# Jupiter_Ace_build025.net
KiCad netlist of a schematic drawn in EAGLE
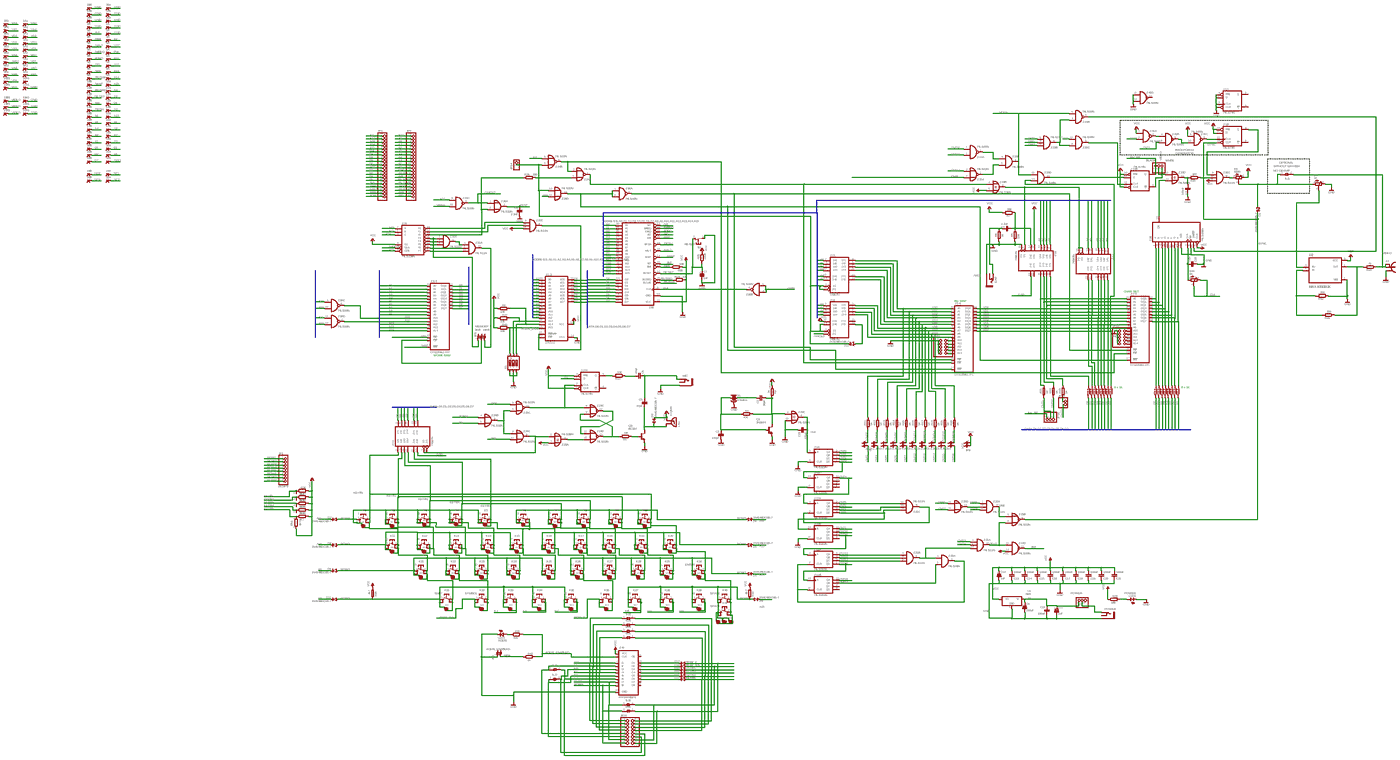
[diagram p0: schematic, sheet 1, overview]
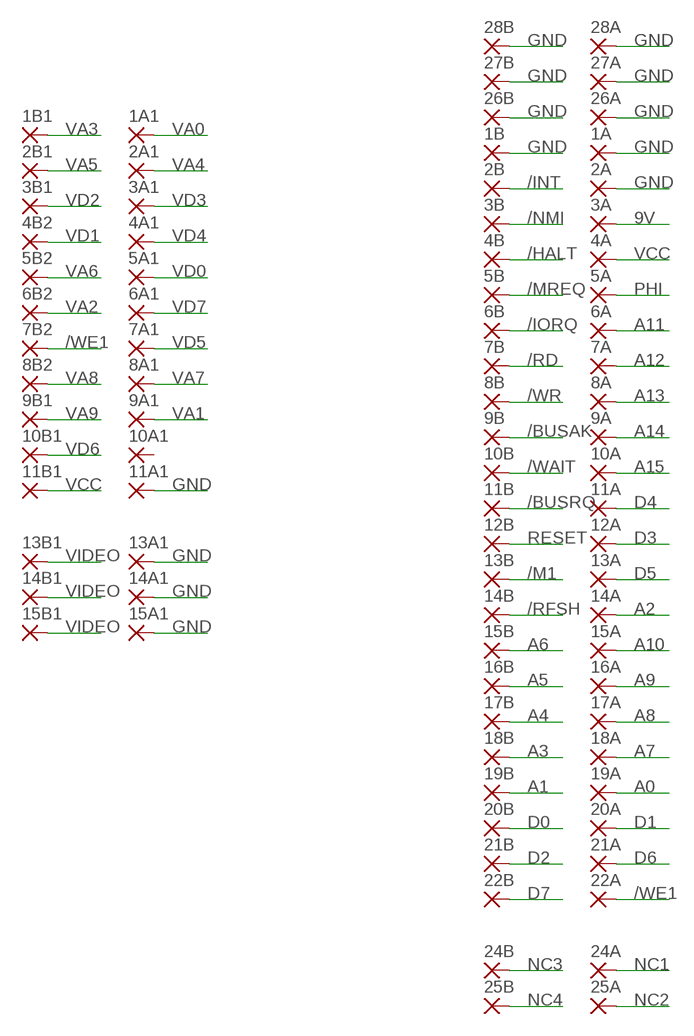
[diagram p1: schematic, sheet 1, part 1 of 6]
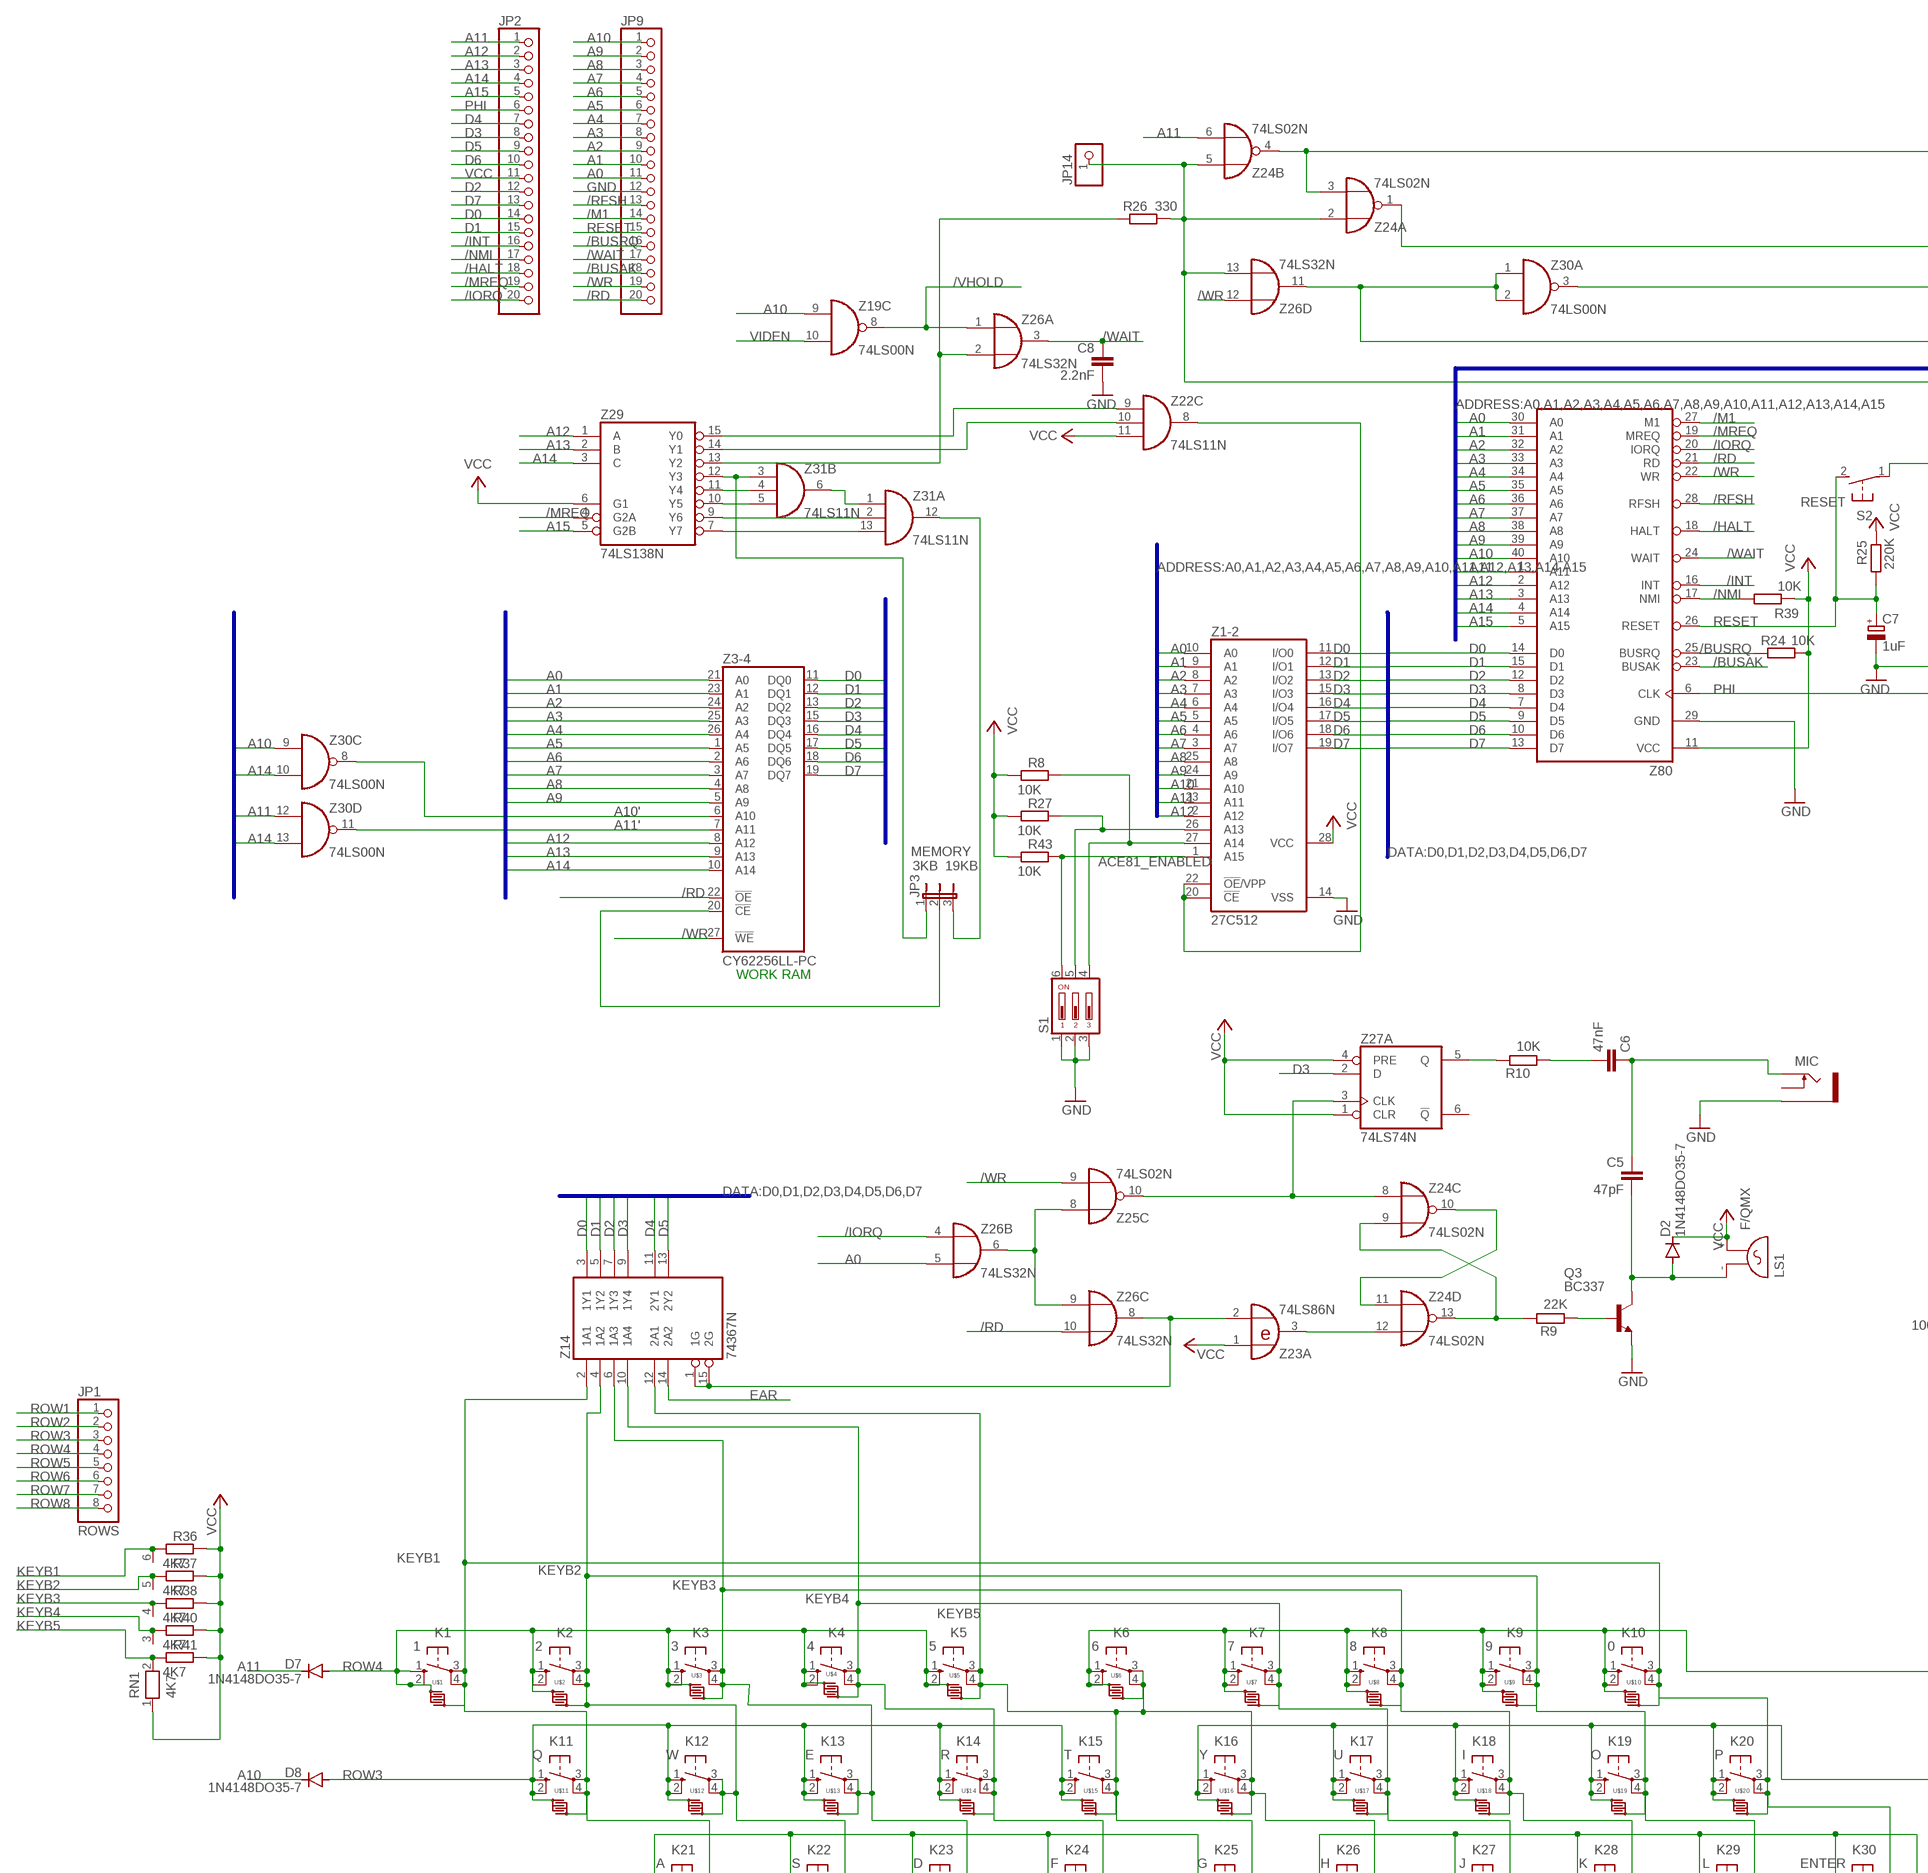
[diagram p2: schematic, sheet 1, part 2 of 6]
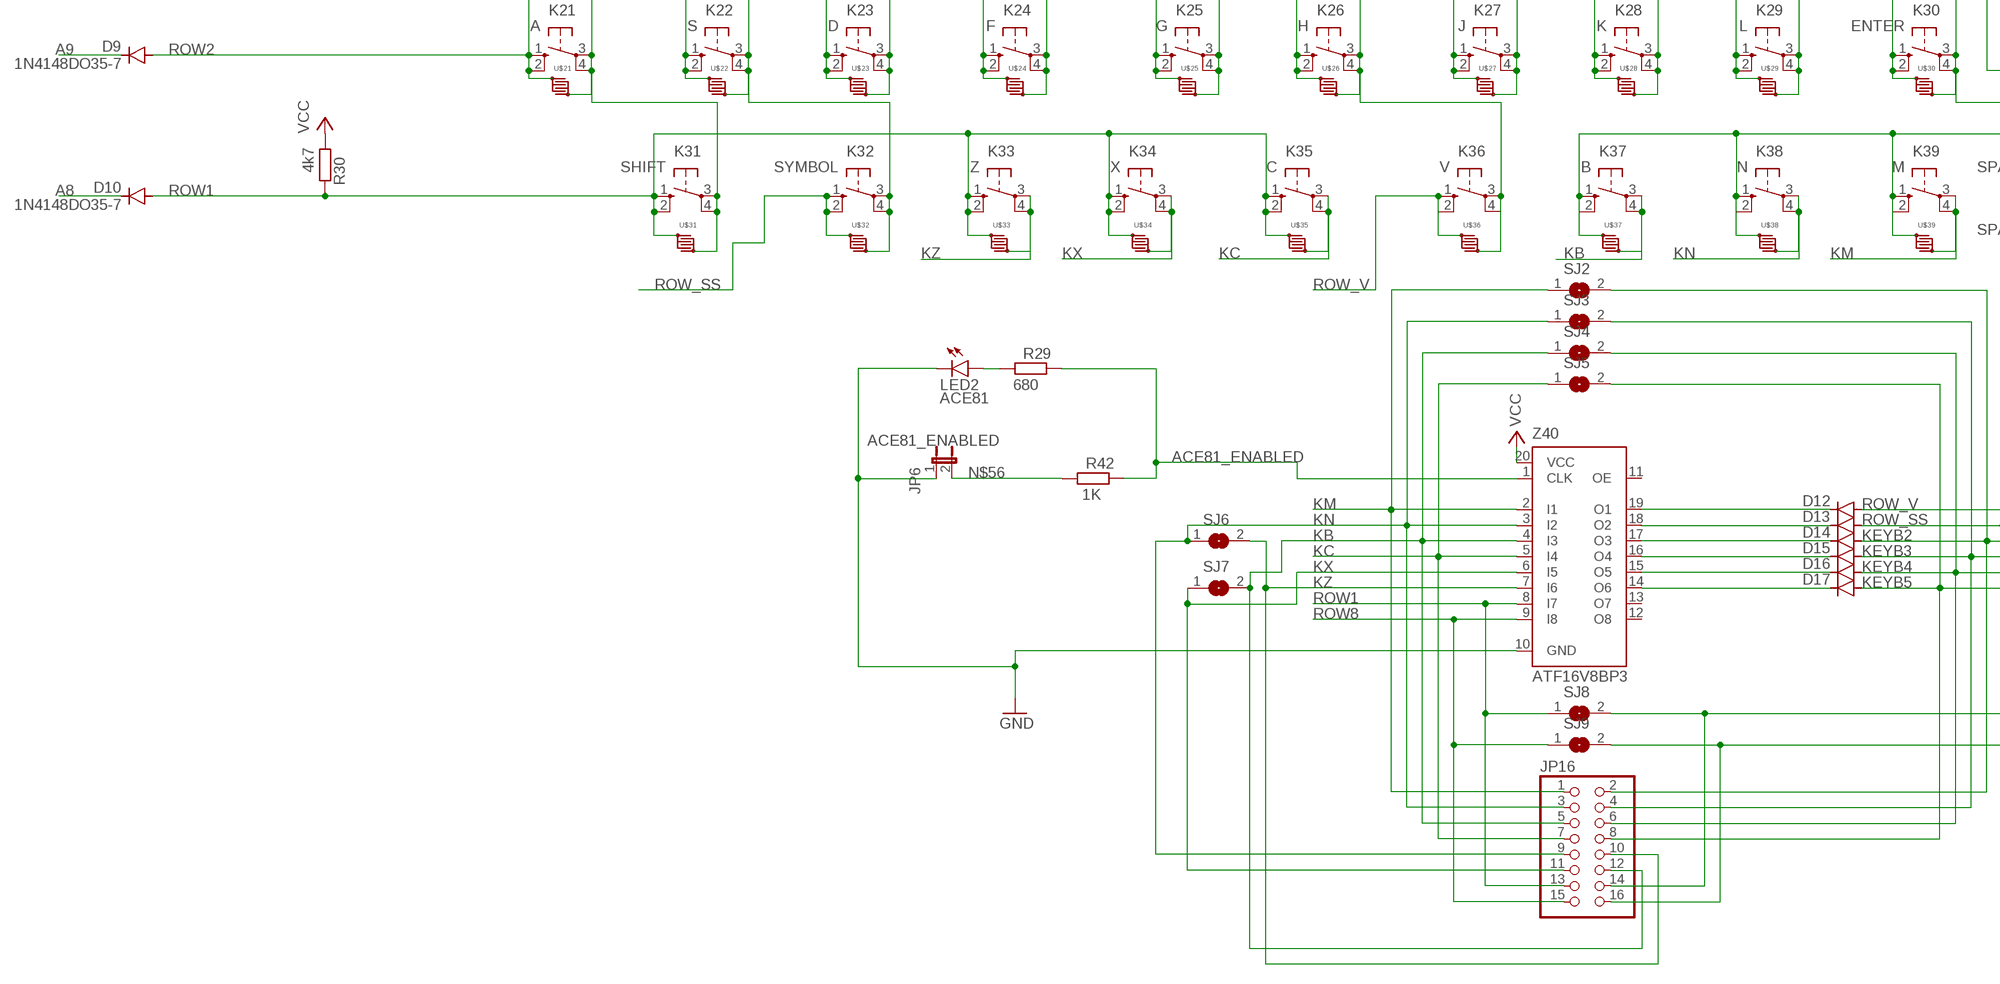
[diagram p3: schematic, sheet 1, part 3 of 6]
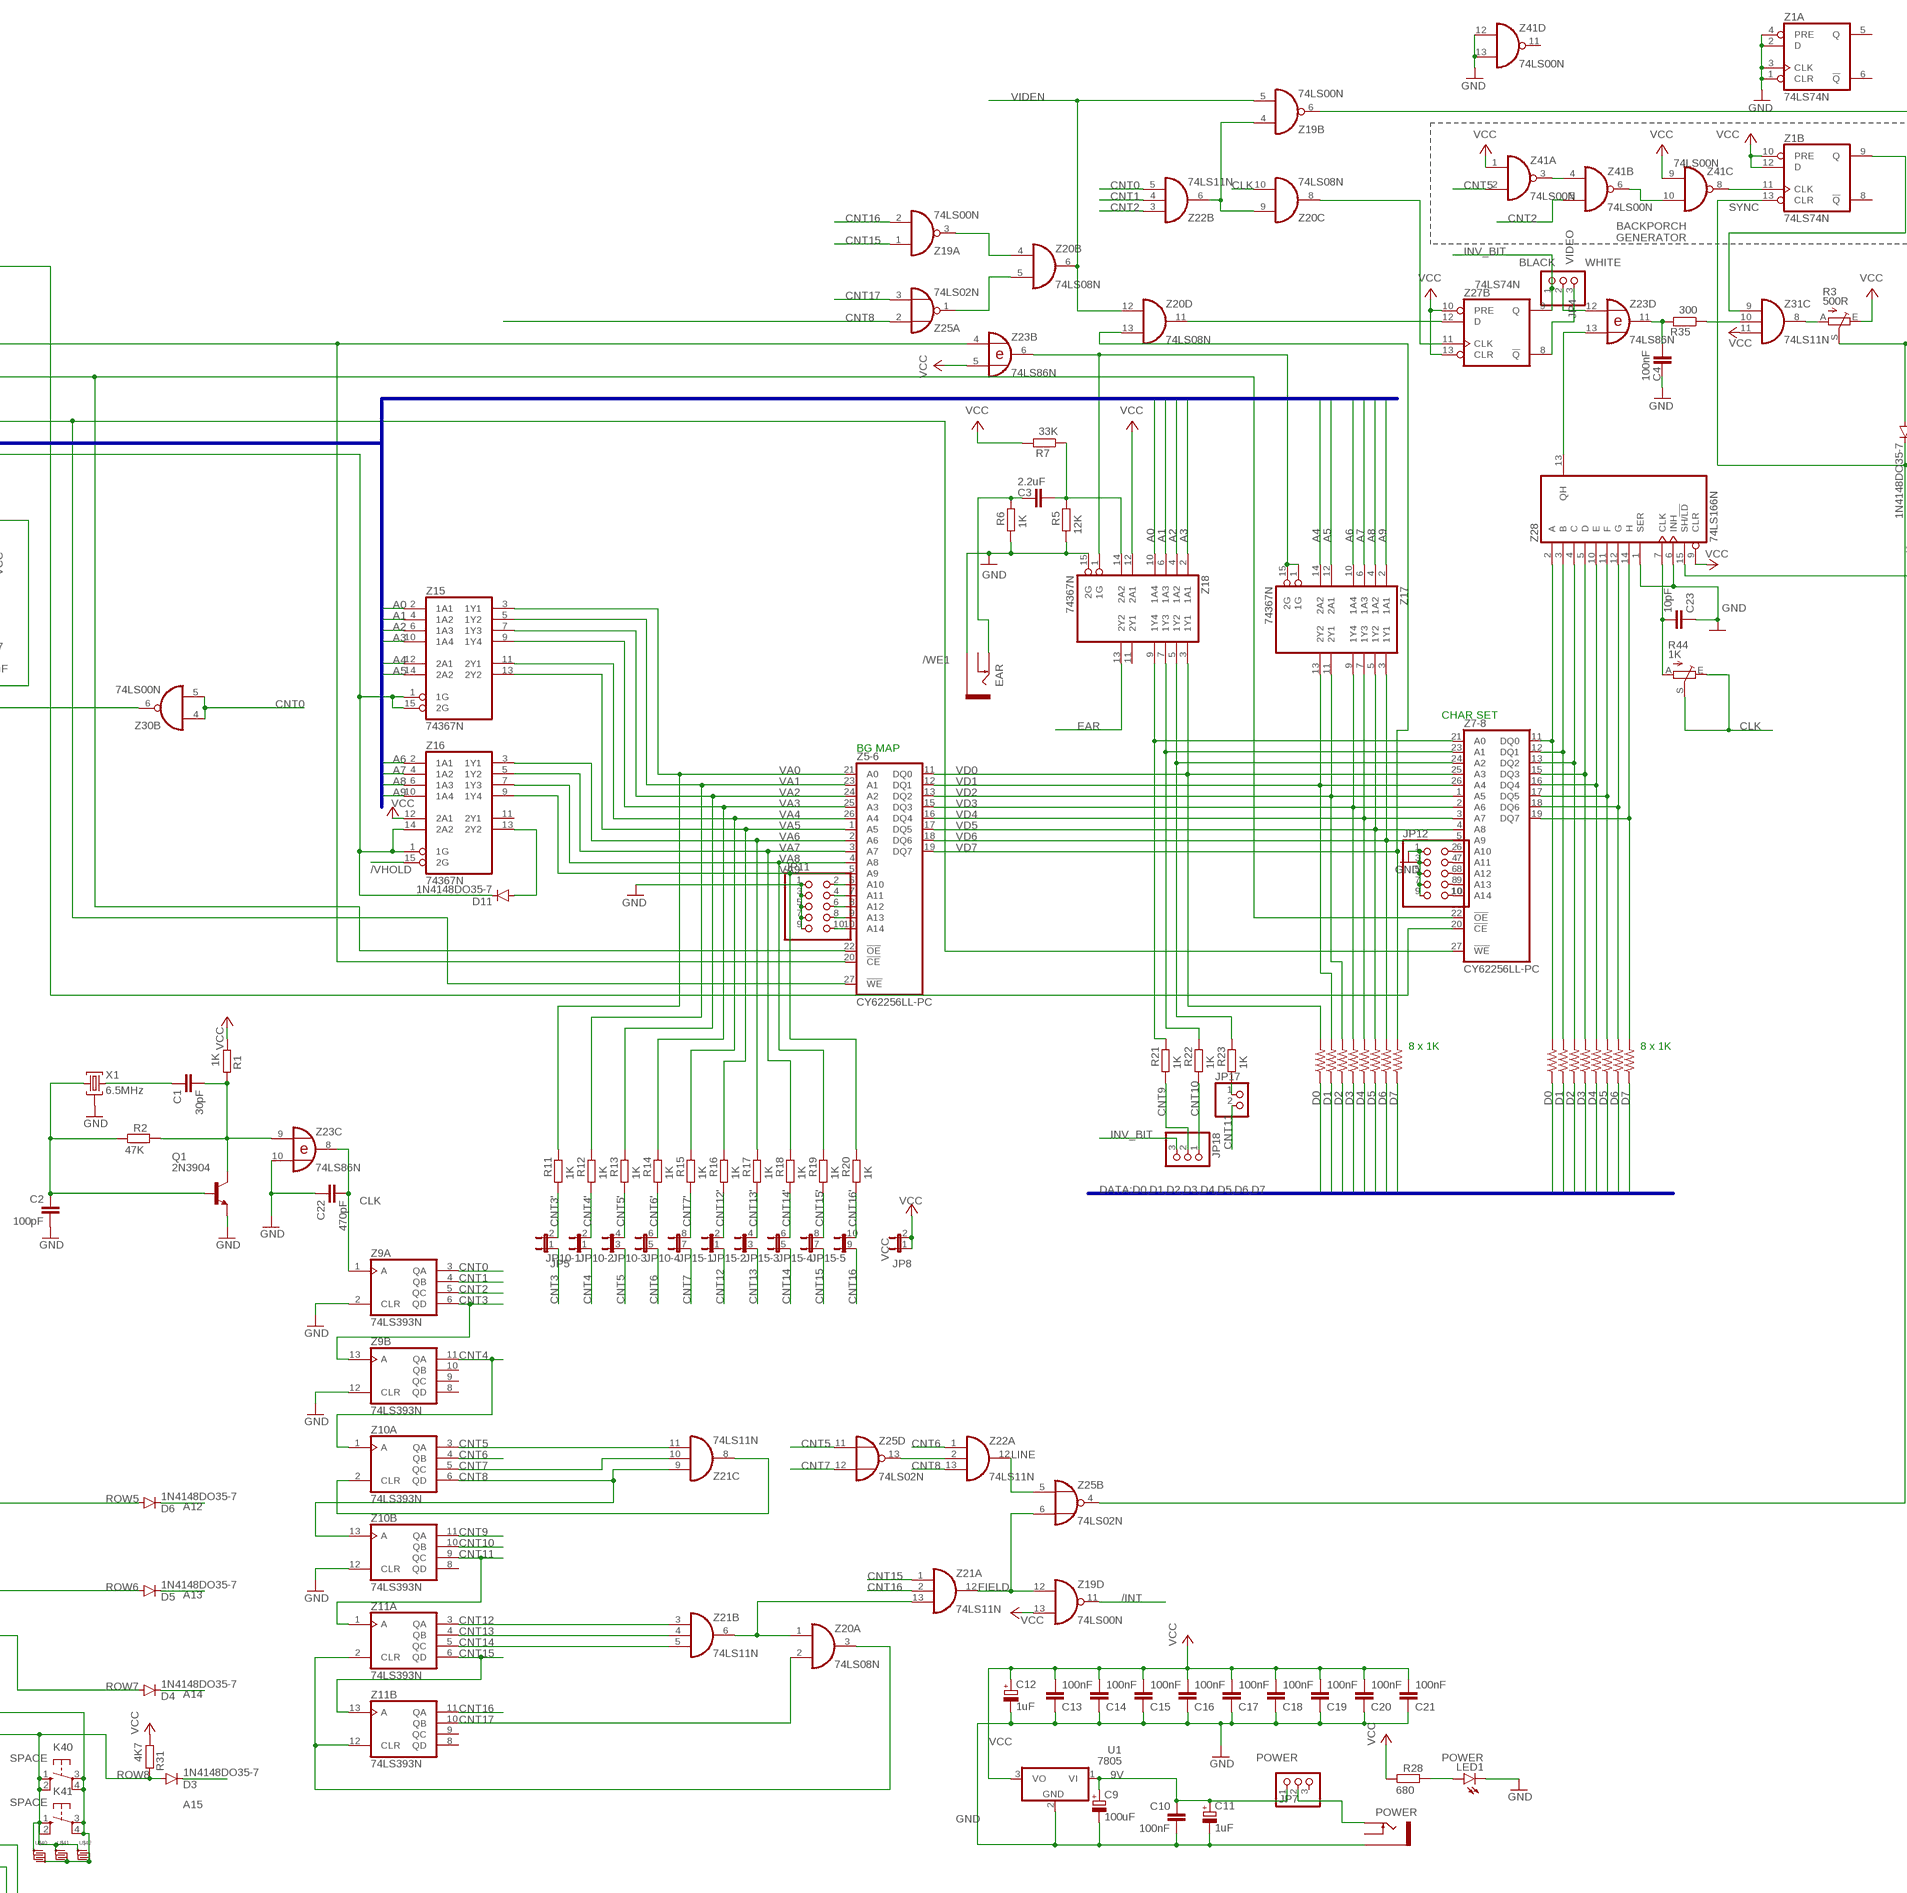
[diagram p4: schematic, sheet 1, part 4 of 6]
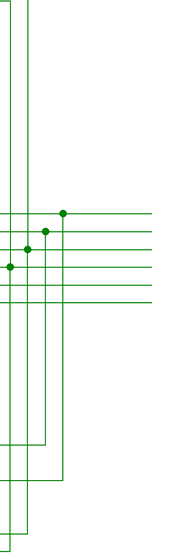
[diagram p5: schematic, sheet 1, part 5 of 6]
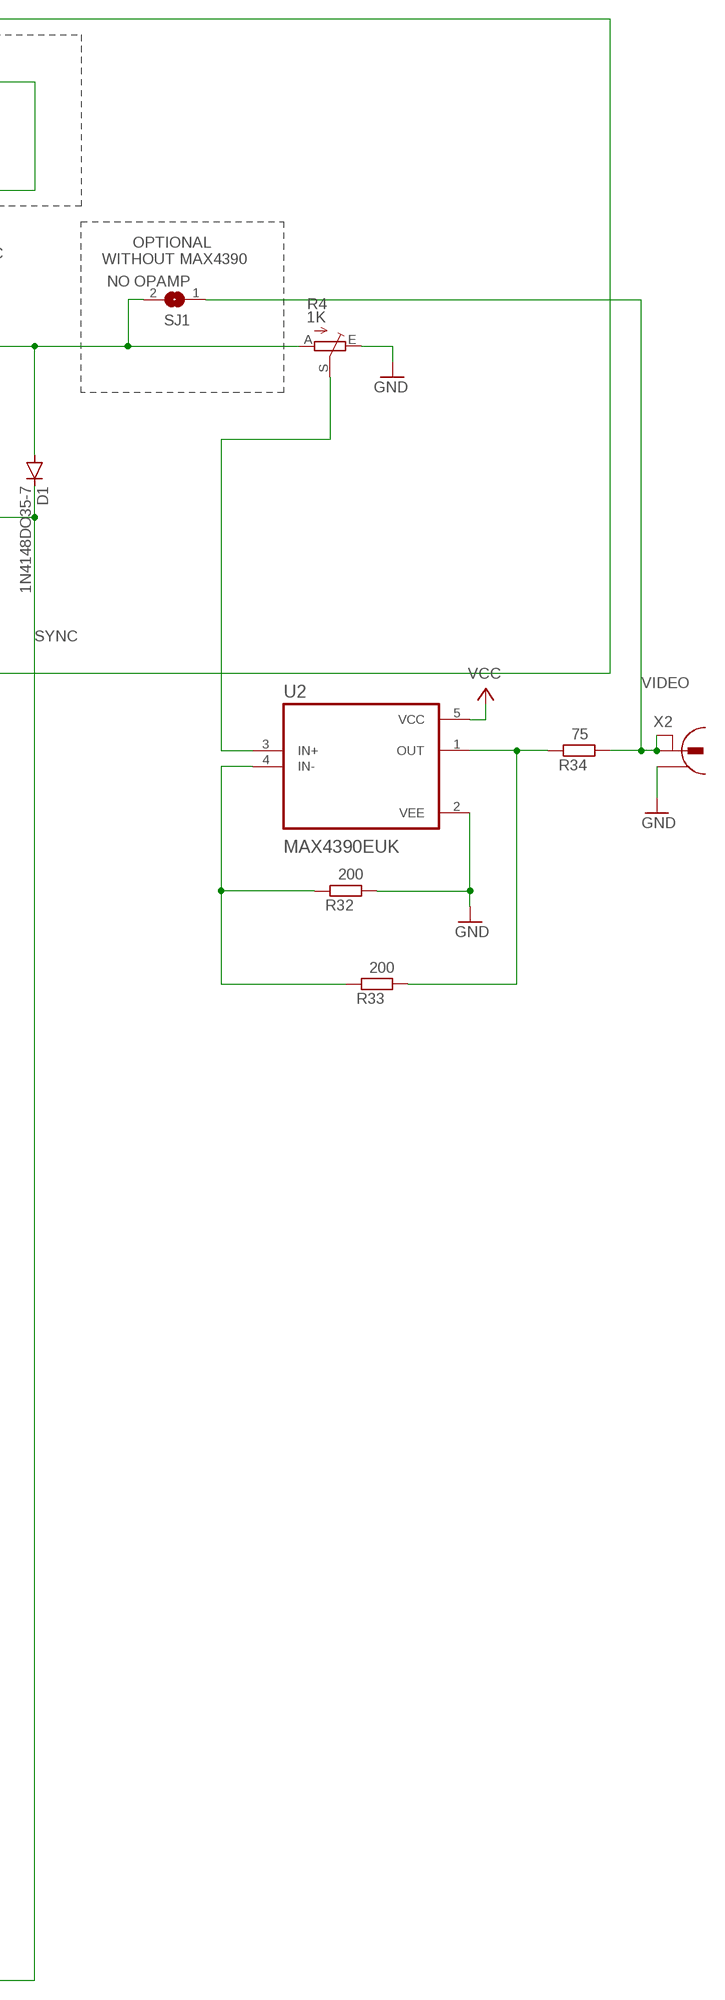
[diagram p6: schematic, sheet 1, part 6 of 6]

(export (version "E")
  (design (tool "Eeschema 10.0.6"))
  (components
    (comp (ref "1A")
      (value "SMD2EDGEPIN")
      (footprint "eagle-import:EDGEPIN")
      (libsource (lib "eagle-import") (part "SMD2EDGEPIN"))
    )
    (comp (ref "1A1")
      (value "SMD2EDGEPIN")
      (footprint "eagle-import:EDGEPIN")
      (libsource (lib "eagle-import") (part "SMD2EDGEPIN"))
    )
    (comp (ref "1B")
      (value "SMD2EDGEPIN")
      (footprint "eagle-import:EDGEPIN")
      (libsource (lib "eagle-import") (part "SMD2EDGEPIN"))
    )
    (comp (ref "1B1")
      (value "SMD2EDGEPIN")
      (footprint "eagle-import:EDGEPIN")
      (libsource (lib "eagle-import") (part "SMD2EDGEPIN"))
    )
    (comp (ref "2A")
      (value "SMD2EDGEPIN")
      (footprint "eagle-import:EDGEPIN")
      (libsource (lib "eagle-import") (part "SMD2EDGEPIN"))
    )
    (comp (ref "2A1")
      (value "SMD2EDGEPIN")
      (footprint "eagle-import:EDGEPIN")
      (libsource (lib "eagle-import") (part "SMD2EDGEPIN"))
    )
    (comp (ref "2B")
      (value "SMD2EDGEPIN")
      (footprint "eagle-import:EDGEPIN")
      (libsource (lib "eagle-import") (part "SMD2EDGEPIN"))
    )
    (comp (ref "2B1")
      (value "SMD2EDGEPIN")
      (footprint "eagle-import:EDGEPIN")
      (libsource (lib "eagle-import") (part "SMD2EDGEPIN"))
    )
    (comp (ref "3A")
      (value "SMD2EDGEPIN")
      (footprint "eagle-import:EDGEPIN")
      (libsource (lib "eagle-import") (part "SMD2EDGEPIN"))
    )
    (comp (ref "3A1")
      (value "SMD2EDGEPIN")
      (footprint "eagle-import:EDGEPIN")
      (libsource (lib "eagle-import") (part "SMD2EDGEPIN"))
    )
    (comp (ref "3B")
      (value "SMD2EDGEPIN")
      (footprint "eagle-import:EDGEPIN")
      (libsource (lib "eagle-import") (part "SMD2EDGEPIN"))
    )
    (comp (ref "3B1")
      (value "SMD2EDGEPIN")
      (footprint "eagle-import:EDGEPIN")
      (libsource (lib "eagle-import") (part "SMD2EDGEPIN"))
    )
    (comp (ref "4A")
      (value "SMD2EDGEPIN")
      (footprint "eagle-import:EDGEPIN")
      (libsource (lib "eagle-import") (part "SMD2EDGEPIN"))
    )
    (comp (ref "4A1")
      (value "SMD2EDGEPIN")
      (footprint "eagle-import:EDGEPIN")
      (libsource (lib "eagle-import") (part "SMD2EDGEPIN"))
    )
    (comp (ref "4B")
      (value "SMD2EDGEPIN")
      (footprint "eagle-import:EDGEPIN")
      (libsource (lib "eagle-import") (part "SMD2EDGEPIN"))
    )
    (comp (ref "4B2")
      (value "SMD2EDGEPIN")
      (footprint "eagle-import:EDGEPIN")
      (libsource (lib "eagle-import") (part "SMD2EDGEPIN"))
    )
    (comp (ref "5A")
      (value "SMD2EDGEPIN")
      (footprint "eagle-import:EDGEPIN")
      (libsource (lib "eagle-import") (part "SMD2EDGEPIN"))
    )
    (comp (ref "5A1")
      (value "SMD2EDGEPIN")
      (footprint "eagle-import:EDGEPIN")
      (libsource (lib "eagle-import") (part "SMD2EDGEPIN"))
    )
    (comp (ref "5B")
      (value "SMD2EDGEPIN")
      (footprint "eagle-import:EDGEPIN")
      (libsource (lib "eagle-import") (part "SMD2EDGEPIN"))
    )
    (comp (ref "5B2")
      (value "SMD2EDGEPIN")
      (footprint "eagle-import:EDGEPIN")
      (libsource (lib "eagle-import") (part "SMD2EDGEPIN"))
    )
    (comp (ref "6A")
      (value "SMD2EDGEPIN")
      (footprint "eagle-import:EDGEPIN")
      (libsource (lib "eagle-import") (part "SMD2EDGEPIN"))
    )
    (comp (ref "6A1")
      (value "SMD2EDGEPIN")
      (footprint "eagle-import:EDGEPIN")
      (libsource (lib "eagle-import") (part "SMD2EDGEPIN"))
    )
    (comp (ref "6B")
      (value "SMD2EDGEPIN")
      (footprint "eagle-import:EDGEPIN")
      (libsource (lib "eagle-import") (part "SMD2EDGEPIN"))
    )
    (comp (ref "6B2")
      (value "SMD2EDGEPIN")
      (footprint "eagle-import:EDGEPIN")
      (libsource (lib "eagle-import") (part "SMD2EDGEPIN"))
    )
    (comp (ref "7A")
      (value "SMD2EDGEPIN")
      (footprint "eagle-import:EDGEPIN")
      (libsource (lib "eagle-import") (part "SMD2EDGEPIN"))
    )
    (comp (ref "7A1")
      (value "SMD2EDGEPIN")
      (footprint "eagle-import:EDGEPIN")
      (libsource (lib "eagle-import") (part "SMD2EDGEPIN"))
    )
    (comp (ref "7B")
      (value "SMD2EDGEPIN")
      (footprint "eagle-import:EDGEPIN")
      (libsource (lib "eagle-import") (part "SMD2EDGEPIN"))
    )
    (comp (ref "7B2")
      (value "SMD2EDGEPIN")
      (footprint "eagle-import:EDGEPIN")
      (libsource (lib "eagle-import") (part "SMD2EDGEPIN"))
    )
    (comp (ref "8A")
      (value "SMD2EDGEPIN")
      (footprint "eagle-import:EDGEPIN")
      (libsource (lib "eagle-import") (part "SMD2EDGEPIN"))
    )
    (comp (ref "8A1")
      (value "SMD2EDGEPIN")
      (footprint "eagle-import:EDGEPIN")
      (libsource (lib "eagle-import") (part "SMD2EDGEPIN"))
    )
    (comp (ref "8B")
      (value "SMD2EDGEPIN")
      (footprint "eagle-import:EDGEPIN")
      (libsource (lib "eagle-import") (part "SMD2EDGEPIN"))
    )
    (comp (ref "8B2")
      (value "SMD2EDGEPIN")
      (footprint "eagle-import:EDGEPIN")
      (libsource (lib "eagle-import") (part "SMD2EDGEPIN"))
    )
    (comp (ref "9A")
      (value "SMD2EDGEPIN")
      (footprint "eagle-import:EDGEPIN")
      (libsource (lib "eagle-import") (part "SMD2EDGEPIN"))
    )
    (comp (ref "9A1")
      (value "SMD2EDGEPIN")
      (footprint "eagle-import:EDGEPIN")
      (libsource (lib "eagle-import") (part "SMD2EDGEPIN"))
    )
    (comp (ref "9B")
      (value "SMD2EDGEPIN")
      (footprint "eagle-import:EDGEPIN")
      (libsource (lib "eagle-import") (part "SMD2EDGEPIN"))
    )
    (comp (ref "9B1")
      (value "SMD2EDGEPIN")
      (footprint "eagle-import:EDGEPIN")
      (libsource (lib "eagle-import") (part "SMD2EDGEPIN"))
    )
    (comp (ref "10A")
      (value "SMD2EDGEPIN")
      (footprint "eagle-import:EDGEPIN")
      (libsource (lib "eagle-import") (part "SMD2EDGEPIN"))
    )
    (comp (ref "10A1")
      (value "SMD2EDGEPIN")
      (footprint "eagle-import:EDGEPIN")
      (libsource (lib "eagle-import") (part "SMD2EDGEPIN"))
    )
    (comp (ref "10B")
      (value "SMD2EDGEPIN")
      (footprint "eagle-import:EDGEPIN")
      (libsource (lib "eagle-import") (part "SMD2EDGEPIN"))
    )
    (comp (ref "10B1")
      (value "SMD2EDGEPIN")
      (footprint "eagle-import:EDGEPIN")
      (libsource (lib "eagle-import") (part "SMD2EDGEPIN"))
    )
    (comp (ref "11A")
      (value "SMD2EDGEPIN")
      (footprint "eagle-import:EDGEPIN")
      (libsource (lib "eagle-import") (part "SMD2EDGEPIN"))
    )
    (comp (ref "11A1")
      (value "SMD2EDGEPIN")
      (footprint "eagle-import:EDGEPIN")
      (libsource (lib "eagle-import") (part "SMD2EDGEPIN"))
    )
    (comp (ref "11B")
      (value "SMD2EDGEPIN")
      (footprint "eagle-import:EDGEPIN")
      (libsource (lib "eagle-import") (part "SMD2EDGEPIN"))
    )
    (comp (ref "11B1")
      (value "SMD2EDGEPIN")
      (footprint "eagle-import:EDGEPIN")
      (libsource (lib "eagle-import") (part "SMD2EDGEPIN"))
    )
    (comp (ref "12A")
      (value "SMD2EDGEPIN")
      (footprint "eagle-import:EDGEPIN")
      (libsource (lib "eagle-import") (part "SMD2EDGEPIN"))
    )
    (comp (ref "12B")
      (value "SMD2EDGEPIN")
      (footprint "eagle-import:EDGEPIN")
      (libsource (lib "eagle-import") (part "SMD2EDGEPIN"))
    )
    (comp (ref "13A")
      (value "SMD2EDGEPIN")
      (footprint "eagle-import:EDGEPIN")
      (libsource (lib "eagle-import") (part "SMD2EDGEPIN"))
    )
    (comp (ref "13A1")
      (value "SMD2EDGEPIN")
      (footprint "eagle-import:EDGEPIN")
      (libsource (lib "eagle-import") (part "SMD2EDGEPIN"))
    )
    (comp (ref "13B")
      (value "SMD2EDGEPIN")
      (footprint "eagle-import:EDGEPIN")
      (libsource (lib "eagle-import") (part "SMD2EDGEPIN"))
    )
    (comp (ref "13B1")
      (value "SMD2EDGEPIN")
      (footprint "eagle-import:EDGEPIN")
      (libsource (lib "eagle-import") (part "SMD2EDGEPIN"))
    )
    (comp (ref "14A")
      (value "SMD2EDGEPIN")
      (footprint "eagle-import:EDGEPIN")
      (libsource (lib "eagle-import") (part "SMD2EDGEPIN"))
    )
    (comp (ref "14A1")
      (value "SMD2EDGEPIN")
      (footprint "eagle-import:EDGEPIN")
      (libsource (lib "eagle-import") (part "SMD2EDGEPIN"))
    )
    (comp (ref "14B")
      (value "SMD2EDGEPIN")
      (footprint "eagle-import:EDGEPIN")
      (libsource (lib "eagle-import") (part "SMD2EDGEPIN"))
    )
    (comp (ref "14B1")
      (value "SMD2EDGEPIN")
      (footprint "eagle-import:EDGEPIN")
      (libsource (lib "eagle-import") (part "SMD2EDGEPIN"))
    )
    (comp (ref "15A")
      (value "SMD2EDGEPIN")
      (footprint "eagle-import:EDGEPIN")
      (libsource (lib "eagle-import") (part "SMD2EDGEPIN"))
    )
    (comp (ref "15A1")
      (value "SMD2EDGEPIN")
      (footprint "eagle-import:EDGEPIN")
      (libsource (lib "eagle-import") (part "SMD2EDGEPIN"))
    )
    (comp (ref "15B")
      (value "SMD2EDGEPIN")
      (footprint "eagle-import:EDGEPIN")
      (libsource (lib "eagle-import") (part "SMD2EDGEPIN"))
    )
    (comp (ref "15B1")
      (value "SMD2EDGEPIN")
      (footprint "eagle-import:EDGEPIN")
      (libsource (lib "eagle-import") (part "SMD2EDGEPIN"))
    )
    (comp (ref "16A")
      (value "SMD2EDGEPIN")
      (footprint "eagle-import:EDGEPIN")
      (libsource (lib "eagle-import") (part "SMD2EDGEPIN"))
    )
    (comp (ref "16B")
      (value "SMD2EDGEPIN")
      (footprint "eagle-import:EDGEPIN")
      (libsource (lib "eagle-import") (part "SMD2EDGEPIN"))
    )
    (comp (ref "17A")
      (value "SMD2EDGEPIN")
      (footprint "eagle-import:EDGEPIN")
      (libsource (lib "eagle-import") (part "SMD2EDGEPIN"))
    )
    (comp (ref "17B")
      (value "SMD2EDGEPIN")
      (footprint "eagle-import:EDGEPIN")
      (libsource (lib "eagle-import") (part "SMD2EDGEPIN"))
    )
    (comp (ref "18A")
      (value "SMD2EDGEPIN")
      (footprint "eagle-import:EDGEPIN")
      (libsource (lib "eagle-import") (part "SMD2EDGEPIN"))
    )
    (comp (ref "18B")
      (value "SMD2EDGEPIN")
      (footprint "eagle-import:EDGEPIN")
      (libsource (lib "eagle-import") (part "SMD2EDGEPIN"))
    )
    (comp (ref "19A")
      (value "SMD2EDGEPIN")
      (footprint "eagle-import:EDGEPIN")
      (libsource (lib "eagle-import") (part "SMD2EDGEPIN"))
    )
    (comp (ref "19B")
      (value "SMD2EDGEPIN")
      (footprint "eagle-import:EDGEPIN")
      (libsource (lib "eagle-import") (part "SMD2EDGEPIN"))
    )
    (comp (ref "20A")
      (value "SMD2EDGEPIN")
      (footprint "eagle-import:EDGEPIN")
      (libsource (lib "eagle-import") (part "SMD2EDGEPIN"))
    )
    (comp (ref "20B")
      (value "SMD2EDGEPIN")
      (footprint "eagle-import:EDGEPIN")
      (libsource (lib "eagle-import") (part "SMD2EDGEPIN"))
    )
    (comp (ref "21A")
      (value "SMD2EDGEPIN")
      (footprint "eagle-import:EDGEPIN")
      (libsource (lib "eagle-import") (part "SMD2EDGEPIN"))
    )
    (comp (ref "21B")
      (value "SMD2EDGEPIN")
      (footprint "eagle-import:EDGEPIN")
      (libsource (lib "eagle-import") (part "SMD2EDGEPIN"))
    )
    (comp (ref "22A")
      (value "SMD2EDGEPIN")
      (footprint "eagle-import:EDGEPIN")
      (libsource (lib "eagle-import") (part "SMD2EDGEPIN"))
    )
    (comp (ref "22B")
      (value "SMD2EDGEPIN")
      (footprint "eagle-import:EDGEPIN")
      (libsource (lib "eagle-import") (part "SMD2EDGEPIN"))
    )
    (comp (ref "24A")
      (value "SMD2EDGEPIN")
      (footprint "eagle-import:EDGEPIN")
      (libsource (lib "eagle-import") (part "SMD2EDGEPIN"))
    )
    (comp (ref "24B")
      (value "SMD2EDGEPIN")
      (footprint "eagle-import:EDGEPIN")
      (libsource (lib "eagle-import") (part "SMD2EDGEPIN"))
    )
    (comp (ref "25A")
      (value "SMD2EDGEPIN")
      (footprint "eagle-import:EDGEPIN")
      (libsource (lib "eagle-import") (part "SMD2EDGEPIN"))
    )
    (comp (ref "25B")
      (value "SMD2EDGEPIN")
      (footprint "eagle-import:EDGEPIN")
      (libsource (lib "eagle-import") (part "SMD2EDGEPIN"))
    )
    (comp (ref "26A")
      (value "SMD2EDGEPIN")
      (footprint "eagle-import:EDGEPIN")
      (libsource (lib "eagle-import") (part "SMD2EDGEPIN"))
    )
    (comp (ref "26B")
      (value "SMD2EDGEPIN")
      (footprint "eagle-import:EDGEPIN")
      (libsource (lib "eagle-import") (part "SMD2EDGEPIN"))
    )
    (comp (ref "27A")
      (value "SMD2EDGEPIN")
      (footprint "eagle-import:EDGEPIN")
      (libsource (lib "eagle-import") (part "SMD2EDGEPIN"))
    )
    (comp (ref "27B")
      (value "SMD2EDGEPIN")
      (footprint "eagle-import:EDGEPIN")
      (libsource (lib "eagle-import") (part "SMD2EDGEPIN"))
    )
    (comp (ref "28A")
      (value "SMD2EDGEPIN")
      (footprint "eagle-import:EDGEPIN")
      (libsource (lib "eagle-import") (part "SMD2EDGEPIN"))
    )
    (comp (ref "28B")
      (value "SMD2EDGEPIN")
      (footprint "eagle-import:EDGEPIN")
      (libsource (lib "eagle-import") (part "SMD2EDGEPIN"))
    )
    (comp (ref "C1")
      (value "30pF")
      (footprint "eagle-import:C025-025X050")
      (libsource (lib "eagle-import") (part "C-EU025-025X050"))
    )
    (comp (ref "C2")
      (value "100pF")
      (footprint "eagle-import:C025-025X050")
      (libsource (lib "eagle-import") (part "C-EU025-025X050"))
    )
    (comp (ref "C3")
      (value "2.2uF")
      (footprint "eagle-import:C025-025X050")
      (libsource (lib "eagle-import") (part "C-EU025-025X050"))
    )
    (comp (ref "C4")
      (value "100nF")
      (footprint "eagle-import:C025-025X050")
      (libsource (lib "eagle-import") (part "C-EU025-025X050"))
    )
    (comp (ref "C5")
      (value "47pF")
      (footprint "eagle-import:C025-025X050")
      (libsource (lib "eagle-import") (part "C-EU025-025X050"))
    )
    (comp (ref "C6")
      (value "47nF")
      (footprint "eagle-import:C025-025X050")
      (libsource (lib "eagle-import") (part "C-EU025-025X050"))
    )
    (comp (ref "C7")
      (value "1uF")
      (footprint "eagle-import:E1,8-4")
      (libsource (lib "eagle-import") (part "CPOL-EUE1.8-4"))
    )
    (comp (ref "C8")
      (value "2.2nF")
      (footprint "eagle-import:C025-025X050")
      (libsource (lib "eagle-import") (part "C-EU025-025X050"))
    )
    (comp (ref "C9")
      (value "100uF")
      (footprint "eagle-import:E1,8-4")
      (libsource (lib "eagle-import") (part "CPOL-EUE1.8-4"))
    )
    (comp (ref "C10")
      (value "100nF")
      (footprint "eagle-import:C025-025X050")
      (libsource (lib "eagle-import") (part "C-EU025-025X050"))
    )
    (comp (ref "C11")
      (value "1uF")
      (footprint "eagle-import:E1,8-4")
      (libsource (lib "eagle-import") (part "CPOL-EUE1.8-4"))
    )
    (comp (ref "C12")
      (value "1uF")
      (footprint "eagle-import:E1,8-4")
      (libsource (lib "eagle-import") (part "CPOL-EUE1.8-4"))
    )
    (comp (ref "C13")
      (value "100nF")
      (footprint "eagle-import:C025-025X050")
      (libsource (lib "eagle-import") (part "C-EU025-025X050"))
    )
    (comp (ref "C14")
      (value "100nF")
      (footprint "eagle-import:C025-025X050")
      (libsource (lib "eagle-import") (part "C-EU025-025X050"))
    )
    (comp (ref "C15")
      (value "100nF")
      (footprint "eagle-import:C025-025X050")
      (libsource (lib "eagle-import") (part "C-EU025-025X050"))
    )
    (comp (ref "C16")
      (value "100nF")
      (footprint "eagle-import:C025-025X050")
      (libsource (lib "eagle-import") (part "C-EU025-025X050"))
    )
    (comp (ref "C17")
      (value "100nF")
      (footprint "eagle-import:C025-025X050")
      (libsource (lib "eagle-import") (part "C-EU025-025X050"))
    )
    (comp (ref "C18")
      (value "100nF")
      (footprint "eagle-import:C025-025X050")
      (libsource (lib "eagle-import") (part "C-EU025-025X050"))
    )
    (comp (ref "C19")
      (value "100nF")
      (footprint "eagle-import:C025-025X050")
      (libsource (lib "eagle-import") (part "C-EU025-025X050"))
    )
    (comp (ref "C20")
      (value "100nF")
      (footprint "eagle-import:C025-025X050")
      (libsource (lib "eagle-import") (part "C-EU025-025X050"))
    )
    (comp (ref "C21")
      (value "100nF")
      (footprint "eagle-import:C025-025X050")
      (libsource (lib "eagle-import") (part "C-EU025-025X050"))
    )
    (comp (ref "C22")
      (value "470pF")
      (footprint "eagle-import:C025-025X050")
      (libsource (lib "eagle-import") (part "C-EU025-025X050"))
    )
    (comp (ref "C23")
      (value "10pF")
      (footprint "eagle-import:C025-025X050")
      (libsource (lib "eagle-import") (part "C-EU025-025X050"))
    )
    (comp (ref "D1")
      (value "1N4148DO35-7")
      (footprint "eagle-import:DO35-7")
      (libsource (lib "eagle-import") (part "1N4148DO35-7"))
    )
    (comp (ref "D2")
      (value "1N4148DO35-7")
      (footprint "eagle-import:DO35-7")
      (libsource (lib "eagle-import") (part "1N4148DO35-7"))
    )
    (comp (ref "D3")
      (value "1N4148DO35-7")
      (footprint "eagle-import:DO35-7")
      (libsource (lib "eagle-import") (part "1N4148DO35-7"))
    )
    (comp (ref "D4")
      (value "1N4148DO35-7")
      (footprint "eagle-import:DO35-7")
      (libsource (lib "eagle-import") (part "1N4148DO35-7"))
    )
    (comp (ref "D5")
      (value "1N4148DO35-7")
      (footprint "eagle-import:DO35-7")
      (libsource (lib "eagle-import") (part "1N4148DO35-7"))
    )
    (comp (ref "D6")
      (value "1N4148DO35-7")
      (footprint "eagle-import:DO35-7")
      (libsource (lib "eagle-import") (part "1N4148DO35-7"))
    )
    (comp (ref "D7")
      (value "1N4148DO35-7")
      (footprint "eagle-import:DO35-7")
      (libsource (lib "eagle-import") (part "1N4148DO35-7"))
    )
    (comp (ref "D8")
      (value "1N4148DO35-7")
      (footprint "eagle-import:DO35-7")
      (libsource (lib "eagle-import") (part "1N4148DO35-7"))
    )
    (comp (ref "D9")
      (value "1N4148DO35-7")
      (footprint "eagle-import:DO35-7")
      (libsource (lib "eagle-import") (part "1N4148DO35-7"))
    )
    (comp (ref "D10")
      (value "1N4148DO35-7")
      (footprint "eagle-import:DO35-7")
      (libsource (lib "eagle-import") (part "1N4148DO35-7"))
    )
    (comp (ref "D11")
      (value "1N4148DO35-7")
      (footprint "eagle-import:DO35-7")
      (libsource (lib "eagle-import") (part "1N4148DO35-7"))
    )
    (comp (ref "D12")
      (value "1N4148DO35-7")
      (footprint "eagle-import:DO35-7")
      (libsource (lib "eagle-import") (part "1N4148DO35-7"))
    )
    (comp (ref "D13")
      (value "1N4148DO35-7")
      (footprint "eagle-import:DO35-7")
      (libsource (lib "eagle-import") (part "1N4148DO35-7"))
    )
    (comp (ref "D14")
      (value "1N4148DO35-7")
      (footprint "eagle-import:DO35-7")
      (libsource (lib "eagle-import") (part "1N4148DO35-7"))
    )
    (comp (ref "D15")
      (value "1N4148DO35-7")
      (footprint "eagle-import:DO35-7")
      (libsource (lib "eagle-import") (part "1N4148DO35-7"))
    )
    (comp (ref "D16")
      (value "1N4148DO35-7")
      (footprint "eagle-import:DO35-7")
      (libsource (lib "eagle-import") (part "1N4148DO35-7"))
    )
    (comp (ref "D17")
      (value "1N4148DO35-7")
      (footprint "eagle-import:DO35-7")
      (libsource (lib "eagle-import") (part "1N4148DO35-7"))
    )
    (comp (ref "EAR")
      (value "PJ302M")
      (footprint "eagle-import:PJ302M")
      (libsource (lib "eagle-import") (part "PJ302M"))
    )
    (comp (ref "JP1")
      (value "ROWS")
      (footprint "eagle-import:1X08")
      (libsource (lib "eagle-import") (part "PINHD-1X8"))
    )
    (comp (ref "JP2")
      (value "PINHD-1X20")
      (footprint "eagle-import:1X20")
      (libsource (lib "eagle-import") (part "PINHD-1X20"))
    )
    (comp (ref "JP3")
      (value "MEMORY")
      (footprint "eagle-import:JP2")
      (libsource (lib "eagle-import") (part "JP2E"))
    )
    (comp (ref "JP4")
      (value "VIDEO")
      (footprint "eagle-import:1X03")
      (libsource (lib "eagle-import") (part "PINHD-1X3"))
    )
    (comp (ref "JP5")
      (value "JP1E1Q")
      (footprint "eagle-import:JP1Q")
      (libsource (lib "eagle-import") (part "JP1E1Q"))
    )
    (comp (ref "JP6")
      (value "ACE81_ENABLED")
      (footprint "eagle-import:JP1Q")
      (libsource (lib "eagle-import") (part "JP1E1Q"))
    )
    (comp (ref "JP7")
      (value "POWER")
      (footprint "eagle-import:1X03")
      (libsource (lib "eagle-import") (part "PINHD-1X3"))
    )
    (comp (ref "JP8")
      (value "VCC")
      (footprint "eagle-import:JP1Q")
      (libsource (lib "eagle-import") (part "JP1E1Q"))
    )
    (comp (ref "JP9")
      (value "PINHD-1X20")
      (footprint "eagle-import:1X20")
      (libsource (lib "eagle-import") (part "PINHD-1X20"))
    )
    (comp (ref "JP10")
      (value "JP4QE")
      (footprint "eagle-import:JP4Q")
      (libsource (lib "eagle-import") (part "JP4QE"))
    )
    (comp (ref "JP11")
      (value "PINHD-2X5")
      (footprint "eagle-import:2X05")
      (libsource (lib "eagle-import") (part "PINHD-2X5"))
    )
    (comp (ref "JP12")
      (value "PINHD-2X5")
      (footprint "eagle-import:2X05")
      (libsource (lib "eagle-import") (part "PINHD-2X5"))
    )
    (comp (ref "JP14")
      (value "PINHD-1X1")
      (footprint "eagle-import:1X01")
      (libsource (lib "eagle-import") (part "PINHD-1X1"))
    )
    (comp (ref "JP15")
      (value "JP5QE")
      (footprint "eagle-import:JP5Q")
      (libsource (lib "eagle-import") (part "JP5QE"))
    )
    (comp (ref "JP16")
      (value "PINHD-2X8")
      (footprint "eagle-import:2X08")
      (libsource (lib "eagle-import") (part "PINHD-2X8"))
    )
    (comp (ref "JP17")
      (value "PINHD-1X2")
      (footprint "eagle-import:1X02")
      (libsource (lib "eagle-import") (part "PINHD-1X2"))
    )
    (comp (ref "JP18")
      (value "PINHD-1X3")
      (footprint "eagle-import:1X03")
      (libsource (lib "eagle-import") (part "pinhead_44166543_PINHD-1X3"))
    )
    (comp (ref "K1")
      (value "1")
      (footprint "eagle-import:B3F-40XXNOHOLE")
      (libsource (lib "eagle-import") (part "40-XXNOHOLES"))
    )
    (comp (ref "K2")
      (value "2")
      (footprint "eagle-import:B3F-40XXNOHOLE")
      (libsource (lib "eagle-import") (part "40-XXNOHOLES"))
    )
    (comp (ref "K3")
      (value "3")
      (footprint "eagle-import:B3F-40XXNOHOLE")
      (libsource (lib "eagle-import") (part "40-XXNOHOLES"))
    )
    (comp (ref "K4")
      (value "4")
      (footprint "eagle-import:B3F-40XXNOHOLE")
      (libsource (lib "eagle-import") (part "40-XXNOHOLES"))
    )
    (comp (ref "K5")
      (value "5")
      (footprint "eagle-import:B3F-40XXNOHOLE")
      (libsource (lib "eagle-import") (part "40-XXNOHOLES"))
    )
    (comp (ref "K6")
      (value "6")
      (footprint "eagle-import:B3F-40XXNOHOLE")
      (libsource (lib "eagle-import") (part "40-XXNOHOLES"))
    )
    (comp (ref "K7")
      (value "7")
      (footprint "eagle-import:B3F-40XXNOHOLE")
      (libsource (lib "eagle-import") (part "40-XXNOHOLES"))
    )
    (comp (ref "K8")
      (value "8")
      (footprint "eagle-import:B3F-40XXNOHOLE")
      (libsource (lib "eagle-import") (part "40-XXNOHOLES"))
    )
    (comp (ref "K9")
      (value "9")
      (footprint "eagle-import:B3F-40XXNOHOLE")
      (libsource (lib "eagle-import") (part "40-XXNOHOLES"))
    )
    (comp (ref "K10")
      (value "0")
      (footprint "eagle-import:B3F-40XXNOHOLE")
      (libsource (lib "eagle-import") (part "40-XXNOHOLES"))
    )
    (comp (ref "K11")
      (value "Q")
      (footprint "eagle-import:B3F-40XXNOHOLE")
      (libsource (lib "eagle-import") (part "40-XXNOHOLES"))
    )
    (comp (ref "K12")
      (value "W")
      (footprint "eagle-import:B3F-40XXNOHOLE")
      (libsource (lib "eagle-import") (part "40-XXNOHOLES"))
    )
    (comp (ref "K13")
      (value "E")
      (footprint "eagle-import:B3F-40XXNOHOLE")
      (libsource (lib "eagle-import") (part "40-XXNOHOLES"))
    )
    (comp (ref "K14")
      (value "R")
      (footprint "eagle-import:B3F-40XXNOHOLE")
      (libsource (lib "eagle-import") (part "40-XXNOHOLES"))
    )
    (comp (ref "K15")
      (value "T")
      (footprint "eagle-import:B3F-40XXNOHOLE")
      (libsource (lib "eagle-import") (part "40-XXNOHOLES"))
    )
    (comp (ref "K16")
      (value "Y")
      (footprint "eagle-import:B3F-40XXNOHOLE")
      (libsource (lib "eagle-import") (part "40-XXNOHOLES"))
    )
    (comp (ref "K17")
      (value "U")
      (footprint "eagle-import:B3F-40XXNOHOLE")
      (libsource (lib "eagle-import") (part "40-XXNOHOLES"))
    )
    (comp (ref "K18")
      (value "I")
      (footprint "eagle-import:B3F-40XXNOHOLE")
      (libsource (lib "eagle-import") (part "40-XXNOHOLES"))
    )
    (comp (ref "K19")
      (value "O")
      (footprint "eagle-import:B3F-40XXNOHOLE")
      (libsource (lib "eagle-import") (part "40-XXNOHOLES"))
    )
    (comp (ref "K20")
      (value "P")
      (footprint "eagle-import:B3F-40XXNOHOLE")
      (libsource (lib "eagle-import") (part "40-XXNOHOLES"))
    )
    (comp (ref "K21")
      (value "A")
      (footprint "eagle-import:B3F-40XXNOHOLE")
      (libsource (lib "eagle-import") (part "40-XXNOHOLES"))
    )
    (comp (ref "K22")
      (value "S")
      (footprint "eagle-import:B3F-40XXNOHOLE")
      (libsource (lib "eagle-import") (part "40-XXNOHOLES"))
    )
    (comp (ref "K23")
      (value "D")
      (footprint "eagle-import:B3F-40XXNOHOLE")
      (libsource (lib "eagle-import") (part "40-XXNOHOLES"))
    )
    (comp (ref "K24")
      (value "F")
      (footprint "eagle-import:B3F-40XXNOHOLE")
      (libsource (lib "eagle-import") (part "40-XXNOHOLES"))
    )
    (comp (ref "K25")
      (value "G")
      (footprint "eagle-import:B3F-40XXNOHOLE")
      (libsource (lib "eagle-import") (part "40-XXNOHOLES"))
    )
    (comp (ref "K26")
      (value "H")
      (footprint "eagle-import:B3F-40XXNOHOLE")
      (libsource (lib "eagle-import") (part "40-XXNOHOLES"))
    )
    (comp (ref "K27")
      (value "J")
      (footprint "eagle-import:B3F-40XXNOHOLE")
      (libsource (lib "eagle-import") (part "40-XXNOHOLES"))
    )
    (comp (ref "K28")
      (value "K")
      (footprint "eagle-import:B3F-40XXNOHOLE")
      (libsource (lib "eagle-import") (part "40-XXNOHOLES"))
    )
    (comp (ref "K29")
      (value "L")
      (footprint "eagle-import:B3F-40XXNOHOLE")
      (libsource (lib "eagle-import") (part "40-XXNOHOLES"))
    )
    (comp (ref "K30")
      (value "ENTER")
      (footprint "eagle-import:B3F-40XXNOHOLE")
      (libsource (lib "eagle-import") (part "40-XXNOHOLES"))
    )
    (comp (ref "K31")
      (value "SHIFT")
      (footprint "eagle-import:B3F-40XXNOHOLE")
      (libsource (lib "eagle-import") (part "40-XXNOHOLES"))
    )
    (comp (ref "K32")
      (value "SYMBOL")
      (footprint "eagle-import:B3F-40XXNOHOLE")
      (libsource (lib "eagle-import") (part "40-XXNOHOLES"))
    )
    (comp (ref "K33")
      (value "Z")
      (footprint "eagle-import:B3F-40XXNOHOLE")
      (libsource (lib "eagle-import") (part "40-XXNOHOLES"))
    )
    (comp (ref "K34")
      (value "X")
      (footprint "eagle-import:B3F-40XXNOHOLE")
      (libsource (lib "eagle-import") (part "40-XXNOHOLES"))
    )
    (comp (ref "K35")
      (value "C")
      (footprint "eagle-import:B3F-40XXNOHOLE")
      (libsource (lib "eagle-import") (part "40-XXNOHOLES"))
    )
    (comp (ref "K36")
      (value "V")
      (footprint "eagle-import:B3F-40XXNOHOLE")
      (libsource (lib "eagle-import") (part "40-XXNOHOLES"))
    )
    (comp (ref "K37")
      (value "B")
      (footprint "eagle-import:B3F-40XXNOHOLE")
      (libsource (lib "eagle-import") (part "40-XXNOHOLES"))
    )
    (comp (ref "K38")
      (value "N")
      (footprint "eagle-import:B3F-40XXNOHOLE")
      (libsource (lib "eagle-import") (part "40-XXNOHOLES"))
    )
    (comp (ref "K39")
      (value "M")
      (footprint "eagle-import:B3F-40XXNOHOLE")
      (libsource (lib "eagle-import") (part "40-XXNOHOLES"))
    )
    (comp (ref "K40")
      (value "SPACE")
      (footprint "eagle-import:B3F-40XXNOHOLE")
      (libsource (lib "eagle-import") (part "40-XXNOHOLES"))
    )
    (comp (ref "K41")
      (value "SPACE")
      (footprint "eagle-import:B3F-40XXNOHOLE")
      (libsource (lib "eagle-import") (part "40-XXNOHOLES"))
    )
    (comp (ref "LED1")
      (value "POWER")
      (footprint "eagle-import:LED3MM")
      (libsource (lib "eagle-import") (part "LED3MM"))
    )
    (comp (ref "LED2")
      (value "ACE81")
      (footprint "eagle-import:LED3MM")
      (libsource (lib "eagle-import") (part "LED3MM"))
    )
    (comp (ref "LS1")
      (value "F/QMX")
      (footprint "eagle-import:F_QMX")
      (libsource (lib "eagle-import") (part "F/QMX"))
    )
    (comp (ref "MIC")
      (value "PJ302M")
      (footprint "eagle-import:PJ302M")
      (libsource (lib "eagle-import") (part "PJ302M"))
    )
    (comp (ref "POWER")
      (value "PJ302M")
      (footprint "eagle-import:PJ302M")
      (libsource (lib "eagle-import") (part "PJ302M"))
    )
    (comp (ref "Q1")
      (value "2N3904")
      (footprint "eagle-import:TO92")
      (libsource (lib "eagle-import") (part "2N3904"))
    )
    (comp (ref "Q3")
      (value "BC337")
      (footprint "eagle-import:TO92")
      (libsource (lib "eagle-import") (part "BC337"))
    )
    (comp (ref "R1")
      (value "1K")
      (footprint "eagle-import:0204_7")
      (libsource (lib "eagle-import") (part "R-EU_0204/7"))
    )
    (comp (ref "R2")
      (value "47K")
      (footprint "eagle-import:0204_7")
      (libsource (lib "eagle-import") (part "R-EU_0204/7"))
    )
    (comp (ref "R3")
      (value "500R")
      (footprint "eagle-import:B25P")
      (libsource (lib "eagle-import") (part "TRIM_EU-B25P"))
    )
    (comp (ref "R4")
      (value "1K")
      (footprint "eagle-import:B25P")
      (libsource (lib "eagle-import") (part "TRIM_EU-B25P"))
    )
    (comp (ref "R5")
      (value "12K")
      (footprint "eagle-import:0204_7")
      (libsource (lib "eagle-import") (part "R-EU_0204/7"))
    )
    (comp (ref "R6")
      (value "1K")
      (footprint "eagle-import:0204_7")
      (libsource (lib "eagle-import") (part "R-EU_0204/7"))
    )
    (comp (ref "R7")
      (value "33K")
      (footprint "eagle-import:0204_7")
      (libsource (lib "eagle-import") (part "R-EU_0204/7"))
    )
    (comp (ref "R8")
      (value "10K")
      (footprint "eagle-import:0204_7")
      (libsource (lib "eagle-import") (part "R-EU_0204/7"))
    )
    (comp (ref "R9")
      (value "22K")
      (footprint "eagle-import:0204_7")
      (libsource (lib "eagle-import") (part "R-EU_0204/7"))
    )
    (comp (ref "R10")
      (value "10K")
      (footprint "eagle-import:0204_7")
      (libsource (lib "eagle-import") (part "R-EU_0204/7"))
    )
    (comp (ref "R11")
      (value "1K")
      (footprint "eagle-import:0204_7")
      (libsource (lib "eagle-import") (part "R-EU_0204/7"))
    )
    (comp (ref "R12")
      (value "1K")
      (footprint "eagle-import:0204_7")
      (libsource (lib "eagle-import") (part "R-EU_0204/7"))
    )
    (comp (ref "R13")
      (value "1K")
      (footprint "eagle-import:0204_7")
      (libsource (lib "eagle-import") (part "R-EU_0204/7"))
    )
    (comp (ref "R14")
      (value "1K")
      (footprint "eagle-import:0204_7")
      (libsource (lib "eagle-import") (part "R-EU_0204/7"))
    )
    (comp (ref "R15")
      (value "1K")
      (footprint "eagle-import:0204_7")
      (libsource (lib "eagle-import") (part "R-EU_0204/7"))
    )
    (comp (ref "R16")
      (value "1K")
      (footprint "eagle-import:0204_7")
      (libsource (lib "eagle-import") (part "R-EU_0204/7"))
    )
    (comp (ref "R17")
      (value "1K")
      (footprint "eagle-import:0204_7")
      (libsource (lib "eagle-import") (part "R-EU_0204/7"))
    )
    (comp (ref "R18")
      (value "1K")
      (footprint "eagle-import:0204_7")
      (libsource (lib "eagle-import") (part "R-EU_0204/7"))
    )
    (comp (ref "R19")
      (value "1K")
      (footprint "eagle-import:0204_7")
      (libsource (lib "eagle-import") (part "R-EU_0204/7"))
    )
    (comp (ref "R20")
      (value "1K")
      (footprint "eagle-import:0204_7")
      (libsource (lib "eagle-import") (part "R-EU_0204/7"))
    )
    (comp (ref "R21")
      (value "1K")
      (footprint "eagle-import:0204V")
      (libsource (lib "eagle-import") (part "R-EU_0204/2V"))
    )
    (comp (ref "R22")
      (value "1K")
      (footprint "eagle-import:0204V")
      (libsource (lib "eagle-import") (part "R-EU_0204/2V"))
    )
    (comp (ref "R23")
      (value "1K")
      (footprint "eagle-import:0204V")
      (libsource (lib "eagle-import") (part "R-EU_0204/2V"))
    )
    (comp (ref "R24")
      (value "10K")
      (footprint "eagle-import:0204_7")
      (libsource (lib "eagle-import") (part "R-EU_0204/7"))
    )
    (comp (ref "R25")
      (value "220K")
      (footprint "eagle-import:0204_7")
      (libsource (lib "eagle-import") (part "R-EU_0204/7"))
    )
    (comp (ref "R26")
      (value "330")
      (footprint "eagle-import:0204_7")
      (libsource (lib "eagle-import") (part "R-EU_0204/7"))
    )
    (comp (ref "R27")
      (value "10K")
      (footprint "eagle-import:0204_7")
      (libsource (lib "eagle-import") (part "R-EU_0204/7"))
    )
    (comp (ref "R28")
      (value "680")
      (footprint "eagle-import:0204_7")
      (libsource (lib "eagle-import") (part "R-EU_0204/7"))
    )
    (comp (ref "R29")
      (value "680")
      (footprint "eagle-import:0204_7")
      (libsource (lib "eagle-import") (part "R-EU_0204/7"))
    )
    (comp (ref "R30")
      (value "4k7")
      (footprint "eagle-import:0204_7")
      (libsource (lib "eagle-import") (part "R-EU_0204/7"))
    )
    (comp (ref "R31")
      (value "4K7")
      (footprint "eagle-import:0204_7")
      (libsource (lib "eagle-import") (part "R-EU_0204/7"))
    )
    (comp (ref "R32")
      (value "200")
      (footprint "eagle-import:0204_7")
      (libsource (lib "eagle-import") (part "R-EU_0204/7"))
    )
    (comp (ref "R33")
      (value "200")
      (footprint "eagle-import:0204_7")
      (libsource (lib "eagle-import") (part "R-EU_0204/7"))
    )
    (comp (ref "R34")
      (value "75")
      (footprint "eagle-import:0204_7")
      (libsource (lib "eagle-import") (part "R-EU_0204/7"))
    )
    (comp (ref "R35")
      (value "300")
      (footprint "eagle-import:0204_7")
      (libsource (lib "eagle-import") (part "R-EU_0204/7"))
    )
    (comp (ref "R36")
      (value "4K7")
      (footprint "eagle-import:0207_10")
      (libsource (lib "eagle-import") (part "R-EU_0207/10"))
    )
    (comp (ref "R37")
      (value "4K7")
      (footprint "eagle-import:0207_10")
      (libsource (lib "eagle-import") (part "R-EU_0207/10"))
    )
    (comp (ref "R38")
      (value "4K7")
      (footprint "eagle-import:0207_10")
      (libsource (lib "eagle-import") (part "R-EU_0207/10"))
    )
    (comp (ref "R39")
      (value "10K")
      (footprint "eagle-import:0204_7")
      (libsource (lib "eagle-import") (part "R-EU_0204/7"))
    )
    (comp (ref "R40")
      (value "4K7")
      (footprint "eagle-import:0207_10")
      (libsource (lib "eagle-import") (part "R-EU_0207/10"))
    )
    (comp (ref "R41")
      (value "4K7")
      (footprint "eagle-import:0207_10")
      (libsource (lib "eagle-import") (part "R-EU_0207/10"))
    )
    (comp (ref "R42")
      (value "1K")
      (footprint "eagle-import:0204_7")
      (libsource (lib "eagle-import") (part "R-EU_0204/7"))
    )
    (comp (ref "R43")
      (value "10K")
      (footprint "eagle-import:0204_7")
      (libsource (lib "eagle-import") (part "R-EU_0204/7"))
    )
    (comp (ref "R44")
      (value "1K")
      (footprint "eagle-import:B25P")
      (libsource (lib "eagle-import") (part "TRIM_EU-B25P"))
    )
    (comp (ref "R100")
      (value "1K")
      (footprint "eagle-import:0204V")
      (libsource (lib "eagle-import") (part "R-US_0204/2V"))
    )
    (comp (ref "R101")
      (value "1K")
      (footprint "eagle-import:0204V")
      (libsource (lib "eagle-import") (part "R-US_0204/2V"))
    )
    (comp (ref "R102")
      (value "1K")
      (footprint "eagle-import:0204V")
      (libsource (lib "eagle-import") (part "R-US_0204/2V"))
    )
    (comp (ref "R103")
      (value "1K")
      (footprint "eagle-import:0204V")
      (libsource (lib "eagle-import") (part "R-US_0204/2V"))
    )
    (comp (ref "R104")
      (value "1K")
      (footprint "eagle-import:0204V")
      (libsource (lib "eagle-import") (part "R-US_0204/2V"))
    )
    (comp (ref "R105")
      (value "1K")
      (footprint "eagle-import:0204V")
      (libsource (lib "eagle-import") (part "R-US_0204/2V"))
    )
    (comp (ref "R106")
      (value "1K")
      (footprint "eagle-import:0204V")
      (libsource (lib "eagle-import") (part "R-US_0204/2V"))
    )
    (comp (ref "R107")
      (value "1K")
      (footprint "eagle-import:0204V")
      (libsource (lib "eagle-import") (part "R-US_0204/2V"))
    )
    (comp (ref "R200")
      (value "1K")
      (footprint "eagle-import:0204V")
      (libsource (lib "eagle-import") (part "R-US_0204/2V"))
    )
    (comp (ref "R201")
      (value "1K")
      (footprint "eagle-import:0204V")
      (libsource (lib "eagle-import") (part "R-US_0204/2V"))
    )
    (comp (ref "R202")
      (value "1K")
      (footprint "eagle-import:0204V")
      (libsource (lib "eagle-import") (part "R-US_0204/2V"))
    )
    (comp (ref "R203")
      (value "1K")
      (footprint "eagle-import:0204V")
      (libsource (lib "eagle-import") (part "R-US_0204/2V"))
    )
    (comp (ref "R204")
      (value "1K")
      (footprint "eagle-import:0204V")
      (libsource (lib "eagle-import") (part "R-US_0204/2V"))
    )
    (comp (ref "R205")
      (value "1K")
      (footprint "eagle-import:0204V")
      (libsource (lib "eagle-import") (part "R-US_0204/2V"))
    )
    (comp (ref "R206")
      (value "1K")
      (footprint "eagle-import:0204V")
      (libsource (lib "eagle-import") (part "R-US_0204/2V"))
    )
    (comp (ref "R207")
      (value "1K")
      (footprint "eagle-import:0204V")
      (libsource (lib "eagle-import") (part "R-US_0204/2V"))
    )
    (comp (ref "RN1")
      (value "4K7")
      (footprint "eagle-import:RN-6")
      (libsource (lib "eagle-import") (part "RN05"))
    )
    (comp (ref "S1")
      (value "DP03")
      (footprint "eagle-import:DP-03")
      (fields (field (name "MPN") "MCDP03"))
      (libsource (lib "eagle-import") (part "DP03"))
    )
    (comp (ref "S2")
      (value "RESET")
      (footprint "eagle-import:B3F-31XX")
      (fields (field (name "MPN") "B3F-3100"))
      (libsource (lib "eagle-import") (part "31-XX"))
    )
    (comp (ref "SJ1")
      (value "NO OPAMP")
      (footprint "eagle-import:SJ")
      (libsource (lib "eagle-import") (part "SJ"))
    )
    (comp (ref "SJ2") (value "SJ") (footprint "eagle-import:SJ") (libsource (lib "eagle-import") (part "SJ")))
    (comp (ref "SJ3") (value "SJ") (footprint "eagle-import:SJ") (libsource (lib "eagle-import") (part "SJ")))
    (comp (ref "SJ4") (value "SJ") (footprint "eagle-import:SJ") (libsource (lib "eagle-import") (part "SJ")))
    (comp (ref "SJ5") (value "SJ") (footprint "eagle-import:SJ") (libsource (lib "eagle-import") (part "SJ")))
    (comp (ref "SJ6") (value "SJ") (footprint "eagle-import:SJ") (libsource (lib "eagle-import") (part "SJ")))
    (comp (ref "SJ7") (value "SJ") (footprint "eagle-import:SJ") (libsource (lib "eagle-import") (part "SJ")))
    (comp (ref "SJ8") (value "SJ") (footprint "eagle-import:SJ") (libsource (lib "eagle-import") (part "SJ")))
    (comp (ref "SJ9") (value "SJ") (footprint "eagle-import:SJ") (libsource (lib "eagle-import") (part "SJ")))
    (comp (ref "U$1")
      (value "40-XX-CARBON")
      (footprint "eagle-import:CARBONB3F")
      (libsource (lib "eagle-import") (part "40-XX-CARBON"))
    )
    (comp (ref "U$2")
      (value "40-XX-CARBON")
      (footprint "eagle-import:CARBONB3F")
      (libsource (lib "eagle-import") (part "40-XX-CARBON"))
    )
    (comp (ref "U$3")
      (value "40-XX-CARBON")
      (footprint "eagle-import:CARBONB3F")
      (libsource (lib "eagle-import") (part "40-XX-CARBON"))
    )
    (comp (ref "U$4")
      (value "40-XX-CARBON")
      (footprint "eagle-import:CARBONB3F")
      (libsource (lib "eagle-import") (part "40-XX-CARBON"))
    )
    (comp (ref "U$5")
      (value "40-XX-CARBON")
      (footprint "eagle-import:CARBONB3F")
      (libsource (lib "eagle-import") (part "40-XX-CARBON"))
    )
    (comp (ref "U$6")
      (value "40-XX-CARBON")
      (footprint "eagle-import:CARBONB3F")
      (libsource (lib "eagle-import") (part "40-XX-CARBON"))
    )
    (comp (ref "U$7")
      (value "40-XX-CARBON")
      (footprint "eagle-import:CARBONB3F")
      (libsource (lib "eagle-import") (part "40-XX-CARBON"))
    )
    (comp (ref "U$8")
      (value "40-XX-CARBON")
      (footprint "eagle-import:CARBONB3F")
      (libsource (lib "eagle-import") (part "40-XX-CARBON"))
    )
    (comp (ref "U$9")
      (value "40-XX-CARBON")
      (footprint "eagle-import:CARBONB3F")
      (libsource (lib "eagle-import") (part "40-XX-CARBON"))
    )
    (comp (ref "U$10")
      (value "40-XX-CARBON")
      (footprint "eagle-import:CARBONB3F")
      (libsource (lib "eagle-import") (part "40-XX-CARBON"))
    )
    (comp (ref "U$11")
      (value "40-XX-CARBON")
      (footprint "eagle-import:CARBONB3F")
      (libsource (lib "eagle-import") (part "40-XX-CARBON"))
    )
    (comp (ref "U$12")
      (value "40-XX-CARBON")
      (footprint "eagle-import:CARBONB3F")
      (libsource (lib "eagle-import") (part "40-XX-CARBON"))
    )
    (comp (ref "U$13")
      (value "40-XX-CARBON")
      (footprint "eagle-import:CARBONB3F")
      (libsource (lib "eagle-import") (part "40-XX-CARBON"))
    )
    (comp (ref "U$14")
      (value "40-XX-CARBON")
      (footprint "eagle-import:CARBONB3F")
      (libsource (lib "eagle-import") (part "40-XX-CARBON"))
    )
    (comp (ref "U$15")
      (value "40-XX-CARBON")
      (footprint "eagle-import:CARBONB3F")
      (libsource (lib "eagle-import") (part "40-XX-CARBON"))
    )
    (comp (ref "U$16")
      (value "40-XX-CARBON")
      (footprint "eagle-import:CARBONB3F")
      (libsource (lib "eagle-import") (part "40-XX-CARBON"))
    )
    (comp (ref "U$17")
      (value "40-XX-CARBON")
      (footprint "eagle-import:CARBONB3F")
      (libsource (lib "eagle-import") (part "40-XX-CARBON"))
    )
    (comp (ref "U$18")
      (value "40-XX-CARBON")
      (footprint "eagle-import:CARBONB3F")
      (libsource (lib "eagle-import") (part "40-XX-CARBON"))
    )
    (comp (ref "U$19")
      (value "40-XX-CARBON")
      (footprint "eagle-import:CARBONB3F")
      (libsource (lib "eagle-import") (part "40-XX-CARBON"))
    )
    (comp (ref "U$20")
      (value "40-XX-CARBON")
      (footprint "eagle-import:CARBONB3F")
      (libsource (lib "eagle-import") (part "40-XX-CARBON"))
    )
    (comp (ref "U$21")
      (value "40-XX-CARBON")
      (footprint "eagle-import:CARBONB3F")
      (libsource (lib "eagle-import") (part "40-XX-CARBON"))
    )
    (comp (ref "U$22")
      (value "40-XX-CARBON")
      (footprint "eagle-import:CARBONB3F")
      (libsource (lib "eagle-import") (part "40-XX-CARBON"))
    )
    (comp (ref "U$23")
      (value "40-XX-CARBON")
      (footprint "eagle-import:CARBONB3F")
      (libsource (lib "eagle-import") (part "40-XX-CARBON"))
    )
    (comp (ref "U$24")
      (value "40-XX-CARBON")
      (footprint "eagle-import:CARBONB3F")
      (libsource (lib "eagle-import") (part "40-XX-CARBON"))
    )
    (comp (ref "U$25")
      (value "40-XX-CARBON")
      (footprint "eagle-import:CARBONB3F")
      (libsource (lib "eagle-import") (part "40-XX-CARBON"))
    )
    (comp (ref "U$26")
      (value "40-XX-CARBON")
      (footprint "eagle-import:CARBONB3F")
      (libsource (lib "eagle-import") (part "40-XX-CARBON"))
    )
    (comp (ref "U$27")
      (value "40-XX-CARBON")
      (footprint "eagle-import:CARBONB3F")
      (libsource (lib "eagle-import") (part "40-XX-CARBON"))
    )
    (comp (ref "U$28")
      (value "40-XX-CARBON")
      (footprint "eagle-import:CARBONB3F")
      (libsource (lib "eagle-import") (part "40-XX-CARBON"))
    )
    (comp (ref "U$29")
      (value "40-XX-CARBON")
      (footprint "eagle-import:CARBONB3F")
      (libsource (lib "eagle-import") (part "40-XX-CARBON"))
    )
    (comp (ref "U$30")
      (value "40-XX-CARBON")
      (footprint "eagle-import:CARBONB3F")
      (libsource (lib "eagle-import") (part "40-XX-CARBON"))
    )
    (comp (ref "U$31")
      (value "40-XX-CARBON")
      (footprint "eagle-import:CARBONB3F")
      (libsource (lib "eagle-import") (part "40-XX-CARBON"))
    )
    (comp (ref "U$32")
      (value "40-XX-CARBON")
      (footprint "eagle-import:CARBONB3F")
      (libsource (lib "eagle-import") (part "40-XX-CARBON"))
    )
    (comp (ref "U$33")
      (value "40-XX-CARBON")
      (footprint "eagle-import:CARBONB3F")
      (libsource (lib "eagle-import") (part "40-XX-CARBON"))
    )
    (comp (ref "U$34")
      (value "40-XX-CARBON")
      (footprint "eagle-import:CARBONB3F")
      (libsource (lib "eagle-import") (part "40-XX-CARBON"))
    )
    (comp (ref "U$35")
      (value "40-XX-CARBON")
      (footprint "eagle-import:CARBONB3F")
      (libsource (lib "eagle-import") (part "40-XX-CARBON"))
    )
    (comp (ref "U$36")
      (value "40-XX-CARBON")
      (footprint "eagle-import:CARBONB3F")
      (libsource (lib "eagle-import") (part "40-XX-CARBON"))
    )
    (comp (ref "U$37")
      (value "40-XX-CARBON")
      (footprint "eagle-import:CARBONB3F")
      (libsource (lib "eagle-import") (part "40-XX-CARBON"))
    )
    (comp (ref "U$38")
      (value "40-XX-CARBON")
      (footprint "eagle-import:CARBONB3F")
      (libsource (lib "eagle-import") (part "40-XX-CARBON"))
    )
    (comp (ref "U$39")
      (value "40-XX-CARBON")
      (footprint "eagle-import:CARBONB3F")
      (libsource (lib "eagle-import") (part "40-XX-CARBON"))
    )
    (comp (ref "U$40")
      (value "40-XX-CARBON")
      (footprint "eagle-import:CARBONB3F")
      (libsource (lib "eagle-import") (part "40-XX-CARBON"))
    )
    (comp (ref "U$41")
      (value "40-XX-CARBON")
      (footprint "eagle-import:CARBONB3F")
      (libsource (lib "eagle-import") (part "40-XX-CARBON"))
    )
    (comp (ref "U$42")
      (value "40-XX-CARBON")
      (footprint "eagle-import:CARBONB3F")
      (libsource (lib "eagle-import") (part "40-XX-CARBON"))
    )
    (comp (ref "U1")
      (value "7805")
      (footprint "eagle-import:TO220V")
      (libsource (lib "eagle-import") (part "78TV05"))
    )
    (comp (ref "U2")
      (value "MAX4390EUK")
      (footprint "eagle-import:SOT95P280X145-5N")
      (fields (field (name "MF") "Maxim Integrated") (field (name "MP") "MAX4390EUK+T"))
      (libsource (lib "eagle-import") (part "MAX4390EUK"))
    )
    (comp (ref "X1")
      (value "6.5MHz")
      (footprint "eagle-import:HC49U")
      (libsource (lib "eagle-import") (part "8M10AHC49T"))
    )
    (comp (ref "X2")
      (value "CON-CONRAD_736880-49")
      (footprint "eagle-import:CON-CONRAD_736880-49")
      (libsource (lib "eagle-import") (part "CON-CONRAD_736880-49"))
    )
    (comp (ref "Z0")
      (value "Z80")
      (footprint "eagle-import:DIL40")
      (libsource (lib "eagle-import") (part "Z80CPU"))
    )
    (comp (ref "Z1")
      (value "74LS74N")
      (footprint "eagle-import:DIL14")
      (libsource (lib "eagle-import") (part "7474NLS"))
    )
    (comp (ref "Z1-2")
      (value "27C512")
      (footprint "eagle-import:DIL28-6")
      (libsource (lib "eagle-import") (part "27512G"))
    )
    (comp (ref "Z3-4")
      (value "CY62256LL-PC")
      (footprint "eagle-import:DIL28-6")
      (libsource (lib "eagle-import") (part "CY62256LL-?PC"))
    )
    (comp (ref "Z5-6")
      (value "CY62256LL-PC")
      (footprint "eagle-import:DIL28-6")
      (libsource (lib "eagle-import") (part "CY62256LL-?PC"))
    )
    (comp (ref "Z7-8")
      (value "CY62256LL-PC")
      (footprint "eagle-import:DIL28-6")
      (libsource (lib "eagle-import") (part "CY62256LL-?PC"))
    )
    (comp (ref "Z9")
      (value "74LS393N")
      (footprint "eagle-import:DIL14")
      (libsource (lib "eagle-import") (part "74393NLS"))
    )
    (comp (ref "Z10")
      (value "74LS393N")
      (footprint "eagle-import:DIL14")
      (libsource (lib "eagle-import") (part "74393NLS"))
    )
    (comp (ref "Z11")
      (value "74LS393N")
      (footprint "eagle-import:DIL14")
      (libsource (lib "eagle-import") (part "74393NLS"))
    )
    (comp (ref "Z14")
      (value "74367N")
      (footprint "eagle-import:DIL16")
      (libsource (lib "eagle-import") (part "74367N"))
    )
    (comp (ref "Z15")
      (value "74367N")
      (footprint "eagle-import:DIL16")
      (libsource (lib "eagle-import") (part "74367N"))
    )
    (comp (ref "Z16")
      (value "74367N")
      (footprint "eagle-import:DIL16")
      (libsource (lib "eagle-import") (part "74367N"))
    )
    (comp (ref "Z17")
      (value "74367N")
      (footprint "eagle-import:DIL16")
      (libsource (lib "eagle-import") (part "74367N"))
    )
    (comp (ref "Z18")
      (value "74367N")
      (footprint "eagle-import:DIL16")
      (libsource (lib "eagle-import") (part "74367N"))
    )
    (comp (ref "Z19")
      (value "74LS00N")
      (footprint "eagle-import:DIL14")
      (libsource (lib "eagle-import") (part "7400NLS"))
    )
    (comp (ref "Z20")
      (value "74LS08N")
      (footprint "eagle-import:DIL14")
      (libsource (lib "eagle-import") (part "7408NLS"))
    )
    (comp (ref "Z21")
      (value "74LS11N")
      (footprint "eagle-import:DIL14")
      (libsource (lib "eagle-import") (part "7411NLS"))
    )
    (comp (ref "Z22")
      (value "74LS11N")
      (footprint "eagle-import:DIL14")
      (libsource (lib "eagle-import") (part "7411NLS"))
    )
    (comp (ref "Z23")
      (value "74LS86N")
      (footprint "eagle-import:DIL14")
      (libsource (lib "eagle-import") (part "7486NLS"))
    )
    (comp (ref "Z24")
      (value "74LS02N")
      (footprint "eagle-import:DIL14")
      (libsource (lib "eagle-import") (part "7402NLS"))
    )
    (comp (ref "Z25")
      (value "74LS02N")
      (footprint "eagle-import:DIL14")
      (libsource (lib "eagle-import") (part "7402NLS"))
    )
    (comp (ref "Z26")
      (value "74LS32N")
      (footprint "eagle-import:DIL14")
      (libsource (lib "eagle-import") (part "7432NLS"))
    )
    (comp (ref "Z27")
      (value "74LS74N")
      (footprint "eagle-import:DIL14")
      (libsource (lib "eagle-import") (part "7474NLS"))
    )
    (comp (ref "Z28")
      (value "74LS166N")
      (footprint "eagle-import:DIL16")
      (libsource (lib "eagle-import") (part "74166NLS"))
    )
    (comp (ref "Z29")
      (value "74LS138N")
      (footprint "eagle-import:DIL16")
      (libsource (lib "eagle-import") (part "74138NLS"))
    )
    (comp (ref "Z30")
      (value "74LS00N")
      (footprint "eagle-import:DIL14")
      (libsource (lib "eagle-import") (part "7400NLS"))
    )
    (comp (ref "Z31")
      (value "74LS11N")
      (footprint "eagle-import:DIL14")
      (libsource (lib "eagle-import") (part "7411NLS"))
    )
    (comp (ref "Z40")
      (value "ATF16V8BP3")
      (footprint "eagle-import:DIL20")
      (fields (field (name "MPN") "ATF16V8CZ-15PU"))
      (libsource (lib "eagle-import") (part "ATF16V8BP3"))
    )
    (comp (ref "Z41")
      (value "74LS00N")
      (footprint "eagle-import:DIL14")
      (libsource (lib "eagle-import") (part "7400NLS"))
    )
  )
  (nets
    (net (code "3") (name "/9V") (class "Default")
      (node (ref "3A") (pin "1") (pinfunction "P_1") (pintype "passive"))
      (node (ref "C10") (pin "1") (pinfunction "1_1") (pintype "passive"))
      (node (ref "C11") (pin "+") (pinfunction "+_+") (pintype "passive"))
      (node (ref "C9") (pin "+") (pinfunction "+_+") (pintype "passive"))
      (node (ref "JP7") (pin "1") (pinfunction "1_1") (pintype "passive"))
      (node (ref "U1") (pin "1") (pinfunction "VI_1") (pintype "input"))
    )
    (net (code "4") (name "/A0") (class "Default")
      (node (ref "19A") (pin "1") (pinfunction "P_1") (pintype "passive"))
      (node (ref "JP9") (pin "11") (pinfunction "11_11") (pintype "passive"))
      (node (ref "Z0") (pin "30") (pinfunction "A0_30") (pintype "output"))
      (node (ref "Z1-2") (pin "10") (pinfunction "A0_10") (pintype "input"))
      (node (ref "Z15") (pin "2") (pinfunction "1A1_2") (pintype "input"))
      (node (ref "Z18") (pin "10") (pinfunction "1A4_10") (pintype "input"))
      (node (ref "Z26") (pin "5") (pinfunction "I1_5") (pintype "input"))
      (node (ref "Z3-4") (pin "21") (pinfunction "A0_21") (pintype "input"))
    )
    (net (code "5") (name "/A1") (class "Default")
      (node (ref "19B") (pin "1") (pinfunction "P_1") (pintype "passive"))
      (node (ref "JP9") (pin "10") (pinfunction "10_10") (pintype "passive"))
      (node (ref "Z0") (pin "31") (pinfunction "A1_31") (pintype "output"))
      (node (ref "Z1-2") (pin "9") (pinfunction "A1_9") (pintype "input"))
      (node (ref "Z15") (pin "4") (pinfunction "1A2_4") (pintype "input"))
      (node (ref "Z18") (pin "6") (pinfunction "1A3_6") (pintype "input"))
      (node (ref "Z3-4") (pin "23") (pinfunction "A1_23") (pintype "input"))
    )
    (net (code "6") (name "/A2") (class "Default")
      (node (ref "14A") (pin "1") (pinfunction "P_1") (pintype "passive"))
      (node (ref "JP9") (pin "9") (pinfunction "9_9") (pintype "passive"))
      (node (ref "Z0") (pin "32") (pinfunction "A2_32") (pintype "output"))
      (node (ref "Z1-2") (pin "8") (pinfunction "A2_8") (pintype "input"))
      (node (ref "Z15") (pin "6") (pinfunction "1A3_6") (pintype "input"))
      (node (ref "Z18") (pin "4") (pinfunction "1A2_4") (pintype "input"))
      (node (ref "Z3-4") (pin "24") (pinfunction "A2_24") (pintype "input"))
    )
    (net (code "7") (name "/A3") (class "Default")
      (node (ref "18B") (pin "1") (pinfunction "P_1") (pintype "passive"))
      (node (ref "JP9") (pin "8") (pinfunction "8_8") (pintype "passive"))
      (node (ref "Z0") (pin "33") (pinfunction "A3_33") (pintype "output"))
      (node (ref "Z1-2") (pin "7") (pinfunction "A3_7") (pintype "input"))
      (node (ref "Z15") (pin "10") (pinfunction "1A4_10") (pintype "input"))
      (node (ref "Z18") (pin "2") (pinfunction "1A1_2") (pintype "input"))
      (node (ref "Z3-4") (pin "25") (pinfunction "A3_25") (pintype "input"))
    )
    (net (code "8") (name "/A4") (class "Default")
      (node (ref "17B") (pin "1") (pinfunction "P_1") (pintype "passive"))
      (node (ref "JP9") (pin "7") (pinfunction "7_7") (pintype "passive"))
      (node (ref "Z0") (pin "34") (pinfunction "A4_34") (pintype "output"))
      (node (ref "Z1-2") (pin "6") (pinfunction "A4_6") (pintype "input"))
      (node (ref "Z15") (pin "12") (pinfunction "2A1_12") (pintype "input"))
      (node (ref "Z17") (pin "14") (pinfunction "2A2_14") (pintype "input"))
      (node (ref "Z3-4") (pin "26") (pinfunction "A4_26") (pintype "input"))
    )
    (net (code "9") (name "/A5") (class "Default")
      (node (ref "16B") (pin "1") (pinfunction "P_1") (pintype "passive"))
      (node (ref "JP9") (pin "6") (pinfunction "6_6") (pintype "passive"))
      (node (ref "Z0") (pin "35") (pinfunction "A5_35") (pintype "output"))
      (node (ref "Z1-2") (pin "5") (pinfunction "A5_5") (pintype "input"))
      (node (ref "Z15") (pin "14") (pinfunction "2A2_14") (pintype "input"))
      (node (ref "Z17") (pin "12") (pinfunction "2A1_12") (pintype "input"))
      (node (ref "Z3-4") (pin "1") (pinfunction "A5_1") (pintype "input"))
    )
    (net (code "10") (name "/A6") (class "Default")
      (node (ref "15B") (pin "1") (pinfunction "P_1") (pintype "passive"))
      (node (ref "JP9") (pin "5") (pinfunction "5_5") (pintype "passive"))
      (node (ref "Z0") (pin "36") (pinfunction "A6_36") (pintype "output"))
      (node (ref "Z1-2") (pin "4") (pinfunction "A6_4") (pintype "input"))
      (node (ref "Z16") (pin "2") (pinfunction "1A1_2") (pintype "input"))
      (node (ref "Z17") (pin "10") (pinfunction "1A4_10") (pintype "input"))
      (node (ref "Z3-4") (pin "2") (pinfunction "A6_2") (pintype "input"))
    )
    (net (code "11") (name "/A7") (class "Default")
      (node (ref "18A") (pin "1") (pinfunction "P_1") (pintype "passive"))
      (node (ref "JP9") (pin "4") (pinfunction "4_4") (pintype "passive"))
      (node (ref "Z0") (pin "37") (pinfunction "A7_37") (pintype "output"))
      (node (ref "Z1-2") (pin "3") (pinfunction "A7_3") (pintype "input"))
      (node (ref "Z16") (pin "4") (pinfunction "1A2_4") (pintype "input"))
      (node (ref "Z17") (pin "6") (pinfunction "1A3_6") (pintype "input"))
      (node (ref "Z3-4") (pin "3") (pinfunction "A7_3") (pintype "input"))
    )
    (net (code "12") (name "/A8") (class "Default")
      (node (ref "17A") (pin "1") (pinfunction "P_1") (pintype "passive"))
      (node (ref "D10") (pin "C") (pinfunction "C_C") (pintype "passive"))
      (node (ref "JP9") (pin "3") (pinfunction "3_3") (pintype "passive"))
      (node (ref "Z0") (pin "38") (pinfunction "A8_38") (pintype "output"))
      (node (ref "Z1-2") (pin "25") (pinfunction "A8_25") (pintype "input"))
      (node (ref "Z16") (pin "6") (pinfunction "1A3_6") (pintype "input"))
      (node (ref "Z17") (pin "4") (pinfunction "1A2_4") (pintype "input"))
      (node (ref "Z3-4") (pin "4") (pinfunction "A8_4") (pintype "input"))
    )
    (net (code "13") (name "/A9") (class "Default")
      (node (ref "16A") (pin "1") (pinfunction "P_1") (pintype "passive"))
      (node (ref "D9") (pin "C") (pinfunction "C_C") (pintype "passive"))
      (node (ref "JP9") (pin "2") (pinfunction "2_2") (pintype "passive"))
      (node (ref "Z0") (pin "39") (pinfunction "A9_39") (pintype "output"))
      (node (ref "Z1-2") (pin "24") (pinfunction "A9_24") (pintype "input"))
      (node (ref "Z16") (pin "10") (pinfunction "1A4_10") (pintype "input"))
      (node (ref "Z17") (pin "2") (pinfunction "1A1_2") (pintype "input"))
      (node (ref "Z3-4") (pin "5") (pinfunction "A9_5") (pintype "input"))
    )
    (net (code "14") (name "/A10") (class "Default")
      (node (ref "15A") (pin "1") (pinfunction "P_1") (pintype "passive"))
      (node (ref "D8") (pin "C") (pinfunction "C_C") (pintype "passive"))
      (node (ref "JP9") (pin "1") (pinfunction "1_1") (pintype "passive"))
      (node (ref "Z0") (pin "40") (pinfunction "A10_40") (pintype "output"))
      (node (ref "Z1-2") (pin "21") (pinfunction "A10_21") (pintype "input"))
      (node (ref "Z19") (pin "9") (pinfunction "I0_9") (pintype "input"))
      (node (ref "Z30") (pin "9") (pinfunction "I0_9") (pintype "input"))
    )
    (net (code "15") (name "/A10'") (class "Default")
      (node (ref "Z3-4") (pin "6") (pinfunction "A10_6") (pintype "input"))
      (node (ref "Z30") (pin "8") (pinfunction "O_8") (pintype "output"))
    )
    (net (code "16") (name "/A11") (class "Default")
      (node (ref "6A") (pin "1") (pinfunction "P_1") (pintype "passive"))
      (node (ref "D7") (pin "C") (pinfunction "C_C") (pintype "passive"))
      (node (ref "JP2") (pin "1") (pinfunction "1_1") (pintype "passive"))
      (node (ref "Z0") (pin "1") (pinfunction "A11_1") (pintype "output"))
      (node (ref "Z1-2") (pin "23") (pinfunction "A11_23") (pintype "input"))
      (node (ref "Z24") (pin "6") (pinfunction "I1_6") (pintype "input"))
      (node (ref "Z30") (pin "12") (pinfunction "I0_12") (pintype "input"))
    )
    (net (code "17") (name "/A11'") (class "Default")
      (node (ref "Z3-4") (pin "7") (pinfunction "A11_7") (pintype "input"))
      (node (ref "Z30") (pin "11") (pinfunction "O_11") (pintype "output"))
    )
    (net (code "18") (name "/A12") (class "Default")
      (node (ref "7A") (pin "1") (pinfunction "P_1") (pintype "passive"))
      (node (ref "D6") (pin "C") (pinfunction "C_C") (pintype "passive"))
      (node (ref "JP2") (pin "2") (pinfunction "2_2") (pintype "passive"))
      (node (ref "Z0") (pin "2") (pinfunction "A12_2") (pintype "output"))
      (node (ref "Z1-2") (pin "2") (pinfunction "A12_2") (pintype "input"))
      (node (ref "Z29") (pin "1") (pinfunction "A_1") (pintype "input"))
      (node (ref "Z3-4") (pin "8") (pinfunction "A12_8") (pintype "input"))
    )
    (net (code "19") (name "/A13") (class "Default")
      (node (ref "8A") (pin "1") (pinfunction "P_1") (pintype "passive"))
      (node (ref "D5") (pin "C") (pinfunction "C_C") (pintype "passive"))
      (node (ref "JP2") (pin "3") (pinfunction "3_3") (pintype "passive"))
      (node (ref "Z0") (pin "3") (pinfunction "A13_3") (pintype "output"))
      (node (ref "Z29") (pin "2") (pinfunction "B_2") (pintype "input"))
      (node (ref "Z3-4") (pin "9") (pinfunction "A13_9") (pintype "input"))
    )
    (net (code "20") (name "/A14") (class "Default")
      (node (ref "9A") (pin "1") (pinfunction "P_1") (pintype "passive"))
      (node (ref "D4") (pin "C") (pinfunction "C_C") (pintype "passive"))
      (node (ref "JP2") (pin "4") (pinfunction "4_4") (pintype "passive"))
      (node (ref "Z0") (pin "4") (pinfunction "A14_4") (pintype "output"))
      (node (ref "Z29") (pin "3") (pinfunction "C_3") (pintype "input"))
      (node (ref "Z3-4") (pin "10") (pinfunction "A14_10") (pintype "input"))
      (node (ref "Z30") (pin "10") (pinfunction "I1_10") (pintype "input"))
      (node (ref "Z30") (pin "13") (pinfunction "I1_13") (pintype "input"))
    )
    (net (code "21") (name "/A15") (class "Default")
      (node (ref "10A") (pin "1") (pinfunction "P_1") (pintype "passive"))
      (node (ref "D3") (pin "C") (pinfunction "C_C") (pintype "passive"))
      (node (ref "JP2") (pin "5") (pinfunction "5_5") (pintype "passive"))
      (node (ref "Z0") (pin "5") (pinfunction "A15_5") (pintype "output"))
      (node (ref "Z29") (pin "5") (pinfunction "G2B_5") (pintype "input"))
    )
    (net (code "22") (name "/ACE81_ENABLED") (class "Default")
      (node (ref "R29") (pin "2") (pinfunction "2_2") (pintype "passive"))
      (node (ref "R42") (pin "2") (pinfunction "2_2") (pintype "passive"))
      (node (ref "R43") (pin "2") (pinfunction "2_2") (pintype "passive"))
      (node (ref "S1") (pin "6") (pinfunction "6_6") (pintype "passive"))
      (node (ref "Z1-2") (pin "1") (pinfunction "A15_1") (pintype "input"))
      (node (ref "Z40") (pin "1") (pinfunction "CLK_1") (pintype "input"))
    )
    (net (code "23") (name "/CLK") (class "Default")
      (node (ref "C22") (pin "2") (pinfunction "2_2") (pintype "passive"))
      (node (ref "R44") (pin "E") (pinfunction "E_E") (pintype "passive"))
      (node (ref "R44") (pin "S") (pinfunction "S_S") (pintype "passive"))
      (node (ref "Z20") (pin "10") (pinfunction "I1_10") (pintype "input"))
      (node (ref "Z23") (pin "8") (pinfunction "O_8") (pintype "output"))
      (node (ref "Z9") (pin "1") (pinfunction "A_1") (pintype "input"))
    )
    (net (code "24") (name "/CNT0") (class "Default")
      (node (ref "Z22") (pin "5") (pinfunction "I2_5") (pintype "input"))
      (node (ref "Z30") (pin "4") (pinfunction "I0_4") (pintype "input"))
      (node (ref "Z30") (pin "5") (pinfunction "I1_5") (pintype "input"))
      (node (ref "Z9") (pin "3") (pinfunction "QA_3") (pintype "output"))
    )
    (net (code "25") (name "/CNT1") (class "Default")
      (node (ref "Z22") (pin "4") (pinfunction "I1_4") (pintype "input"))
      (node (ref "Z9") (pin "4") (pinfunction "QB_4") (pintype "output"))
    )
    (net (code "26") (name "/CNT2") (class "Default")
      (node (ref "Z22") (pin "3") (pinfunction "I0_3") (pintype "input"))
      (node (ref "Z41") (pin "5") (pinfunction "I1_5") (pintype "input"))
      (node (ref "Z9") (pin "5") (pinfunction "QC_5") (pintype "output"))
    )
    (net (code "27") (name "/CNT3") (class "Default")
      (node (ref "JP5") (pin "1") (pinfunction "1_1") (pintype "passive"))
      (node (ref "Z9") (pin "13") (pinfunction "A_13") (pintype "input"))
      (node (ref "Z9") (pin "6") (pinfunction "QD_6") (pintype "output"))
    )
    (net (code "28") (name "/CNT3'") (class "Default")
      (node (ref "JP5") (pin "2") (pinfunction "2_2") (pintype "passive"))
      (node (ref "R11") (pin "1") (pinfunction "1_1") (pintype "passive"))
    )
    (net (code "29") (name "/CNT4") (class "Default")
      (node (ref "JP10") (pin "1") (pinfunction "1_1") (pintype "passive"))
      (node (ref "Z10") (pin "1") (pinfunction "A_1") (pintype "input"))
      (node (ref "Z9") (pin "11") (pinfunction "QA_11") (pintype "output"))
    )
    (net (code "30") (name "/CNT4'") (class "Default")
      (node (ref "JP10") (pin "2") (pinfunction "2_2") (pintype "passive"))
      (node (ref "R12") (pin "1") (pinfunction "1_1") (pintype "passive"))
    )
    (net (code "31") (name "/CNT5") (class "Default")
      (node (ref "JP10") (pin "3") (pinfunction "1_3") (pintype "passive"))
      (node (ref "Z10") (pin "3") (pinfunction "QA_3") (pintype "output"))
      (node (ref "Z21") (pin "11") (pinfunction "I2_11") (pintype "input"))
      (node (ref "Z25") (pin "11") (pinfunction "I0_11") (pintype "input"))
      (node (ref "Z41") (pin "2") (pinfunction "I1_2") (pintype "input"))
    )
    (net (code "32") (name "/CNT5'") (class "Default")
      (node (ref "JP10") (pin "4") (pinfunction "2_4") (pintype "passive"))
      (node (ref "R13") (pin "1") (pinfunction "1_1") (pintype "passive"))
    )
    (net (code "33") (name "/CNT6") (class "Default")
      (node (ref "JP10") (pin "5") (pinfunction "1_5") (pintype "passive"))
      (node (ref "Z10") (pin "4") (pinfunction "QB_4") (pintype "output"))
      (node (ref "Z22") (pin "1") (pinfunction "I0_1") (pintype "input"))
    )
    (net (code "34") (name "/CNT6'") (class "Default")
      (node (ref "JP10") (pin "6") (pinfunction "2_6") (pintype "passive"))
      (node (ref "R14") (pin "1") (pinfunction "1_1") (pintype "passive"))
    )
    (net (code "35") (name "/CNT7") (class "Default")
      (node (ref "JP10") (pin "7") (pinfunction "1_7") (pintype "passive"))
      (node (ref "Z10") (pin "5") (pinfunction "QC_5") (pintype "output"))
      (node (ref "Z21") (pin "10") (pinfunction "I1_10") (pintype "input"))
      (node (ref "Z25") (pin "12") (pinfunction "I1_12") (pintype "input"))
    )
    (net (code "36") (name "/CNT7'") (class "Default")
      (node (ref "JP10") (pin "8") (pinfunction "2_8") (pintype "passive"))
      (node (ref "R15") (pin "1") (pinfunction "1_1") (pintype "passive"))
    )
    (net (code "37") (name "/CNT8") (class "Default")
      (node (ref "Z10") (pin "13") (pinfunction "A_13") (pintype "input"))
      (node (ref "Z10") (pin "6") (pinfunction "QD_6") (pintype "output"))
      (node (ref "Z21") (pin "9") (pinfunction "I0_9") (pintype "input"))
      (node (ref "Z22") (pin "13") (pinfunction "I2_13") (pintype "input"))
      (node (ref "Z25") (pin "2") (pinfunction "I0_2") (pintype "input"))
    )
    (net (code "38") (name "/CNT9") (class "Default")
      (node (ref "JP18") (pin "2") (pinfunction "2_2") (pintype "passive"))
      (node (ref "R21") (pin "1") (pinfunction "1_1") (pintype "passive"))
      (node (ref "Z10") (pin "11") (pinfunction "QA_11") (pintype "output"))
    )
    (net (code "39") (name "/CNT10") (class "Default")
      (node (ref "JP18") (pin "1") (pinfunction "1_1") (pintype "passive"))
      (node (ref "R22") (pin "1") (pinfunction "1_1") (pintype "passive"))
      (node (ref "Z10") (pin "10") (pinfunction "QB_10") (pintype "output"))
    )
    (net (code "40") (name "/CNT11") (class "Default")
      (node (ref "JP17") (pin "2") (pinfunction "2_2") (pintype "passive"))
      (node (ref "Z10") (pin "9") (pinfunction "QC_9") (pintype "output"))
      (node (ref "Z11") (pin "1") (pinfunction "A_1") (pintype "input"))
    )
    (net (code "41") (name "/CNT12") (class "Default")
      (node (ref "JP15") (pin "1") (pinfunction "1_1") (pintype "passive"))
      (node (ref "Z11") (pin "3") (pinfunction "QA_3") (pintype "output"))
      (node (ref "Z21") (pin "3") (pinfunction "I0_3") (pintype "input"))
    )
    (net (code "42") (name "/CNT12'") (class "Default")
      (node (ref "JP15") (pin "2") (pinfunction "2_2") (pintype "passive"))
      (node (ref "R16") (pin "1") (pinfunction "1_1") (pintype "passive"))
    )
    (net (code "43") (name "/CNT13") (class "Default")
      (node (ref "JP15") (pin "3") (pinfunction "1_3") (pintype "passive"))
      (node (ref "Z11") (pin "4") (pinfunction "QB_4") (pintype "output"))
      (node (ref "Z21") (pin "4") (pinfunction "I1_4") (pintype "input"))
    )
    (net (code "44") (name "/CNT13'") (class "Default")
      (node (ref "JP15") (pin "4") (pinfunction "2_4") (pintype "passive"))
      (node (ref "R17") (pin "1") (pinfunction "1_1") (pintype "passive"))
    )
    (net (code "45") (name "/CNT14") (class "Default")
      (node (ref "JP15") (pin "5") (pinfunction "1_5") (pintype "passive"))
      (node (ref "Z11") (pin "5") (pinfunction "QC_5") (pintype "output"))
      (node (ref "Z21") (pin "5") (pinfunction "I2_5") (pintype "input"))
    )
    (net (code "46") (name "/CNT14'") (class "Default")
      (node (ref "JP15") (pin "6") (pinfunction "2_6") (pintype "passive"))
      (node (ref "R18") (pin "1") (pinfunction "1_1") (pintype "passive"))
    )
    (net (code "47") (name "/CNT15") (class "Default")
      (node (ref "JP15") (pin "7") (pinfunction "1_7") (pintype "passive"))
      (node (ref "Z11") (pin "13") (pinfunction "A_13") (pintype "input"))
      (node (ref "Z11") (pin "6") (pinfunction "QD_6") (pintype "output"))
      (node (ref "Z19") (pin "1") (pinfunction "I0_1") (pintype "input"))
      (node (ref "Z21") (pin "1") (pinfunction "I0_1") (pintype "input"))
    )
    (net (code "48") (name "/CNT15'") (class "Default")
      (node (ref "JP15") (pin "8") (pinfunction "2_8") (pintype "passive"))
      (node (ref "R19") (pin "1") (pinfunction "1_1") (pintype "passive"))
    )
    (net (code "49") (name "/CNT16") (class "Default")
      (node (ref "JP15") (pin "9") (pinfunction "1_9") (pintype "passive"))
      (node (ref "Z11") (pin "11") (pinfunction "QA_11") (pintype "output"))
      (node (ref "Z19") (pin "2") (pinfunction "I1_2") (pintype "input"))
      (node (ref "Z21") (pin "2") (pinfunction "I1_2") (pintype "input"))
    )
    (net (code "50") (name "/CNT16'") (class "Default")
      (node (ref "JP15") (pin "10") (pinfunction "2_10") (pintype "passive"))
      (node (ref "R20") (pin "1") (pinfunction "1_1") (pintype "passive"))
    )
    (net (code "51") (name "/CNT17") (class "Default")
      (node (ref "Z11") (pin "10") (pinfunction "QB_10") (pintype "output"))
      (node (ref "Z20") (pin "2") (pinfunction "I1_2") (pintype "input"))
      (node (ref "Z25") (pin "3") (pinfunction "I1_3") (pintype "input"))
    )
    (net (code "52") (name "/D0") (class "Default")
      (node (ref "20B") (pin "1") (pinfunction "P_1") (pintype "passive"))
      (node (ref "JP2") (pin "14") (pinfunction "14_14") (pintype "passive"))
      (node (ref "R100") (pin "1") (pinfunction "1_1") (pintype "passive"))
      (node (ref "R200") (pin "1") (pinfunction "1_1") (pintype "passive"))
      (node (ref "Z0") (pin "14") (pinfunction "D0_14") (pintype "bidirectional"))
      (node (ref "Z1-2") (pin "11") (pinfunction "I/O0_11") (pintype "tri_state"))
      (node (ref "Z14") (pin "3") (pinfunction "1Y1_3") (pintype "tri_state"))
      (node (ref "Z3-4") (pin "11") (pinfunction "DQ0_11") (pintype "bidirectional"))
    )
    (net (code "53") (name "/D1") (class "Default")
      (node (ref "20A") (pin "1") (pinfunction "P_1") (pintype "passive"))
      (node (ref "JP2") (pin "15") (pinfunction "15_15") (pintype "passive"))
      (node (ref "R101") (pin "1") (pinfunction "1_1") (pintype "passive"))
      (node (ref "R201") (pin "1") (pinfunction "1_1") (pintype "passive"))
      (node (ref "Z0") (pin "15") (pinfunction "D1_15") (pintype "bidirectional"))
      (node (ref "Z1-2") (pin "12") (pinfunction "I/O1_12") (pintype "tri_state"))
      (node (ref "Z14") (pin "5") (pinfunction "1Y2_5") (pintype "tri_state"))
      (node (ref "Z3-4") (pin "12") (pinfunction "DQ1_12") (pintype "bidirectional"))
    )
    (net (code "54") (name "/D2") (class "Default")
      (node (ref "21B") (pin "1") (pinfunction "P_1") (pintype "passive"))
      (node (ref "JP2") (pin "12") (pinfunction "12_12") (pintype "passive"))
      (node (ref "R102") (pin "1") (pinfunction "1_1") (pintype "passive"))
      (node (ref "R202") (pin "1") (pinfunction "1_1") (pintype "passive"))
      (node (ref "Z0") (pin "12") (pinfunction "D2_12") (pintype "bidirectional"))
      (node (ref "Z1-2") (pin "13") (pinfunction "I/O2_13") (pintype "tri_state"))
      (node (ref "Z14") (pin "7") (pinfunction "1Y3_7") (pintype "tri_state"))
      (node (ref "Z3-4") (pin "13") (pinfunction "DQ2_13") (pintype "bidirectional"))
    )
    (net (code "55") (name "/D3") (class "Default")
      (node (ref "12A") (pin "1") (pinfunction "P_1") (pintype "passive"))
      (node (ref "JP2") (pin "8") (pinfunction "8_8") (pintype "passive"))
      (node (ref "R103") (pin "1") (pinfunction "1_1") (pintype "passive"))
      (node (ref "R203") (pin "1") (pinfunction "1_1") (pintype "passive"))
      (node (ref "Z0") (pin "8") (pinfunction "D3_8") (pintype "bidirectional"))
      (node (ref "Z1-2") (pin "15") (pinfunction "I/O3_15") (pintype "tri_state"))
      (node (ref "Z14") (pin "9") (pinfunction "1Y4_9") (pintype "tri_state"))
      (node (ref "Z27") (pin "2") (pinfunction "D_2") (pintype "input"))
      (node (ref "Z3-4") (pin "15") (pinfunction "DQ3_15") (pintype "bidirectional"))
    )
    (net (code "56") (name "/D4") (class "Default")
      (node (ref "11A") (pin "1") (pinfunction "P_1") (pintype "passive"))
      (node (ref "JP2") (pin "7") (pinfunction "7_7") (pintype "passive"))
      (node (ref "R104") (pin "1") (pinfunction "1_1") (pintype "passive"))
      (node (ref "R204") (pin "1") (pinfunction "1_1") (pintype "passive"))
      (node (ref "Z0") (pin "7") (pinfunction "D4_7") (pintype "bidirectional"))
      (node (ref "Z1-2") (pin "16") (pinfunction "I/O4_16") (pintype "tri_state"))
      (node (ref "Z14") (pin "11") (pinfunction "2Y1_11") (pintype "tri_state"))
      (node (ref "Z3-4") (pin "16") (pinfunction "DQ4_16") (pintype "bidirectional"))
    )
    (net (code "57") (name "/D5") (class "Default")
      (node (ref "13A") (pin "1") (pinfunction "P_1") (pintype "passive"))
      (node (ref "JP2") (pin "9") (pinfunction "9_9") (pintype "passive"))
      (node (ref "R105") (pin "1") (pinfunction "1_1") (pintype "passive"))
      (node (ref "R205") (pin "1") (pinfunction "1_1") (pintype "passive"))
      (node (ref "Z0") (pin "9") (pinfunction "D5_9") (pintype "bidirectional"))
      (node (ref "Z1-2") (pin "17") (pinfunction "I/O5_17") (pintype "tri_state"))
      (node (ref "Z14") (pin "13") (pinfunction "2Y2_13") (pintype "tri_state"))
      (node (ref "Z3-4") (pin "17") (pinfunction "DQ5_17") (pintype "bidirectional"))
    )
    (net (code "58") (name "/D6") (class "Default")
      (node (ref "21A") (pin "1") (pinfunction "P_1") (pintype "passive"))
      (node (ref "JP2") (pin "10") (pinfunction "10_10") (pintype "passive"))
      (node (ref "R106") (pin "1") (pinfunction "1_1") (pintype "passive"))
      (node (ref "R206") (pin "1") (pinfunction "1_1") (pintype "passive"))
      (node (ref "Z0") (pin "10") (pinfunction "D6_10") (pintype "bidirectional"))
      (node (ref "Z1-2") (pin "18") (pinfunction "I/O6_18") (pintype "tri_state"))
      (node (ref "Z3-4") (pin "18") (pinfunction "DQ6_18") (pintype "bidirectional"))
    )
    (net (code "59") (name "/D7") (class "Default")
      (node (ref "22B") (pin "1") (pinfunction "P_1") (pintype "passive"))
      (node (ref "JP2") (pin "13") (pinfunction "13_13") (pintype "passive"))
      (node (ref "R107") (pin "1") (pinfunction "1_1") (pintype "passive"))
      (node (ref "R207") (pin "1") (pinfunction "1_1") (pintype "passive"))
      (node (ref "Z0") (pin "13") (pinfunction "D7_13") (pintype "bidirectional"))
      (node (ref "Z1-2") (pin "19") (pinfunction "I/O7_19") (pintype "tri_state"))
      (node (ref "Z3-4") (pin "19") (pinfunction "DQ7_19") (pintype "bidirectional"))
    )
    (net (code "60") (name "/EAR") (class "Default")
      (node (ref "Z14") (pin "14") (pinfunction "2A2_14") (pintype "input"))
      (node (ref "Z18") (pin "13") (pinfunction "2Y2_13") (pintype "tri_state"))
    )
    (net (code "61") (name "/FIELD") (class "Default")
      (node (ref "Z19") (pin "12") (pinfunction "I0_12") (pintype "input"))
      (node (ref "Z21") (pin "12") (pinfunction "O_12") (pintype "output"))
      (node (ref "Z25") (pin "6") (pinfunction "I1_6") (pintype "input"))
    )
    (net (code "62") (name "/INV_BIT") (class "Default")
      (node (ref "JP18") (pin "3") (pinfunction "3_3") (pintype "passive"))
      (node (ref "JP4") (pin "1") (pinfunction "1_1") (pintype "passive"))
      (node (ref "Z27") (pin "9") (pinfunction "Q_9") (pintype "output"))
    )
    (net (code "63") (name "/KB") (class "Default")
      (node (ref "JP16") (pin "12") (pinfunction "12_12") (pintype "passive"))
      (node (ref "JP16") (pin "5") (pinfunction "5_5") (pintype "passive"))
      (node (ref "K37") (pin "3") (pinfunction "P_3") (pintype "passive"))
      (node (ref "K37") (pin "4") (pinfunction "P1_4") (pintype "passive"))
      (node (ref "SJ4") (pin "1") (pinfunction "1_1") (pintype "passive"))
      (node (ref "SJ7") (pin "2") (pinfunction "2_2") (pintype "passive"))
      (node (ref "U$37") (pin "P$2") (pinfunction "2_P$2") (pintype "passive"))
      (node (ref "Z40") (pin "4") (pinfunction "I3_4") (pintype "input"))
    )
    (net (code "64") (name "/KC") (class "Default")
      (node (ref "JP16") (pin "7") (pinfunction "7_7") (pintype "passive"))
      (node (ref "K35") (pin "3") (pinfunction "P_3") (pintype "passive"))
      (node (ref "K35") (pin "4") (pinfunction "P1_4") (pintype "passive"))
      (node (ref "SJ5") (pin "1") (pinfunction "1_1") (pintype "passive"))
      (node (ref "U$35") (pin "P$2") (pinfunction "2_P$2") (pintype "passive"))
      (node (ref "Z40") (pin "5") (pinfunction "I4_5") (pintype "input"))
    )
    (net (code "65") (name "/KEYB1") (class "Default")
      (node (ref "K1") (pin "3") (pinfunction "P_3") (pintype "passive"))
      (node (ref "K1") (pin "4") (pinfunction "P1_4") (pintype "passive"))
      (node (ref "K10") (pin "3") (pinfunction "P_3") (pintype "passive"))
      (node (ref "K10") (pin "4") (pinfunction "P1_4") (pintype "passive"))
      (node (ref "K11") (pin "3") (pinfunction "P_3") (pintype "passive"))
      (node (ref "K11") (pin "4") (pinfunction "P1_4") (pintype "passive"))
      (node (ref "K20") (pin "3") (pinfunction "P_3") (pintype "passive"))
      (node (ref "K20") (pin "4") (pinfunction "P1_4") (pintype "passive"))
      (node (ref "K21") (pin "3") (pinfunction "P_3") (pintype "passive"))
      (node (ref "K21") (pin "4") (pinfunction "P1_4") (pintype "passive"))
      (node (ref "K30") (pin "3") (pinfunction "P_3") (pintype "passive"))
      (node (ref "K30") (pin "4") (pinfunction "P1_4") (pintype "passive"))
      (node (ref "K31") (pin "3") (pinfunction "P_3") (pintype "passive"))
      (node (ref "K31") (pin "4") (pinfunction "P1_4") (pintype "passive"))
      (node (ref "K40") (pin "3") (pinfunction "P_3") (pintype "passive"))
      (node (ref "K40") (pin "4") (pinfunction "P1_4") (pintype "passive"))
      (node (ref "K41") (pin "3") (pinfunction "P_3") (pintype "passive"))
      (node (ref "K41") (pin "4") (pinfunction "P1_4") (pintype "passive"))
      (node (ref "R36") (pin "1") (pinfunction "1_1") (pintype "passive"))
      (node (ref "RN1") (pin "6") (pinfunction "6_6") (pintype "passive"))
      (node (ref "U$1") (pin "P$2") (pinfunction "2_P$2") (pintype "passive"))
      (node (ref "U$10") (pin "P$2") (pinfunction "2_P$2") (pintype "passive"))
      (node (ref "U$11") (pin "P$2") (pinfunction "2_P$2") (pintype "passive"))
      (node (ref "U$20") (pin "P$2") (pinfunction "2_P$2") (pintype "passive"))
      (node (ref "U$21") (pin "P$2") (pinfunction "2_P$2") (pintype "passive"))
      (node (ref "U$30") (pin "P$2") (pinfunction "2_P$2") (pintype "passive"))
      (node (ref "U$31") (pin "P$2") (pinfunction "2_P$2") (pintype "passive"))
      (node (ref "U$40") (pin "P$2") (pinfunction "2_P$2") (pintype "passive"))
      (node (ref "U$41") (pin "P$2") (pinfunction "2_P$2") (pintype "passive"))
      (node (ref "U$42") (pin "P$2") (pinfunction "2_P$2") (pintype "passive"))
      (node (ref "Z14") (pin "2") (pinfunction "1A1_2") (pintype "input"))
    )
    (net (code "66") (name "/KEYB2") (class "Default")
      (node (ref "D14") (pin "A") (pinfunction "A_A") (pintype "passive"))
      (node (ref "JP16") (pin "2") (pinfunction "2_2") (pintype "passive"))
      (node (ref "K12") (pin "3") (pinfunction "P_3") (pintype "passive"))
      (node (ref "K12") (pin "4") (pinfunction "P1_4") (pintype "passive"))
      (node (ref "K19") (pin "3") (pinfunction "P_3") (pintype "passive"))
      (node (ref "K19") (pin "4") (pinfunction "P1_4") (pintype "passive"))
      (node (ref "K2") (pin "3") (pinfunction "P_3") (pintype "passive"))
      (node (ref "K2") (pin "4") (pinfunction "P1_4") (pintype "passive"))
      (node (ref "K22") (pin "3") (pinfunction "P_3") (pintype "passive"))
      (node (ref "K22") (pin "4") (pinfunction "P1_4") (pintype "passive"))
      (node (ref "K29") (pin "3") (pinfunction "P_3") (pintype "passive"))
      (node (ref "K29") (pin "4") (pinfunction "P1_4") (pintype "passive"))
      (node (ref "K32") (pin "3") (pinfunction "P_3") (pintype "passive"))
      (node (ref "K32") (pin "4") (pinfunction "P1_4") (pintype "passive"))
      (node (ref "K9") (pin "3") (pinfunction "P_3") (pintype "passive"))
      (node (ref "K9") (pin "4") (pinfunction "P1_4") (pintype "passive"))
      (node (ref "R37") (pin "1") (pinfunction "1_1") (pintype "passive"))
      (node (ref "RN1") (pin "5") (pinfunction "5_5") (pintype "passive"))
      (node (ref "SJ2") (pin "2") (pinfunction "2_2") (pintype "passive"))
      (node (ref "U$12") (pin "P$2") (pinfunction "2_P$2") (pintype "passive"))
      (node (ref "U$19") (pin "P$2") (pinfunction "2_P$2") (pintype "passive"))
      (node (ref "U$2") (pin "P$2") (pinfunction "2_P$2") (pintype "passive"))
      (node (ref "U$22") (pin "P$2") (pinfunction "2_P$2") (pintype "passive"))
      (node (ref "U$29") (pin "P$2") (pinfunction "2_P$2") (pintype "passive"))
      (node (ref "U$32") (pin "P$2") (pinfunction "2_P$2") (pintype "passive"))
      (node (ref "U$9") (pin "P$2") (pinfunction "2_P$2") (pintype "passive"))
      (node (ref "Z14") (pin "4") (pinfunction "1A2_4") (pintype "input"))
    )
    (net (code "67") (name "/KEYB3") (class "Default")
      (node (ref "D15") (pin "A") (pinfunction "A_A") (pintype "passive"))
      (node (ref "JP16") (pin "4") (pinfunction "4_4") (pintype "passive"))
      (node (ref "K13") (pin "3") (pinfunction "P_3") (pintype "passive"))
      (node (ref "K13") (pin "4") (pinfunction "P1_4") (pintype "passive"))
      (node (ref "K18") (pin "3") (pinfunction "P_3") (pintype "passive"))
      (node (ref "K18") (pin "4") (pinfunction "P1_4") (pintype "passive"))
      (node (ref "K23") (pin "3") (pinfunction "P_3") (pintype "passive"))
      (node (ref "K23") (pin "4") (pinfunction "P1_4") (pintype "passive"))
      (node (ref "K28") (pin "3") (pinfunction "P_3") (pintype "passive"))
      (node (ref "K28") (pin "4") (pinfunction "P1_4") (pintype "passive"))
      (node (ref "K3") (pin "3") (pinfunction "P_3") (pintype "passive"))
      (node (ref "K3") (pin "4") (pinfunction "P1_4") (pintype "passive"))
      (node (ref "K8") (pin "3") (pinfunction "P_3") (pintype "passive"))
      (node (ref "K8") (pin "4") (pinfunction "P1_4") (pintype "passive"))
      (node (ref "R38") (pin "1") (pinfunction "1_1") (pintype "passive"))
      (node (ref "RN1") (pin "4") (pinfunction "4_4") (pintype "passive"))
      (node (ref "SJ3") (pin "2") (pinfunction "2_2") (pintype "passive"))
      (node (ref "U$13") (pin "P$2") (pinfunction "2_P$2") (pintype "passive"))
      (node (ref "U$18") (pin "P$2") (pinfunction "2_P$2") (pintype "passive"))
      (node (ref "U$23") (pin "P$2") (pinfunction "2_P$2") (pintype "passive"))
      (node (ref "U$28") (pin "P$2") (pinfunction "2_P$2") (pintype "passive"))
      (node (ref "U$3") (pin "P$2") (pinfunction "2_P$2") (pintype "passive"))
      (node (ref "U$8") (pin "P$2") (pinfunction "2_P$2") (pintype "passive"))
      (node (ref "Z14") (pin "6") (pinfunction "1A3_6") (pintype "input"))
    )
    (net (code "68") (name "/KEYB4") (class "Default")
      (node (ref "D16") (pin "A") (pinfunction "A_A") (pintype "passive"))
      (node (ref "JP16") (pin "6") (pinfunction "6_6") (pintype "passive"))
      (node (ref "K14") (pin "3") (pinfunction "P_3") (pintype "passive"))
      (node (ref "K14") (pin "4") (pinfunction "P1_4") (pintype "passive"))
      (node (ref "K17") (pin "3") (pinfunction "P_3") (pintype "passive"))
      (node (ref "K17") (pin "4") (pinfunction "P1_4") (pintype "passive"))
      (node (ref "K24") (pin "3") (pinfunction "P_3") (pintype "passive"))
      (node (ref "K24") (pin "4") (pinfunction "P1_4") (pintype "passive"))
      (node (ref "K27") (pin "3") (pinfunction "P_3") (pintype "passive"))
      (node (ref "K27") (pin "4") (pinfunction "P1_4") (pintype "passive"))
      (node (ref "K4") (pin "3") (pinfunction "P_3") (pintype "passive"))
      (node (ref "K4") (pin "4") (pinfunction "P1_4") (pintype "passive"))
      (node (ref "K7") (pin "3") (pinfunction "P_3") (pintype "passive"))
      (node (ref "K7") (pin "4") (pinfunction "P1_4") (pintype "passive"))
      (node (ref "R40") (pin "1") (pinfunction "1_1") (pintype "passive"))
      (node (ref "RN1") (pin "3") (pinfunction "3_3") (pintype "passive"))
      (node (ref "SJ4") (pin "2") (pinfunction "2_2") (pintype "passive"))
      (node (ref "U$14") (pin "P$2") (pinfunction "2_P$2") (pintype "passive"))
      (node (ref "U$17") (pin "P$2") (pinfunction "2_P$2") (pintype "passive"))
      (node (ref "U$24") (pin "P$2") (pinfunction "2_P$2") (pintype "passive"))
      (node (ref "U$27") (pin "P$2") (pinfunction "2_P$2") (pintype "passive"))
      (node (ref "U$4") (pin "P$2") (pinfunction "2_P$2") (pintype "passive"))
      (node (ref "U$7") (pin "P$2") (pinfunction "2_P$2") (pintype "passive"))
      (node (ref "Z14") (pin "10") (pinfunction "1A4_10") (pintype "input"))
    )
    (net (code "69") (name "/KEYB5") (class "Default")
      (node (ref "D17") (pin "A") (pinfunction "A_A") (pintype "passive"))
      (node (ref "JP16") (pin "8") (pinfunction "8_8") (pintype "passive"))
      (node (ref "K15") (pin "3") (pinfunction "P_3") (pintype "passive"))
      (node (ref "K15") (pin "4") (pinfunction "P1_4") (pintype "passive"))
      (node (ref "K16") (pin "3") (pinfunction "P_3") (pintype "passive"))
      (node (ref "K16") (pin "4") (pinfunction "P1_4") (pintype "passive"))
      (node (ref "K25") (pin "3") (pinfunction "P_3") (pintype "passive"))
      (node (ref "K25") (pin "4") (pinfunction "P1_4") (pintype "passive"))
      (node (ref "K26") (pin "3") (pinfunction "P_3") (pintype "passive"))
      (node (ref "K26") (pin "4") (pinfunction "P1_4") (pintype "passive"))
      (node (ref "K36") (pin "3") (pinfunction "P_3") (pintype "passive"))
      (node (ref "K36") (pin "4") (pinfunction "P1_4") (pintype "passive"))
      (node (ref "K5") (pin "3") (pinfunction "P_3") (pintype "passive"))
      (node (ref "K5") (pin "4") (pinfunction "P1_4") (pintype "passive"))
      (node (ref "K6") (pin "3") (pinfunction "P_3") (pintype "passive"))
      (node (ref "K6") (pin "4") (pinfunction "P1_4") (pintype "passive"))
      (node (ref "R41") (pin "1") (pinfunction "1_1") (pintype "passive"))
      (node (ref "RN1") (pin "2") (pinfunction "2_2") (pintype "passive"))
      (node (ref "SJ5") (pin "2") (pinfunction "2_2") (pintype "passive"))
      (node (ref "U$15") (pin "P$2") (pinfunction "2_P$2") (pintype "passive"))
      (node (ref "U$16") (pin "P$2") (pinfunction "2_P$2") (pintype "passive"))
      (node (ref "U$25") (pin "P$2") (pinfunction "2_P$2") (pintype "passive"))
      (node (ref "U$26") (pin "P$2") (pinfunction "2_P$2") (pintype "passive"))
      (node (ref "U$36") (pin "P$2") (pinfunction "2_P$2") (pintype "passive"))
      (node (ref "U$5") (pin "P$2") (pinfunction "2_P$2") (pintype "passive"))
      (node (ref "U$6") (pin "P$2") (pinfunction "2_P$2") (pintype "passive"))
      (node (ref "Z14") (pin "12") (pinfunction "2A1_12") (pintype "input"))
    )
    (net (code "70") (name "/KM") (class "Default")
      (node (ref "JP16") (pin "1") (pinfunction "1_1") (pintype "passive"))
      (node (ref "K39") (pin "3") (pinfunction "P_3") (pintype "passive"))
      (node (ref "K39") (pin "4") (pinfunction "P1_4") (pintype "passive"))
      (node (ref "SJ2") (pin "1") (pinfunction "1_1") (pintype "passive"))
      (node (ref "U$39") (pin "P$2") (pinfunction "2_P$2") (pintype "passive"))
      (node (ref "Z40") (pin "2") (pinfunction "I1_2") (pintype "input"))
    )
    (net (code "71") (name "/KN") (class "Default")
      (node (ref "JP16") (pin "3") (pinfunction "3_3") (pintype "passive"))
      (node (ref "JP16") (pin "9") (pinfunction "9_9") (pintype "passive"))
      (node (ref "K38") (pin "3") (pinfunction "P_3") (pintype "passive"))
      (node (ref "K38") (pin "4") (pinfunction "P1_4") (pintype "passive"))
      (node (ref "SJ3") (pin "1") (pinfunction "1_1") (pintype "passive"))
      (node (ref "SJ6") (pin "1") (pinfunction "1_1") (pintype "passive"))
      (node (ref "U$38") (pin "P$2") (pinfunction "2_P$2") (pintype "passive"))
      (node (ref "Z40") (pin "3") (pinfunction "I2_3") (pintype "input"))
    )
    (net (code "72") (name "/KX") (class "Default")
      (node (ref "JP16") (pin "11") (pinfunction "11_11") (pintype "passive"))
      (node (ref "K34") (pin "3") (pinfunction "P_3") (pintype "passive"))
      (node (ref "K34") (pin "4") (pinfunction "P1_4") (pintype "passive"))
      (node (ref "SJ7") (pin "1") (pinfunction "1_1") (pintype "passive"))
      (node (ref "U$34") (pin "P$2") (pinfunction "2_P$2") (pintype "passive"))
      (node (ref "Z40") (pin "6") (pinfunction "I5_6") (pintype "input"))
    )
    (net (code "73") (name "/KZ") (class "Default")
      (node (ref "JP16") (pin "10") (pinfunction "10_10") (pintype "passive"))
      (node (ref "K33") (pin "3") (pinfunction "P_3") (pintype "passive"))
      (node (ref "K33") (pin "4") (pinfunction "P1_4") (pintype "passive"))
      (node (ref "SJ6") (pin "2") (pinfunction "2_2") (pintype "passive"))
      (node (ref "U$33") (pin "P$2") (pinfunction "2_P$2") (pintype "passive"))
      (node (ref "Z40") (pin "7") (pinfunction "I6_7") (pintype "input"))
    )
    (net (code "74") (name "/LINE") (class "Default")
      (node (ref "Z22") (pin "12") (pinfunction "O_12") (pintype "output"))
      (node (ref "Z25") (pin "5") (pinfunction "I0_5") (pintype "input"))
    )
    (net (code "75") (name "/N$56") (class "Default")
      (node (ref "JP6") (pin "2") (pinfunction "2_2") (pintype "passive"))
      (node (ref "R42") (pin "1") (pinfunction "1_1") (pintype "passive"))
    )
    (net (code "76") (name "/NC1") (class "Default")
      (node (ref "24A") (pin "1") (pinfunction "P_1") (pintype "passive"))
    )
    (net (code "77") (name "/NC2") (class "Default")
      (node (ref "25A") (pin "1") (pinfunction "P_1") (pintype "passive"))
    )
    (net (code "78") (name "/NC3") (class "Default")
      (node (ref "24B") (pin "1") (pinfunction "P_1") (pintype "passive"))
    )
    (net (code "79") (name "/NC4") (class "Default")
      (node (ref "25B") (pin "1") (pinfunction "P_1") (pintype "passive"))
    )
    (net (code "80") (name "/PHI") (class "Default")
      (node (ref "5A") (pin "1") (pinfunction "P_1") (pintype "passive"))
      (node (ref "JP2") (pin "6") (pinfunction "6_6") (pintype "passive"))
      (node (ref "Z0") (pin "6") (pinfunction "CLK_6") (pintype "input"))
      (node (ref "Z30") (pin "6") (pinfunction "O_6") (pintype "output"))
    )
    (net (code "81") (name "/RESET") (class "Default")
      (node (ref "12B") (pin "1") (pinfunction "P_1") (pintype "passive"))
      (node (ref "C7") (pin "+") (pinfunction "+_+") (pintype "passive"))
      (node (ref "JP9") (pin "15") (pinfunction "15_15") (pintype "passive"))
      (node (ref "R25") (pin "1") (pinfunction "1_1") (pintype "passive"))
      (node (ref "S2") (pin "2") (pinfunction "S_2") (pintype "passive"))
      (node (ref "Z0") (pin "26") (pinfunction "RESET_26") (pintype "input"))
    )
    (net (code "82") (name "/ROW1") (class "Default")
      (node (ref "D10") (pin "A") (pinfunction "A_A") (pintype "passive"))
      (node (ref "JP1") (pin "1") (pinfunction "1_1") (pintype "passive"))
      (node (ref "JP16") (pin "13") (pinfunction "13_13") (pintype "passive"))
      (node (ref "K31") (pin "1") (pinfunction "S_1") (pintype "passive"))
      (node (ref "K31") (pin "2") (pinfunction "S1_2") (pintype "passive"))
      (node (ref "K33") (pin "1") (pinfunction "S_1") (pintype "passive"))
      (node (ref "K33") (pin "2") (pinfunction "S1_2") (pintype "passive"))
      (node (ref "K34") (pin "1") (pinfunction "S_1") (pintype "passive"))
      (node (ref "K34") (pin "2") (pinfunction "S1_2") (pintype "passive"))
      (node (ref "K35") (pin "1") (pinfunction "S_1") (pintype "passive"))
      (node (ref "K35") (pin "2") (pinfunction "S1_2") (pintype "passive"))
      (node (ref "R30") (pin "2") (pinfunction "2_2") (pintype "passive"))
      (node (ref "SJ8") (pin "1") (pinfunction "1_1") (pintype "passive"))
      (node (ref "U$31") (pin "P$1") (pinfunction "1_P$1") (pintype "passive"))
      (node (ref "U$33") (pin "P$1") (pinfunction "1_P$1") (pintype "passive"))
      (node (ref "U$34") (pin "P$1") (pinfunction "1_P$1") (pintype "passive"))
      (node (ref "U$35") (pin "P$1") (pinfunction "1_P$1") (pintype "passive"))
      (node (ref "Z40") (pin "8") (pinfunction "I7_8") (pintype "input"))
    )
    (net (code "83") (name "/ROW2") (class "Default")
      (node (ref "D9") (pin "A") (pinfunction "A_A") (pintype "passive"))
      (node (ref "JP1") (pin "2") (pinfunction "2_2") (pintype "passive"))
      (node (ref "K21") (pin "1") (pinfunction "S_1") (pintype "passive"))
      (node (ref "K21") (pin "2") (pinfunction "S1_2") (pintype "passive"))
      (node (ref "K22") (pin "1") (pinfunction "S_1") (pintype "passive"))
      (node (ref "K22") (pin "2") (pinfunction "S1_2") (pintype "passive"))
      (node (ref "K23") (pin "1") (pinfunction "S_1") (pintype "passive"))
      (node (ref "K23") (pin "2") (pinfunction "S1_2") (pintype "passive"))
      (node (ref "K24") (pin "1") (pinfunction "S_1") (pintype "passive"))
      (node (ref "K24") (pin "2") (pinfunction "S1_2") (pintype "passive"))
      (node (ref "K25") (pin "1") (pinfunction "S_1") (pintype "passive"))
      (node (ref "K25") (pin "2") (pinfunction "S1_2") (pintype "passive"))
      (node (ref "U$21") (pin "P$1") (pinfunction "1_P$1") (pintype "passive"))
      (node (ref "U$22") (pin "P$1") (pinfunction "1_P$1") (pintype "passive"))
      (node (ref "U$23") (pin "P$1") (pinfunction "1_P$1") (pintype "passive"))
      (node (ref "U$24") (pin "P$1") (pinfunction "1_P$1") (pintype "passive"))
      (node (ref "U$25") (pin "P$1") (pinfunction "1_P$1") (pintype "passive"))
    )
    (net (code "84") (name "/ROW3") (class "Default")
      (node (ref "D8") (pin "A") (pinfunction "A_A") (pintype "passive"))
      (node (ref "JP1") (pin "3") (pinfunction "3_3") (pintype "passive"))
      (node (ref "K11") (pin "1") (pinfunction "S_1") (pintype "passive"))
      (node (ref "K11") (pin "2") (pinfunction "S1_2") (pintype "passive"))
      (node (ref "K12") (pin "1") (pinfunction "S_1") (pintype "passive"))
      (node (ref "K12") (pin "2") (pinfunction "S1_2") (pintype "passive"))
      (node (ref "K13") (pin "1") (pinfunction "S_1") (pintype "passive"))
      (node (ref "K13") (pin "2") (pinfunction "S1_2") (pintype "passive"))
      (node (ref "K14") (pin "1") (pinfunction "S_1") (pintype "passive"))
      (node (ref "K14") (pin "2") (pinfunction "S1_2") (pintype "passive"))
      (node (ref "K15") (pin "1") (pinfunction "S_1") (pintype "passive"))
      (node (ref "K15") (pin "2") (pinfunction "S1_2") (pintype "passive"))
      (node (ref "U$11") (pin "P$1") (pinfunction "1_P$1") (pintype "passive"))
      (node (ref "U$12") (pin "P$1") (pinfunction "1_P$1") (pintype "passive"))
      (node (ref "U$13") (pin "P$1") (pinfunction "1_P$1") (pintype "passive"))
      (node (ref "U$14") (pin "P$1") (pinfunction "1_P$1") (pintype "passive"))
      (node (ref "U$15") (pin "P$1") (pinfunction "1_P$1") (pintype "passive"))
    )
    (net (code "85") (name "/ROW4") (class "Default")
      (node (ref "D7") (pin "A") (pinfunction "A_A") (pintype "passive"))
      (node (ref "JP1") (pin "4") (pinfunction "4_4") (pintype "passive"))
      (node (ref "K1") (pin "1") (pinfunction "S_1") (pintype "passive"))
      (node (ref "K1") (pin "2") (pinfunction "S1_2") (pintype "passive"))
      (node (ref "K2") (pin "1") (pinfunction "S_1") (pintype "passive"))
      (node (ref "K2") (pin "2") (pinfunction "S1_2") (pintype "passive"))
      (node (ref "K3") (pin "1") (pinfunction "S_1") (pintype "passive"))
      (node (ref "K3") (pin "2") (pinfunction "S1_2") (pintype "passive"))
      (node (ref "K4") (pin "1") (pinfunction "S_1") (pintype "passive"))
      (node (ref "K4") (pin "2") (pinfunction "S1_2") (pintype "passive"))
      (node (ref "K5") (pin "1") (pinfunction "S_1") (pintype "passive"))
      (node (ref "K5") (pin "2") (pinfunction "S1_2") (pintype "passive"))
      (node (ref "U$1") (pin "P$1") (pinfunction "1_P$1") (pintype "passive"))
      (node (ref "U$2") (pin "P$1") (pinfunction "1_P$1") (pintype "passive"))
      (node (ref "U$3") (pin "P$1") (pinfunction "1_P$1") (pintype "passive"))
      (node (ref "U$4") (pin "P$1") (pinfunction "1_P$1") (pintype "passive"))
      (node (ref "U$5") (pin "P$1") (pinfunction "1_P$1") (pintype "passive"))
    )
    (net (code "86") (name "/ROW5") (class "Default")
      (node (ref "D6") (pin "A") (pinfunction "A_A") (pintype "passive"))
      (node (ref "JP1") (pin "5") (pinfunction "5_5") (pintype "passive"))
      (node (ref "K10") (pin "1") (pinfunction "S_1") (pintype "passive"))
      (node (ref "K10") (pin "2") (pinfunction "S1_2") (pintype "passive"))
      (node (ref "K6") (pin "1") (pinfunction "S_1") (pintype "passive"))
      (node (ref "K6") (pin "2") (pinfunction "S1_2") (pintype "passive"))
      (node (ref "K7") (pin "1") (pinfunction "S_1") (pintype "passive"))
      (node (ref "K7") (pin "2") (pinfunction "S1_2") (pintype "passive"))
      (node (ref "K8") (pin "1") (pinfunction "S_1") (pintype "passive"))
      (node (ref "K8") (pin "2") (pinfunction "S1_2") (pintype "passive"))
      (node (ref "K9") (pin "1") (pinfunction "S_1") (pintype "passive"))
      (node (ref "K9") (pin "2") (pinfunction "S1_2") (pintype "passive"))
      (node (ref "U$10") (pin "P$1") (pinfunction "1_P$1") (pintype "passive"))
      (node (ref "U$6") (pin "P$1") (pinfunction "1_P$1") (pintype "passive"))
      (node (ref "U$7") (pin "P$1") (pinfunction "1_P$1") (pintype "passive"))
      (node (ref "U$8") (pin "P$1") (pinfunction "1_P$1") (pintype "passive"))
      (node (ref "U$9") (pin "P$1") (pinfunction "1_P$1") (pintype "passive"))
    )
    (net (code "87") (name "/ROW6") (class "Default")
      (node (ref "D5") (pin "A") (pinfunction "A_A") (pintype "passive"))
      (node (ref "JP1") (pin "6") (pinfunction "6_6") (pintype "passive"))
      (node (ref "K16") (pin "1") (pinfunction "S_1") (pintype "passive"))
      (node (ref "K16") (pin "2") (pinfunction "S1_2") (pintype "passive"))
      (node (ref "K17") (pin "1") (pinfunction "S_1") (pintype "passive"))
      (node (ref "K17") (pin "2") (pinfunction "S1_2") (pintype "passive"))
      (node (ref "K18") (pin "1") (pinfunction "S_1") (pintype "passive"))
      (node (ref "K18") (pin "2") (pinfunction "S1_2") (pintype "passive"))
      (node (ref "K19") (pin "1") (pinfunction "S_1") (pintype "passive"))
      (node (ref "K19") (pin "2") (pinfunction "S1_2") (pintype "passive"))
      (node (ref "K20") (pin "1") (pinfunction "S_1") (pintype "passive"))
      (node (ref "K20") (pin "2") (pinfunction "S1_2") (pintype "passive"))
      (node (ref "U$16") (pin "P$1") (pinfunction "1_P$1") (pintype "passive"))
      (node (ref "U$17") (pin "P$1") (pinfunction "1_P$1") (pintype "passive"))
      (node (ref "U$18") (pin "P$1") (pinfunction "1_P$1") (pintype "passive"))
      (node (ref "U$19") (pin "P$1") (pinfunction "1_P$1") (pintype "passive"))
      (node (ref "U$20") (pin "P$1") (pinfunction "1_P$1") (pintype "passive"))
    )
    (net (code "88") (name "/ROW7") (class "Default")
      (node (ref "D4") (pin "A") (pinfunction "A_A") (pintype "passive"))
      (node (ref "JP1") (pin "7") (pinfunction "7_7") (pintype "passive"))
      (node (ref "K26") (pin "1") (pinfunction "S_1") (pintype "passive"))
      (node (ref "K26") (pin "2") (pinfunction "S1_2") (pintype "passive"))
      (node (ref "K27") (pin "1") (pinfunction "S_1") (pintype "passive"))
      (node (ref "K27") (pin "2") (pinfunction "S1_2") (pintype "passive"))
      (node (ref "K28") (pin "1") (pinfunction "S_1") (pintype "passive"))
      (node (ref "K28") (pin "2") (pinfunction "S1_2") (pintype "passive"))
      (node (ref "K29") (pin "1") (pinfunction "S_1") (pintype "passive"))
      (node (ref "K29") (pin "2") (pinfunction "S1_2") (pintype "passive"))
      (node (ref "K30") (pin "1") (pinfunction "S_1") (pintype "passive"))
      (node (ref "K30") (pin "2") (pinfunction "S1_2") (pintype "passive"))
      (node (ref "U$26") (pin "P$1") (pinfunction "1_P$1") (pintype "passive"))
      (node (ref "U$27") (pin "P$1") (pinfunction "1_P$1") (pintype "passive"))
      (node (ref "U$28") (pin "P$1") (pinfunction "1_P$1") (pintype "passive"))
      (node (ref "U$29") (pin "P$1") (pinfunction "1_P$1") (pintype "passive"))
      (node (ref "U$30") (pin "P$1") (pinfunction "1_P$1") (pintype "passive"))
    )
    (net (code "89") (name "/ROW8") (class "Default")
      (node (ref "D3") (pin "A") (pinfunction "A_A") (pintype "passive"))
      (node (ref "JP1") (pin "8") (pinfunction "8_8") (pintype "passive"))
      (node (ref "JP16") (pin "15") (pinfunction "15_15") (pintype "passive"))
      (node (ref "K37") (pin "1") (pinfunction "S_1") (pintype "passive"))
      (node (ref "K37") (pin "2") (pinfunction "S1_2") (pintype "passive"))
      (node (ref "K38") (pin "1") (pinfunction "S_1") (pintype "passive"))
      (node (ref "K38") (pin "2") (pinfunction "S1_2") (pintype "passive"))
      (node (ref "K39") (pin "1") (pinfunction "S_1") (pintype "passive"))
      (node (ref "K39") (pin "2") (pinfunction "S1_2") (pintype "passive"))
      (node (ref "K40") (pin "1") (pinfunction "S_1") (pintype "passive"))
      (node (ref "K40") (pin "2") (pinfunction "S1_2") (pintype "passive"))
      (node (ref "K41") (pin "1") (pinfunction "S_1") (pintype "passive"))
      (node (ref "K41") (pin "2") (pinfunction "S1_2") (pintype "passive"))
      (node (ref "R31") (pin "2") (pinfunction "2_2") (pintype "passive"))
      (node (ref "SJ9") (pin "1") (pinfunction "1_1") (pintype "passive"))
      (node (ref "U$37") (pin "P$1") (pinfunction "1_P$1") (pintype "passive"))
      (node (ref "U$38") (pin "P$1") (pinfunction "1_P$1") (pintype "passive"))
      (node (ref "U$39") (pin "P$1") (pinfunction "1_P$1") (pintype "passive"))
      (node (ref "U$40") (pin "P$1") (pinfunction "1_P$1") (pintype "passive"))
      (node (ref "U$41") (pin "P$1") (pinfunction "1_P$1") (pintype "passive"))
      (node (ref "U$42") (pin "P$1") (pinfunction "1_P$1") (pintype "passive"))
      (node (ref "Z40") (pin "9") (pinfunction "I8_9") (pintype "input"))
    )
    (net (code "90") (name "/ROW_SS") (class "Default")
      (node (ref "D13") (pin "A") (pinfunction "A_A") (pintype "passive"))
      (node (ref "JP16") (pin "14") (pinfunction "14_14") (pintype "passive"))
      (node (ref "K32") (pin "1") (pinfunction "S_1") (pintype "passive"))
      (node (ref "K32") (pin "2") (pinfunction "S1_2") (pintype "passive"))
      (node (ref "SJ8") (pin "2") (pinfunction "2_2") (pintype "passive"))
      (node (ref "U$32") (pin "P$1") (pinfunction "1_P$1") (pintype "passive"))
    )
    (net (code "91") (name "/ROW_V") (class "Default")
      (node (ref "D12") (pin "A") (pinfunction "A_A") (pintype "passive"))
      (node (ref "JP16") (pin "16") (pinfunction "16_16") (pintype "passive"))
      (node (ref "K36") (pin "1") (pinfunction "S_1") (pintype "passive"))
      (node (ref "K36") (pin "2") (pinfunction "S1_2") (pintype "passive"))
      (node (ref "SJ9") (pin "2") (pinfunction "2_2") (pintype "passive"))
      (node (ref "U$36") (pin "P$1") (pinfunction "1_P$1") (pintype "passive"))
    )
    (net (code "92") (name "/SYNC") (class "Default")
      (node (ref "D1") (pin "C") (pinfunction "C_C") (pintype "passive"))
      (node (ref "Z1") (pin "13") (pinfunction "CLR_13") (pintype "input"))
      (node (ref "Z25") (pin "4") (pinfunction "O_4") (pintype "output"))
    )
    (net (code "93") (name "/VA0") (class "Default")
      (node (ref "1A1") (pin "1") (pinfunction "P_1") (pintype "passive"))
      (node (ref "R11") (pin "2") (pinfunction "2_2") (pintype "passive"))
      (node (ref "Z15") (pin "3") (pinfunction "1Y1_3") (pintype "tri_state"))
      (node (ref "Z5-6") (pin "21") (pinfunction "A0_21") (pintype "input"))
    )
    (net (code "94") (name "/VA1") (class "Default")
      (node (ref "9A1") (pin "1") (pinfunction "P_1") (pintype "passive"))
      (node (ref "R12") (pin "2") (pinfunction "2_2") (pintype "passive"))
      (node (ref "Z15") (pin "5") (pinfunction "1Y2_5") (pintype "tri_state"))
      (node (ref "Z5-6") (pin "23") (pinfunction "A1_23") (pintype "input"))
    )
    (net (code "95") (name "/VA2") (class "Default")
      (node (ref "6B2") (pin "1") (pinfunction "P_1") (pintype "passive"))
      (node (ref "R13") (pin "2") (pinfunction "2_2") (pintype "passive"))
      (node (ref "Z15") (pin "7") (pinfunction "1Y3_7") (pintype "tri_state"))
      (node (ref "Z5-6") (pin "24") (pinfunction "A2_24") (pintype "input"))
    )
    (net (code "96") (name "/VA3") (class "Default")
      (node (ref "1B1") (pin "1") (pinfunction "P_1") (pintype "passive"))
      (node (ref "R14") (pin "2") (pinfunction "2_2") (pintype "passive"))
      (node (ref "Z15") (pin "9") (pinfunction "1Y4_9") (pintype "tri_state"))
      (node (ref "Z5-6") (pin "25") (pinfunction "A3_25") (pintype "input"))
    )
    (net (code "97") (name "/VA4") (class "Default")
      (node (ref "2A1") (pin "1") (pinfunction "P_1") (pintype "passive"))
      (node (ref "R15") (pin "2") (pinfunction "2_2") (pintype "passive"))
      (node (ref "Z15") (pin "11") (pinfunction "2Y1_11") (pintype "tri_state"))
      (node (ref "Z5-6") (pin "26") (pinfunction "A4_26") (pintype "input"))
    )
    (net (code "98") (name "/VA5") (class "Default")
      (node (ref "2B1") (pin "1") (pinfunction "P_1") (pintype "passive"))
      (node (ref "R16") (pin "2") (pinfunction "2_2") (pintype "passive"))
      (node (ref "Z15") (pin "13") (pinfunction "2Y2_13") (pintype "tri_state"))
      (node (ref "Z5-6") (pin "1") (pinfunction "A5_1") (pintype "input"))
    )
    (net (code "99") (name "/VA6") (class "Default")
      (node (ref "5B2") (pin "1") (pinfunction "P_1") (pintype "passive"))
      (node (ref "R17") (pin "2") (pinfunction "2_2") (pintype "passive"))
      (node (ref "Z16") (pin "3") (pinfunction "1Y1_3") (pintype "tri_state"))
      (node (ref "Z5-6") (pin "2") (pinfunction "A6_2") (pintype "input"))
    )
    (net (code "100") (name "/VA7") (class "Default")
      (node (ref "8A1") (pin "1") (pinfunction "P_1") (pintype "passive"))
      (node (ref "R18") (pin "2") (pinfunction "2_2") (pintype "passive"))
      (node (ref "Z16") (pin "5") (pinfunction "1Y2_5") (pintype "tri_state"))
      (node (ref "Z5-6") (pin "3") (pinfunction "A7_3") (pintype "input"))
    )
    (net (code "101") (name "/VA8") (class "Default")
      (node (ref "8B2") (pin "1") (pinfunction "P_1") (pintype "passive"))
      (node (ref "R19") (pin "2") (pinfunction "2_2") (pintype "passive"))
      (node (ref "Z16") (pin "7") (pinfunction "1Y3_7") (pintype "tri_state"))
      (node (ref "Z5-6") (pin "4") (pinfunction "A8_4") (pintype "input"))
    )
    (net (code "102") (name "/VA9") (class "Default")
      (node (ref "9B1") (pin "1") (pinfunction "P_1") (pintype "passive"))
      (node (ref "R20") (pin "2") (pinfunction "2_2") (pintype "passive"))
      (node (ref "Z16") (pin "9") (pinfunction "1Y4_9") (pintype "tri_state"))
      (node (ref "Z5-6") (pin "5") (pinfunction "A9_5") (pintype "input"))
    )
    (net (code "103") (name "/VD0") (class "Default")
      (node (ref "5A1") (pin "1") (pinfunction "P_1") (pintype "passive"))
      (node (ref "R100") (pin "2") (pinfunction "2_2") (pintype "passive"))
      (node (ref "Z18") (pin "3") (pinfunction "1Y1_3") (pintype "tri_state"))
      (node (ref "Z5-6") (pin "11") (pinfunction "DQ0_11") (pintype "bidirectional"))
      (node (ref "Z7-8") (pin "25") (pinfunction "A3_25") (pintype "input"))
    )
    (net (code "104") (name "/VD1") (class "Default")
      (node (ref "4B2") (pin "1") (pinfunction "P_1") (pintype "passive"))
      (node (ref "R101") (pin "2") (pinfunction "2_2") (pintype "passive"))
      (node (ref "Z17") (pin "13") (pinfunction "2Y2_13") (pintype "tri_state"))
      (node (ref "Z5-6") (pin "12") (pinfunction "DQ1_12") (pintype "bidirectional"))
      (node (ref "Z7-8") (pin "26") (pinfunction "A4_26") (pintype "input"))
    )
    (net (code "105") (name "/VD2") (class "Default")
      (node (ref "3B1") (pin "1") (pinfunction "P_1") (pintype "passive"))
      (node (ref "R102") (pin "2") (pinfunction "2_2") (pintype "passive"))
      (node (ref "Z17") (pin "11") (pinfunction "2Y1_11") (pintype "tri_state"))
      (node (ref "Z5-6") (pin "13") (pinfunction "DQ2_13") (pintype "bidirectional"))
      (node (ref "Z7-8") (pin "1") (pinfunction "A5_1") (pintype "input"))
    )
    (net (code "106") (name "/VD3") (class "Default")
      (node (ref "3A1") (pin "1") (pinfunction "P_1") (pintype "passive"))
      (node (ref "R103") (pin "2") (pinfunction "2_2") (pintype "passive"))
      (node (ref "Z17") (pin "9") (pinfunction "1Y4_9") (pintype "tri_state"))
      (node (ref "Z5-6") (pin "15") (pinfunction "DQ3_15") (pintype "bidirectional"))
      (node (ref "Z7-8") (pin "2") (pinfunction "A6_2") (pintype "input"))
    )
    (net (code "107") (name "/VD4") (class "Default")
      (node (ref "4A1") (pin "1") (pinfunction "P_1") (pintype "passive"))
      (node (ref "R104") (pin "2") (pinfunction "2_2") (pintype "passive"))
      (node (ref "Z17") (pin "7") (pinfunction "1Y3_7") (pintype "tri_state"))
      (node (ref "Z5-6") (pin "16") (pinfunction "DQ4_16") (pintype "bidirectional"))
      (node (ref "Z7-8") (pin "3") (pinfunction "A7_3") (pintype "input"))
    )
    (net (code "108") (name "/VD5") (class "Default")
      (node (ref "7A1") (pin "1") (pinfunction "P_1") (pintype "passive"))
      (node (ref "R105") (pin "2") (pinfunction "2_2") (pintype "passive"))
      (node (ref "Z17") (pin "5") (pinfunction "1Y2_5") (pintype "tri_state"))
      (node (ref "Z5-6") (pin "17") (pinfunction "DQ5_17") (pintype "bidirectional"))
      (node (ref "Z7-8") (pin "4") (pinfunction "A8_4") (pintype "input"))
    )
    (net (code "109") (name "/VD6") (class "Default")
      (node (ref "10B1") (pin "1") (pinfunction "P_1") (pintype "passive"))
      (node (ref "R106") (pin "2") (pinfunction "2_2") (pintype "passive"))
      (node (ref "Z17") (pin "3") (pinfunction "1Y1_3") (pintype "tri_state"))
      (node (ref "Z5-6") (pin "18") (pinfunction "DQ6_18") (pintype "bidirectional"))
      (node (ref "Z7-8") (pin "5") (pinfunction "A9_5") (pintype "input"))
    )
    (net (code "110") (name "/VD7") (class "Default")
      (node (ref "6A1") (pin "1") (pinfunction "P_1") (pintype "passive"))
      (node (ref "R107") (pin "2") (pinfunction "2_2") (pintype "passive"))
      (node (ref "Z20") (pin "13") (pinfunction "I1_13") (pintype "input"))
      (node (ref "Z5-6") (pin "19") (pinfunction "DQ7_19") (pintype "bidirectional"))
    )
    (net (code "111") (name "/VIDEN") (class "Default")
      (node (ref "Z19") (pin "10") (pinfunction "I1_10") (pintype "input"))
      (node (ref "Z19") (pin "5") (pinfunction "I1_5") (pintype "input"))
      (node (ref "Z20") (pin "12") (pinfunction "I0_12") (pintype "input"))
      (node (ref "Z20") (pin "6") (pinfunction "O_6") (pintype "output"))
    )
    (net (code "112") (name "/VIDEO") (class "Default")
      (node (ref "13B1") (pin "1") (pinfunction "P_1") (pintype "passive"))
      (node (ref "14B1") (pin "1") (pinfunction "P_1") (pintype "passive"))
      (node (ref "15B1") (pin "1") (pinfunction "P_1") (pintype "passive"))
      (node (ref "R34") (pin "1") (pinfunction "1_1") (pintype "passive"))
      (node (ref "SJ1") (pin "1") (pinfunction "1_1") (pintype "passive"))
      (node (ref "X2") (pin "2") (pinfunction "1_2") (pintype "passive"))
      (node (ref "X2") (pin "2@2") (pinfunction "2_2@2") (pintype "passive"))
    )
    (net (code "115") (name "/{slash}BUSAK") (class "Default")
      (node (ref "9B") (pin "1") (pinfunction "P_1") (pintype "passive"))
      (node (ref "JP9") (pin "18") (pinfunction "18_18") (pintype "passive"))
      (node (ref "Z0") (pin "23") (pinfunction "BUSAK_23") (pintype "output"))
    )
    (net (code "116") (name "/{slash}BUSRQ") (class "Default")
      (node (ref "11B") (pin "1") (pinfunction "P_1") (pintype "passive"))
      (node (ref "JP9") (pin "16") (pinfunction "16_16") (pintype "passive"))
      (node (ref "R24") (pin "1") (pinfunction "1_1") (pintype "passive"))
      (node (ref "Z0") (pin "25") (pinfunction "BUSRQ_25") (pintype "input"))
    )
    (net (code "117") (name "/{slash}HALT") (class "Default")
      (node (ref "4B") (pin "1") (pinfunction "P_1") (pintype "passive"))
      (node (ref "JP2") (pin "18") (pinfunction "18_18") (pintype "passive"))
      (node (ref "Z0") (pin "18") (pinfunction "HALT_18") (pintype "output"))
    )
    (net (code "118") (name "/{slash}INT") (class "Default")
      (node (ref "2B") (pin "1") (pinfunction "P_1") (pintype "passive"))
      (node (ref "JP2") (pin "16") (pinfunction "16_16") (pintype "passive"))
      (node (ref "Z0") (pin "16") (pinfunction "INT_16") (pintype "input"))
      (node (ref "Z19") (pin "11") (pinfunction "O_11") (pintype "output"))
    )
    (net (code "119") (name "/{slash}IORQ") (class "Default")
      (node (ref "6B") (pin "1") (pinfunction "P_1") (pintype "passive"))
      (node (ref "JP2") (pin "20") (pinfunction "20_20") (pintype "passive"))
      (node (ref "Z0") (pin "20") (pinfunction "IORQ_20") (pintype "output"))
      (node (ref "Z26") (pin "4") (pinfunction "I0_4") (pintype "input"))
    )
    (net (code "120") (name "/{slash}M1") (class "Default")
      (node (ref "13B") (pin "1") (pinfunction "P_1") (pintype "passive"))
      (node (ref "JP9") (pin "14") (pinfunction "14_14") (pintype "passive"))
      (node (ref "Z0") (pin "27") (pinfunction "M1_27") (pintype "output"))
    )
    (net (code "121") (name "/{slash}MREQ") (class "Default")
      (node (ref "5B") (pin "1") (pinfunction "P_1") (pintype "passive"))
      (node (ref "JP2") (pin "19") (pinfunction "19_19") (pintype "passive"))
      (node (ref "Z0") (pin "19") (pinfunction "MREQ_19") (pintype "output"))
      (node (ref "Z29") (pin "4") (pinfunction "G2A_4") (pintype "input"))
    )
    (net (code "122") (name "/{slash}NMI") (class "Default")
      (node (ref "3B") (pin "1") (pinfunction "P_1") (pintype "passive"))
      (node (ref "JP2") (pin "17") (pinfunction "17_17") (pintype "passive"))
      (node (ref "R39") (pin "1") (pinfunction "1_1") (pintype "passive"))
      (node (ref "Z0") (pin "17") (pinfunction "NMI_17") (pintype "input"))
    )
    (net (code "123") (name "/{slash}RD") (class "Default")
      (node (ref "7B") (pin "1") (pinfunction "P_1") (pintype "passive"))
      (node (ref "JP9") (pin "20") (pinfunction "20_20") (pintype "passive"))
      (node (ref "Z0") (pin "21") (pinfunction "RD_21") (pintype "output"))
      (node (ref "Z26") (pin "10") (pinfunction "I1_10") (pintype "input"))
      (node (ref "Z3-4") (pin "22") (pinfunction "~{OE}_22") (pintype "input"))
    )
    (net (code "124") (name "/{slash}RFSH") (class "Default")
      (node (ref "14B") (pin "1") (pinfunction "P_1") (pintype "passive"))
      (node (ref "JP9") (pin "13") (pinfunction "13_13") (pintype "passive"))
      (node (ref "Z0") (pin "28") (pinfunction "RFSH_28") (pintype "output"))
    )
    (net (code "125") (name "/{slash}VHOLD") (class "Default")
      (node (ref "Z16") (pin "15") (pinfunction "2G_15") (pintype "input"))
      (node (ref "Z19") (pin "8") (pinfunction "O_8") (pintype "output"))
      (node (ref "Z26") (pin "1") (pinfunction "I0_1") (pintype "input"))
    )
    (net (code "126") (name "/{slash}WAIT") (class "Default")
      (node (ref "10B") (pin "1") (pinfunction "P_1") (pintype "passive"))
      (node (ref "C8") (pin "1") (pinfunction "1_1") (pintype "passive"))
      (node (ref "JP9") (pin "17") (pinfunction "17_17") (pintype "passive"))
      (node (ref "Z0") (pin "24") (pinfunction "WAIT_24") (pintype "input"))
      (node (ref "Z26") (pin "3") (pinfunction "O_3") (pintype "output"))
    )
    (net (code "127") (name "/{slash}WE1") (class "Default")
      (node (ref "22A") (pin "1") (pinfunction "P_1") (pintype "passive"))
      (node (ref "7B2") (pin "1") (pinfunction "P_1") (pintype "passive"))
      (node (ref "Z26") (pin "11") (pinfunction "O_11") (pintype "output"))
      (node (ref "Z30") (pin "1") (pinfunction "I0_1") (pintype "input"))
      (node (ref "Z30") (pin "2") (pinfunction "I1_2") (pintype "input"))
      (node (ref "Z5-6") (pin "27") (pinfunction "~{WE}_27") (pintype "input"))
      (node (ref "Z7-8") (pin "27") (pinfunction "~{WE}_27") (pintype "input"))
    )
    (net (code "128") (name "/{slash}WR") (class "Default")
      (node (ref "8B") (pin "1") (pinfunction "P_1") (pintype "passive"))
      (node (ref "JP9") (pin "19") (pinfunction "19_19") (pintype "passive"))
      (node (ref "Z0") (pin "22") (pinfunction "WR_22") (pintype "output"))
      (node (ref "Z25") (pin "9") (pinfunction "I1_9") (pintype "input"))
      (node (ref "Z26") (pin "12") (pinfunction "I0_12") (pintype "input"))
      (node (ref "Z3-4") (pin "27") (pinfunction "~{WE}_27") (pintype "input"))
    )
    (net (code "129") (name "GND") (class "Default")
      (node (ref "11A1") (pin "1") (pinfunction "P_1") (pintype "passive"))
      (node (ref "13A1") (pin "1") (pinfunction "P_1") (pintype "passive"))
      (node (ref "14A1") (pin "1") (pinfunction "P_1") (pintype "passive"))
      (node (ref "15A1") (pin "1") (pinfunction "P_1") (pintype "passive"))
      (node (ref "1A") (pin "1") (pinfunction "P_1") (pintype "passive"))
      (node (ref "1B") (pin "1") (pinfunction "P_1") (pintype "passive"))
      (node (ref "26A") (pin "1") (pinfunction "P_1") (pintype "passive"))
      (node (ref "26B") (pin "1") (pinfunction "P_1") (pintype "passive"))
      (node (ref "27A") (pin "1") (pinfunction "P_1") (pintype "passive"))
      (node (ref "27B") (pin "1") (pinfunction "P_1") (pintype "passive"))
      (node (ref "28A") (pin "1") (pinfunction "P_1") (pintype "passive"))
      (node (ref "28B") (pin "1") (pinfunction "P_1") (pintype "passive"))
      (node (ref "2A") (pin "1") (pinfunction "P_1") (pintype "passive"))
      (node (ref "C10") (pin "2") (pinfunction "2_2") (pintype "passive"))
      (node (ref "C11") (pin "-") (pinfunction "-_-") (pintype "passive"))
      (node (ref "C12") (pin "-") (pinfunction "-_-") (pintype "passive"))
      (node (ref "C13") (pin "1") (pinfunction "1_1") (pintype "passive"))
      (node (ref "C14") (pin "1") (pinfunction "1_1") (pintype "passive"))
      (node (ref "C15") (pin "1") (pinfunction "1_1") (pintype "passive"))
      (node (ref "C16") (pin "1") (pinfunction "1_1") (pintype "passive"))
      (node (ref "C17") (pin "1") (pinfunction "1_1") (pintype "passive"))
      (node (ref "C18") (pin "1") (pinfunction "1_1") (pintype "passive"))
      (node (ref "C19") (pin "1") (pinfunction "1_1") (pintype "passive"))
      (node (ref "C2") (pin "2") (pinfunction "2_2") (pintype "passive"))
      (node (ref "C20") (pin "1") (pinfunction "1_1") (pintype "passive"))
      (node (ref "C21") (pin "1") (pinfunction "1_1") (pintype "passive"))
      (node (ref "C22") (pin "1") (pinfunction "1_1") (pintype "passive"))
      (node (ref "C23") (pin "1") (pinfunction "1_1") (pintype "passive"))
      (node (ref "C4") (pin "1") (pinfunction "1_1") (pintype "passive"))
      (node (ref "C7") (pin "-") (pinfunction "-_-") (pintype "passive"))
      (node (ref "C8") (pin "2") (pinfunction "2_2") (pintype "passive"))
      (node (ref "C9") (pin "-") (pinfunction "-_-") (pintype "passive"))
      (node (ref "EAR") (pin "GND") (pinfunction "SLEEVE_GND") (pintype "passive"))
      (node (ref "JP11") (pin "1") (pinfunction "1_1") (pintype "passive"))
      (node (ref "JP11") (pin "3") (pinfunction "3_3") (pintype "passive"))
      (node (ref "JP11") (pin "5") (pinfunction "5_5") (pintype "passive"))
      (node (ref "JP11") (pin "7") (pinfunction "7_7") (pintype "passive"))
      (node (ref "JP11") (pin "9") (pinfunction "9_9") (pintype "passive"))
      (node (ref "JP12") (pin "1") (pinfunction "1_1") (pintype "passive"))
      (node (ref "JP12") (pin "3") (pinfunction "3_3") (pintype "passive"))
      (node (ref "JP12") (pin "5") (pinfunction "5_5") (pintype "passive"))
      (node (ref "JP12") (pin "7") (pinfunction "7_7") (pintype "passive"))
      (node (ref "JP12") (pin "9") (pinfunction "9_9") (pintype "passive"))
      (node (ref "JP6") (pin "1") (pinfunction "1_1") (pintype "passive"))
      (node (ref "JP9") (pin "12") (pinfunction "12_12") (pintype "passive"))
      (node (ref "LED1") (pin "K") (pinfunction "C_K") (pintype "passive"))
      (node (ref "LED2") (pin "K") (pinfunction "C_K") (pintype "passive"))
      (node (ref "MIC") (pin "GND") (pinfunction "SLEEVE_GND") (pintype "passive"))
      (node (ref "POWER") (pin "GND") (pinfunction "SLEEVE_GND") (pintype "passive"))
      (node (ref "Q1") (pin "3") (pinfunction "E_3") (pintype "passive"))
      (node (ref "Q3") (pin "1") (pinfunction "E_1") (pintype "passive"))
      (node (ref "R32") (pin "1") (pinfunction "1_1") (pintype "passive"))
      (node (ref "R4") (pin "E") (pinfunction "E_E") (pintype "passive"))
      (node (ref "R5") (pin "1") (pinfunction "1_1") (pintype "passive"))
      (node (ref "R6") (pin "1") (pinfunction "1_1") (pintype "passive"))
      (node (ref "S1") (pin "1") (pinfunction "1_1") (pintype "passive"))
      (node (ref "S1") (pin "2") (pinfunction "2_2") (pintype "passive"))
      (node (ref "S1") (pin "3") (pinfunction "3_3") (pintype "passive"))
      (node (ref "S2") (pin "1") (pinfunction "P_1") (pintype "passive"))
      (node (ref "U1") (pin "2") (pinfunction "GND_2") (pintype "passive"))
      (node (ref "U2") (pin "2") (pinfunction "VEE_2") (pintype "power_in"))
      (node (ref "X1") (pin "2") (pinfunction "2_2") (pintype "passive"))
      (node (ref "X2") (pin "1") (pinfunction "2_1") (pintype "passive"))
      (node (ref "Z0") (pin "29") (pinfunction "GND_29") (pintype "power_in"))
      (node (ref "Z1") (pin "1") (pinfunction "CLR_1") (pintype "input"))
      (node (ref "Z1") (pin "2") (pinfunction "D_2") (pintype "input"))
      (node (ref "Z1") (pin "3") (pinfunction "CLK_3") (pintype "input"))
      (node (ref "Z1") (pin "4") (pinfunction "PRE_4") (pintype "input"))
      (node (ref "Z1-2") (pin "14") (pinfunction "VSS_14") (pintype "power_in"))
      (node (ref "Z10") (pin "12") (pinfunction "CLR_12") (pintype "input"))
      (node (ref "Z18") (pin "15") (pinfunction "2G_15") (pintype "input"))
      (node (ref "Z23") (pin "10") (pinfunction "I1_10") (pintype "input"))
      (node (ref "Z28") (pin "1") (pinfunction "SER_1") (pintype "input"))
      (node (ref "Z28") (pin "6") (pinfunction "INH_6") (pintype "input"))
      (node (ref "Z40") (pin "10") (pinfunction "GND_10") (pintype "power_in"))
      (node (ref "Z41") (pin "12") (pinfunction "I0_12") (pintype "input"))
      (node (ref "Z41") (pin "13") (pinfunction "I1_13") (pintype "input"))
      (node (ref "Z9") (pin "12") (pinfunction "CLR_12") (pintype "input"))
      (node (ref "Z9") (pin "2") (pinfunction "CLR_2") (pintype "input"))
    )
    (net (code "130") (name "Net-(C1-Pad1)") (class "Default")
      (node (ref "C1") (pin "1") (pinfunction "1_1") (pintype "passive"))
      (node (ref "X1") (pin "3") (pinfunction "3_3") (pintype "passive"))
    )
    (net (code "131") (name "Net-(C3-Pad1)") (class "Default")
      (node (ref "C3") (pin "1") (pinfunction "1_1") (pintype "passive"))
      (node (ref "EAR") (pin "TIP") (pinfunction "TIP_TIP") (pintype "passive"))
      (node (ref "R6") (pin "2") (pinfunction "2_2") (pintype "passive"))
    )
    (net (code "132") (name "Net-(C5-Pad1)") (class "Default")
      (node (ref "C5") (pin "1") (pinfunction "1_1") (pintype "passive"))
      (node (ref "C6") (pin "1") (pinfunction "1_1") (pintype "passive"))
      (node (ref "MIC") (pin "TIP") (pinfunction "TIP_TIP") (pintype "passive"))
    )
    (net (code "133") (name "Net-(C6-Pad2)") (class "Default")
      (node (ref "C6") (pin "2") (pinfunction "2_2") (pintype "passive"))
      (node (ref "R10") (pin "1") (pinfunction "1_1") (pintype "passive"))
    )
    (net (code "134") (name "Net-(D1-PadA)") (class "Default")
      (node (ref "D1") (pin "A") (pinfunction "A_A") (pintype "passive"))
      (node (ref "R3") (pin "S") (pinfunction "S_S") (pintype "passive"))
      (node (ref "R4") (pin "A") (pinfunction "A_A") (pintype "passive"))
      (node (ref "SJ1") (pin "2") (pinfunction "2_2") (pintype "passive"))
    )
    (net (code "135") (name "Net-(JP7-Pad2)") (class "Default")
      (node (ref "JP7") (pin "2") (pinfunction "2_2") (pintype "passive"))
      (node (ref "POWER") (pin "TIP") (pinfunction "TIP_TIP") (pintype "passive"))
    )
    (net (code "136") (name "Net-(JP17-Pad1)") (class "Default")
      (node (ref "JP17") (pin "1") (pinfunction "1_1") (pintype "passive"))
      (node (ref "R23") (pin "1") (pinfunction "1_1") (pintype "passive"))
    )
    (net (code "137") (name "Net-(LED1-PadA)") (class "Default")
      (node (ref "LED1") (pin "A") (pinfunction "A_A") (pintype "passive"))
      (node (ref "R28") (pin "2") (pinfunction "2_2") (pintype "passive"))
    )
    (net (code "138") (name "Net-(LED2-PadA)") (class "Default")
      (node (ref "LED2") (pin "A") (pinfunction "A_A") (pintype "passive"))
      (node (ref "R29") (pin "1") (pinfunction "1_1") (pintype "passive"))
    )
    (net (code "139") (name "Net-(LS1-1)") (class "Default")
      (node (ref "C5") (pin "2") (pinfunction "2_2") (pintype "passive"))
      (node (ref "D2") (pin "A") (pinfunction "A_A") (pintype "passive"))
      (node (ref "LS1") (pin "-") (pinfunction "1_-") (pintype "passive"))
      (node (ref "Q3") (pin "3") (pinfunction "C_3") (pintype "passive"))
    )
    (net (code "140") (name "Net-(Q1-B)") (class "Default")
      (node (ref "C2") (pin "1") (pinfunction "1_1") (pintype "passive"))
      (node (ref "Q1") (pin "2") (pinfunction "B_2") (pintype "passive"))
      (node (ref "R2") (pin "1") (pinfunction "1_1") (pintype "passive"))
      (node (ref "X1") (pin "1") (pinfunction "1_1") (pintype "passive"))
    )
    (net (code "141") (name "Net-(Q1-C)") (class "Default")
      (node (ref "C1") (pin "2") (pinfunction "2_2") (pintype "passive"))
      (node (ref "Q1") (pin "1") (pinfunction "C_1") (pintype "passive"))
      (node (ref "R1") (pin "2") (pinfunction "2_2") (pintype "passive"))
      (node (ref "R2") (pin "2") (pinfunction "2_2") (pintype "passive"))
      (node (ref "Z23") (pin "9") (pinfunction "I0_9") (pintype "input"))
    )
    (net (code "142") (name "Net-(Q3-B)") (class "Default")
      (node (ref "Q3") (pin "2") (pinfunction "B_2") (pintype "passive"))
      (node (ref "R9") (pin "1") (pinfunction "1_1") (pintype "passive"))
    )
    (net (code "143") (name "Net-(U2-IN+)") (class "Default")
      (node (ref "R4") (pin "S") (pinfunction "S_S") (pintype "passive"))
      (node (ref "U2") (pin "3") (pinfunction "IN+_3") (pintype "input"))
    )
    (net (code "144") (name "Net-(U2-IN-)") (class "Default")
      (node (ref "R32") (pin "2") (pinfunction "2_2") (pintype "passive"))
      (node (ref "R33") (pin "2") (pinfunction "2_2") (pintype "passive"))
      (node (ref "U2") (pin "4") (pinfunction "IN-_4") (pintype "input"))
    )
    (net (code "145") (name "Net-(U2-OUT)") (class "Default")
      (node (ref "R33") (pin "1") (pinfunction "1_1") (pintype "passive"))
      (node (ref "R34") (pin "2") (pinfunction "2_2") (pintype "passive"))
      (node (ref "U2") (pin "1") (pinfunction "OUT_1") (pintype "output"))
    )
    (net (code "146") (name "Net-(Z1-2-A13)") (class "Default")
      (node (ref "R27") (pin "2") (pinfunction "2_2") (pintype "passive"))
      (node (ref "S1") (pin "5") (pinfunction "5_5") (pintype "passive"))
      (node (ref "Z1-2") (pin "26") (pinfunction "A13_26") (pintype "input"))
    )
    (net (code "147") (name "Net-(Z1-2-A14)") (class "Default")
      (node (ref "R8") (pin "2") (pinfunction "2_2") (pintype "passive"))
      (node (ref "S1") (pin "4") (pinfunction "4_4") (pintype "passive"))
      (node (ref "Z1-2") (pin "27") (pinfunction "A14_27") (pintype "input"))
    )
    (net (code "148") (name "Net-(Z1-2-~{CE})") (class "Default")
      (node (ref "Z1-2") (pin "20") (pinfunction "~{CE}_20") (pintype "input"))
      (node (ref "Z1-2") (pin "22") (pinfunction "~{OE}/VPP_22") (pintype "input"))
      (node (ref "Z22") (pin "8") (pinfunction "O_8") (pintype "output"))
    )
    (net (code "149") (name "Net-(Z1B-CLK)") (class "Default")
      (node (ref "Z1") (pin "11") (pinfunction "CLK_11") (pintype "input"))
      (node (ref "Z41") (pin "8") (pinfunction "O_8") (pintype "output"))
    )
    (net (code "150") (name "Net-(Z1B-Q)") (class "Default")
      (node (ref "Z1") (pin "9") (pinfunction "Q_9") (pintype "output"))
      (node (ref "Z31") (pin "9") (pinfunction "I0_9") (pintype "input"))
    )
    (net (code "151") (name "Net-(Z3-4A-~{CE})") (class "Default")
      (node (ref "JP3") (pin "2") (pinfunction "2_2") (pintype "passive"))
      (node (ref "Z3-4") (pin "20") (pinfunction "~{CE}_20") (pintype "input"))
    )
    (net (code "152") (name "Net-(Z5-6A-A10)") (class "Default")
      (node (ref "JP11") (pin "2") (pinfunction "2_2") (pintype "passive"))
      (node (ref "Z5-6") (pin "6") (pinfunction "A10_6") (pintype "input"))
    )
    (net (code "153") (name "Net-(Z5-6A-A11)") (class "Default")
      (node (ref "JP11") (pin "4") (pinfunction "4_4") (pintype "passive"))
      (node (ref "Z5-6") (pin "7") (pinfunction "A11_7") (pintype "input"))
    )
    (net (code "154") (name "Net-(Z5-6A-A12)") (class "Default")
      (node (ref "JP11") (pin "6") (pinfunction "6_6") (pintype "passive"))
      (node (ref "Z5-6") (pin "8") (pinfunction "A12_8") (pintype "input"))
    )
    (net (code "155") (name "Net-(Z5-6A-A13)") (class "Default")
      (node (ref "JP11") (pin "8") (pinfunction "8_8") (pintype "passive"))
      (node (ref "Z5-6") (pin "9") (pinfunction "A13_9") (pintype "input"))
    )
    (net (code "156") (name "Net-(Z5-6A-A14)") (class "Default")
      (node (ref "JP11") (pin "10") (pinfunction "10_10") (pintype "passive"))
      (node (ref "Z5-6") (pin "10") (pinfunction "A14_10") (pintype "input"))
    )
    (net (code "157") (name "Net-(Z7-8A-A10)") (class "Default")
      (node (ref "JP12") (pin "2") (pinfunction "2_2") (pintype "passive"))
      (node (ref "Z7-8") (pin "6") (pinfunction "A10_6") (pintype "input"))
    )
    (net (code "158") (name "Net-(Z7-8A-A11)") (class "Default")
      (node (ref "JP12") (pin "4") (pinfunction "4_4") (pintype "passive"))
      (node (ref "Z7-8") (pin "7") (pinfunction "A11_7") (pintype "input"))
    )
    (net (code "159") (name "Net-(Z7-8A-A12)") (class "Default")
      (node (ref "JP12") (pin "6") (pinfunction "6_6") (pintype "passive"))
      (node (ref "Z7-8") (pin "8") (pinfunction "A12_8") (pintype "input"))
    )
    (net (code "160") (name "Net-(Z7-8A-A13)") (class "Default")
      (node (ref "JP12") (pin "8") (pinfunction "8_8") (pintype "passive"))
      (node (ref "Z7-8") (pin "9") (pinfunction "A13_9") (pintype "input"))
    )
    (net (code "161") (name "Net-(Z7-8A-A14)") (class "Default")
      (node (ref "JP12") (pin "10") (pinfunction "10_10") (pintype "passive"))
      (node (ref "Z7-8") (pin "10") (pinfunction "A14_10") (pintype "input"))
    )
    (net (code "162") (name "Net-(Z10A-CLR)") (class "Default")
      (node (ref "Z10") (pin "2") (pinfunction "CLR_2") (pintype "input"))
      (node (ref "Z21") (pin "8") (pinfunction "O_8") (pintype "output"))
    )
    (net (code "163") (name "Net-(Z11A-CLR)") (class "Default")
      (node (ref "Z11") (pin "12") (pinfunction "CLR_12") (pintype "input"))
      (node (ref "Z11") (pin "2") (pinfunction "CLR_2") (pintype "input"))
      (node (ref "Z20") (pin "3") (pinfunction "O_3") (pintype "output"))
    )
    (net (code "164") (name "Net-(Z14A-1G)") (class "Default")
      (node (ref "Z14") (pin "1") (pinfunction "1G_1") (pintype "input"))
      (node (ref "Z14") (pin "15") (pinfunction "2G_15") (pintype "input"))
      (node (ref "Z23") (pin "2") (pinfunction "I1_2") (pintype "input"))
      (node (ref "Z26") (pin "8") (pinfunction "O_8") (pintype "output"))
    )
    (net (code "165") (name "Net-(Z15A-1G)") (class "Default")
      (node (ref "D11") (pin "C") (pinfunction "C_C") (pintype "passive"))
      (node (ref "JP14") (pin "1") (pinfunction "1_1") (pintype "passive"))
      (node (ref "R26") (pin "2") (pinfunction "2_2") (pintype "passive"))
      (node (ref "Z15") (pin "1") (pinfunction "1G_1") (pintype "input"))
      (node (ref "Z15") (pin "15") (pinfunction "2G_15") (pintype "input"))
      (node (ref "Z16") (pin "1") (pinfunction "1G_1") (pintype "input"))
      (node (ref "Z16") (pin "14") (pinfunction "2A2_14") (pintype "input"))
      (node (ref "Z24") (pin "2") (pinfunction "I0_2") (pintype "input"))
      (node (ref "Z24") (pin "5") (pinfunction "I0_5") (pintype "input"))
      (node (ref "Z26") (pin "13") (pinfunction "I1_13") (pintype "input"))
    )
    (net (code "166") (name "Net-(Z16A-2Y2)") (class "Default")
      (node (ref "D11") (pin "A") (pinfunction "A_A") (pintype "passive"))
      (node (ref "Z16") (pin "13") (pinfunction "2Y2_13") (pintype "tri_state"))
    )
    (net (code "167") (name "Net-(Z17A-1G)") (class "Default")
      (node (ref "Z17") (pin "1") (pinfunction "1G_1") (pintype "input"))
      (node (ref "Z17") (pin "15") (pinfunction "2G_15") (pintype "input"))
      (node (ref "Z18") (pin "1") (pinfunction "1G_1") (pintype "input"))
      (node (ref "Z23") (pin "6") (pinfunction "O_6") (pintype "output"))
    )
    (net (code "168") (name "Net-(Z18A-1Y2)") (class "Default")
      (node (ref "R23") (pin "2") (pinfunction "2_2") (pintype "passive"))
      (node (ref "Z18") (pin "5") (pinfunction "1Y2_5") (pintype "tri_state"))
      (node (ref "Z7-8") (pin "24") (pinfunction "A2_24") (pintype "input"))
    )
    (net (code "169") (name "Net-(Z18A-1Y3)") (class "Default")
      (node (ref "R22") (pin "2") (pinfunction "2_2") (pintype "passive"))
      (node (ref "Z18") (pin "7") (pinfunction "1Y3_7") (pintype "tri_state"))
      (node (ref "Z7-8") (pin "23") (pinfunction "A1_23") (pintype "input"))
    )
    (net (code "170") (name "Net-(Z18A-1Y4)") (class "Default")
      (node (ref "R21") (pin "2") (pinfunction "2_2") (pintype "passive"))
      (node (ref "Z18") (pin "9") (pinfunction "1Y4_9") (pintype "tri_state"))
      (node (ref "Z7-8") (pin "21") (pinfunction "A0_21") (pintype "input"))
    )
    (net (code "171") (name "Net-(Z18A-2A2)") (class "Default")
      (node (ref "C3") (pin "2") (pinfunction "2_2") (pintype "passive"))
      (node (ref "R5") (pin "2") (pinfunction "2_2") (pintype "passive"))
      (node (ref "R7") (pin "1") (pinfunction "1_1") (pintype "passive"))
      (node (ref "Z18") (pin "14") (pinfunction "2A2_14") (pintype "input"))
    )
    (net (code "172") (name "Net-(Z19A-O)") (class "Default")
      (node (ref "Z19") (pin "3") (pinfunction "O_3") (pintype "output"))
      (node (ref "Z20") (pin "4") (pinfunction "I0_4") (pintype "input"))
    )
    (net (code "173") (name "Net-(Z19B-I0)") (class "Default")
      (node (ref "Z19") (pin "4") (pinfunction "I0_4") (pintype "input"))
      (node (ref "Z20") (pin "9") (pinfunction "I0_9") (pintype "input"))
      (node (ref "Z22") (pin "6") (pinfunction "O_6") (pintype "output"))
    )
    (net (code "174") (name "Net-(Z19B-O)") (class "Default")
      (node (ref "Z19") (pin "6") (pinfunction "O_6") (pintype "output"))
      (node (ref "Z28") (pin "15") (pinfunction "SH/~{LD}_15") (pintype "input"))
    )
    (net (code "175") (name "Net-(Z20A-I0)") (class "Default")
      (node (ref "Z20") (pin "1") (pinfunction "I0_1") (pintype "input"))
      (node (ref "Z21") (pin "13") (pinfunction "I2_13") (pintype "input"))
      (node (ref "Z21") (pin "6") (pinfunction "O_6") (pintype "output"))
    )
    (net (code "176") (name "Net-(Z20B-I1)") (class "Default")
      (node (ref "Z20") (pin "5") (pinfunction "I1_5") (pintype "input"))
      (node (ref "Z25") (pin "1") (pinfunction "O_1") (pintype "output"))
    )
    (net (code "177") (name "Net-(Z20C-O)") (class "Default")
      (node (ref "Z20") (pin "8") (pinfunction "O_8") (pintype "output"))
      (node (ref "Z27") (pin "11") (pinfunction "CLK_11") (pintype "input"))
    )
    (net (code "178") (name "Net-(Z20D-O)") (class "Default")
      (node (ref "Z20") (pin "11") (pinfunction "O_11") (pintype "output"))
      (node (ref "Z27") (pin "12") (pinfunction "D_12") (pintype "input"))
    )
    (net (code "179") (name "Net-(Z22A-I1)") (class "Default")
      (node (ref "Z22") (pin "2") (pinfunction "I1_2") (pintype "input"))
      (node (ref "Z25") (pin "13") (pinfunction "O_13") (pintype "output"))
    )
    (net (code "180") (name "Net-(Z22C-I0)") (class "Default")
      (node (ref "Z22") (pin "9") (pinfunction "I0_9") (pintype "input"))
      (node (ref "Z29") (pin "15") (pinfunction "Y0_15") (pintype "output"))
    )
    (net (code "181") (name "Net-(Z22C-I1)") (class "Default")
      (node (ref "Z22") (pin "10") (pinfunction "I1_10") (pintype "input"))
      (node (ref "Z29") (pin "14") (pinfunction "Y1_14") (pintype "output"))
    )
    (net (code "182") (name "Net-(Z23A-O)") (class "Default")
      (node (ref "Z23") (pin "3") (pinfunction "O_3") (pintype "output"))
      (node (ref "Z24") (pin "12") (pinfunction "I1_12") (pintype "input"))
    )
    (net (code "183") (name "Net-(Z23B-I0)") (class "Default")
      (node (ref "Z23") (pin "4") (pinfunction "I0_4") (pintype "input"))
      (node (ref "Z24") (pin "1") (pinfunction "O_1") (pintype "output"))
      (node (ref "Z5-6") (pin "20") (pinfunction "~{CE}_20") (pintype "input"))
    )
    (net (code "184") (name "Net-(Z23D-I0)") (class "Default")
      (node (ref "JP4") (pin "2") (pinfunction "2_2") (pintype "passive"))
      (node (ref "Z23") (pin "12") (pinfunction "I0_12") (pintype "input"))
    )
    (net (code "185") (name "Net-(Z23D-I1)") (class "Default")
      (node (ref "Z23") (pin "13") (pinfunction "I1_13") (pintype "input"))
      (node (ref "Z28") (pin "13") (pinfunction "QH_13") (pintype "output"))
    )
    (net (code "186") (name "Net-(Z23D-O)") (class "Default")
      (node (ref "C4") (pin "2") (pinfunction "2_2") (pintype "passive"))
      (node (ref "R35") (pin "2") (pinfunction "2_2") (pintype "passive"))
      (node (ref "Z23") (pin "11") (pinfunction "O_11") (pintype "output"))
    )
    (net (code "187") (name "Net-(Z24A-I1)") (class "Default")
      (node (ref "Z24") (pin "3") (pinfunction "I1_3") (pintype "input"))
      (node (ref "Z24") (pin "4") (pinfunction "O_4") (pintype "output"))
      (node (ref "Z7-8") (pin "20") (pinfunction "~{CE}_20") (pintype "input"))
    )
    (net (code "188") (name "Net-(Z24C-I0)") (class "Default")
      (node (ref "Z24") (pin "8") (pinfunction "I0_8") (pintype "input"))
      (node (ref "Z25") (pin "10") (pinfunction "O_10") (pintype "output"))
      (node (ref "Z27") (pin "3") (pinfunction "CLK_3") (pintype "input"))
    )
    (net (code "189") (name "Net-(Z24C-I1)") (class "Default")
      (node (ref "R9") (pin "2") (pinfunction "2_2") (pintype "passive"))
      (node (ref "Z24") (pin "13") (pinfunction "O_13") (pintype "output"))
      (node (ref "Z24") (pin "9") (pinfunction "I1_9") (pintype "input"))
    )
    (net (code "190") (name "Net-(Z24C-O)") (class "Default")
      (node (ref "Z24") (pin "10") (pinfunction "O_10") (pintype "output"))
      (node (ref "Z24") (pin "11") (pinfunction "I0_11") (pintype "input"))
    )
    (net (code "191") (name "Net-(Z25C-I0)") (class "Default")
      (node (ref "Z25") (pin "8") (pinfunction "I0_8") (pintype "input"))
      (node (ref "Z26") (pin "6") (pinfunction "O_6") (pintype "output"))
      (node (ref "Z26") (pin "9") (pinfunction "I0_9") (pintype "input"))
    )
    (net (code "192") (name "Net-(Z26A-I1)") (class "Default")
      (node (ref "R26") (pin "1") (pinfunction "1_1") (pintype "passive"))
      (node (ref "Z26") (pin "2") (pinfunction "I1_2") (pintype "input"))
      (node (ref "Z29") (pin "13") (pinfunction "Y2_13") (pintype "output"))
    )
    (net (code "193") (name "Net-(Z27A-Q)") (class "Default")
      (node (ref "R10") (pin "2") (pinfunction "2_2") (pintype "passive"))
      (node (ref "Z27") (pin "5") (pinfunction "Q_5") (pintype "output"))
    )
    (net (code "194") (name "Net-(Z27B-~{Q})") (class "Default")
      (node (ref "JP4") (pin "3") (pinfunction "3_3") (pintype "passive"))
      (node (ref "Z27") (pin "8") (pinfunction "~{Q}_8") (pintype "output"))
    )
    (net (code "195") (name "Net-(Z28A-A)") (class "Default")
      (node (ref "R200") (pin "2") (pinfunction "2_2") (pintype "passive"))
      (node (ref "Z28") (pin "2") (pinfunction "A_2") (pintype "input"))
      (node (ref "Z7-8") (pin "11") (pinfunction "DQ0_11") (pintype "bidirectional"))
    )
    (net (code "196") (name "Net-(Z28A-B)") (class "Default")
      (node (ref "R201") (pin "2") (pinfunction "2_2") (pintype "passive"))
      (node (ref "Z28") (pin "3") (pinfunction "B_3") (pintype "input"))
      (node (ref "Z7-8") (pin "12") (pinfunction "DQ1_12") (pintype "bidirectional"))
    )
    (net (code "197") (name "Net-(Z28A-C)") (class "Default")
      (node (ref "R202") (pin "2") (pinfunction "2_2") (pintype "passive"))
      (node (ref "Z28") (pin "4") (pinfunction "C_4") (pintype "input"))
      (node (ref "Z7-8") (pin "13") (pinfunction "DQ2_13") (pintype "bidirectional"))
    )
    (net (code "198") (name "Net-(Z28A-CLK)") (class "Default")
      (node (ref "C23") (pin "2") (pinfunction "2_2") (pintype "passive"))
      (node (ref "R44") (pin "A") (pinfunction "A_A") (pintype "passive"))
      (node (ref "Z28") (pin "7") (pinfunction "CLK_7") (pintype "input"))
    )
    (net (code "199") (name "Net-(Z28A-D)") (class "Default")
      (node (ref "R203") (pin "2") (pinfunction "2_2") (pintype "passive"))
      (node (ref "Z28") (pin "5") (pinfunction "D_5") (pintype "input"))
      (node (ref "Z7-8") (pin "15") (pinfunction "DQ3_15") (pintype "bidirectional"))
    )
    (net (code "200") (name "Net-(Z28A-E)") (class "Default")
      (node (ref "R204") (pin "2") (pinfunction "2_2") (pintype "passive"))
      (node (ref "Z28") (pin "10") (pinfunction "E_10") (pintype "input"))
      (node (ref "Z7-8") (pin "16") (pinfunction "DQ4_16") (pintype "bidirectional"))
    )
    (net (code "201") (name "Net-(Z28A-F)") (class "Default")
      (node (ref "R205") (pin "2") (pinfunction "2_2") (pintype "passive"))
      (node (ref "Z28") (pin "11") (pinfunction "F_11") (pintype "input"))
      (node (ref "Z7-8") (pin "17") (pinfunction "DQ5_17") (pintype "bidirectional"))
    )
    (net (code "202") (name "Net-(Z28A-G)") (class "Default")
      (node (ref "R206") (pin "2") (pinfunction "2_2") (pintype "passive"))
      (node (ref "Z28") (pin "12") (pinfunction "G_12") (pintype "input"))
      (node (ref "Z7-8") (pin "18") (pinfunction "DQ6_18") (pintype "bidirectional"))
    )
    (net (code "203") (name "Net-(Z28A-H)") (class "Default")
      (node (ref "R207") (pin "2") (pinfunction "2_2") (pintype "passive"))
      (node (ref "Z28") (pin "14") (pinfunction "H_14") (pintype "input"))
      (node (ref "Z7-8") (pin "19") (pinfunction "DQ7_19") (pintype "bidirectional"))
    )
    (net (code "204") (name "Net-(Z29A-Y3)") (class "Default")
      (node (ref "JP3") (pin "1") (pinfunction "1_1") (pintype "passive"))
      (node (ref "Z29") (pin "12") (pinfunction "Y3_12") (pintype "output"))
      (node (ref "Z31") (pin "3") (pinfunction "I0_3") (pintype "input"))
    )
    (net (code "205") (name "Net-(Z29A-Y4)") (class "Default")
      (node (ref "Z29") (pin "11") (pinfunction "Y4_11") (pintype "output"))
      (node (ref "Z31") (pin "4") (pinfunction "I1_4") (pintype "input"))
    )
    (net (code "206") (name "Net-(Z29A-Y5)") (class "Default")
      (node (ref "Z29") (pin "10") (pinfunction "Y5_10") (pintype "output"))
      (node (ref "Z31") (pin "5") (pinfunction "I2_5") (pintype "input"))
    )
    (net (code "207") (name "Net-(Z29A-Y6)") (class "Default")
      (node (ref "Z29") (pin "9") (pinfunction "Y6_9") (pintype "output"))
      (node (ref "Z31") (pin "2") (pinfunction "I1_2") (pintype "input"))
    )
    (net (code "208") (name "Net-(Z29A-Y7)") (class "Default")
      (node (ref "Z29") (pin "7") (pinfunction "Y7_7") (pintype "output"))
      (node (ref "Z31") (pin "13") (pinfunction "I2_13") (pintype "input"))
    )
    (net (code "209") (name "Net-(Z30A-O)") (class "Default")
      (node (ref "Z30") (pin "3") (pinfunction "O_3") (pintype "output"))
      (node (ref "Z5-6") (pin "22") (pinfunction "~{OE}_22") (pintype "input"))
      (node (ref "Z7-8") (pin "22") (pinfunction "~{OE}_22") (pintype "input"))
    )
    (net (code "210") (name "Net-(Z31A-I0)") (class "Default")
      (node (ref "Z31") (pin "1") (pinfunction "I0_1") (pintype "input"))
      (node (ref "Z31") (pin "6") (pinfunction "O_6") (pintype "output"))
    )
    (net (code "211") (name "Net-(Z31A-O)") (class "Default")
      (node (ref "JP3") (pin "3") (pinfunction "3_3") (pintype "passive"))
      (node (ref "Z31") (pin "12") (pinfunction "O_12") (pintype "output"))
    )
    (net (code "212") (name "Net-(Z31C-I1)") (class "Default")
      (node (ref "R35") (pin "1") (pinfunction "1_1") (pintype "passive"))
      (node (ref "Z31") (pin "10") (pinfunction "I1_10") (pintype "input"))
    )
    (net (code "213") (name "Net-(Z31C-O)") (class "Default")
      (node (ref "R3") (pin "A") (pinfunction "A_A") (pintype "passive"))
      (node (ref "Z31") (pin "8") (pinfunction "O_8") (pintype "output"))
    )
    (net (code "214") (name "Net-(Z40-O1)") (class "Default")
      (node (ref "D12") (pin "C") (pinfunction "C_C") (pintype "passive"))
      (node (ref "Z40") (pin "19") (pinfunction "O1_19") (pintype "output"))
    )
    (net (code "215") (name "Net-(Z40-O2)") (class "Default")
      (node (ref "D13") (pin "C") (pinfunction "C_C") (pintype "passive"))
      (node (ref "Z40") (pin "18") (pinfunction "O2_18") (pintype "output"))
    )
    (net (code "216") (name "Net-(Z40-O3)") (class "Default")
      (node (ref "D14") (pin "C") (pinfunction "C_C") (pintype "passive"))
      (node (ref "Z40") (pin "17") (pinfunction "O3_17") (pintype "output"))
    )
    (net (code "217") (name "Net-(Z40-O4)") (class "Default")
      (node (ref "D15") (pin "C") (pinfunction "C_C") (pintype "passive"))
      (node (ref "Z40") (pin "16") (pinfunction "O4_16") (pintype "output"))
    )
    (net (code "218") (name "Net-(Z40-O5)") (class "Default")
      (node (ref "D16") (pin "C") (pinfunction "C_C") (pintype "passive"))
      (node (ref "Z40") (pin "15") (pinfunction "O5_15") (pintype "output"))
    )
    (net (code "219") (name "Net-(Z40-O6)") (class "Default")
      (node (ref "D17") (pin "C") (pinfunction "C_C") (pintype "passive"))
      (node (ref "Z40") (pin "14") (pinfunction "O6_14") (pintype "output"))
    )
    (net (code "220") (name "Net-(Z41A-O)") (class "Default")
      (node (ref "Z41") (pin "3") (pinfunction "O_3") (pintype "output"))
      (node (ref "Z41") (pin "4") (pinfunction "I0_4") (pintype "input"))
    )
    (net (code "221") (name "Net-(Z41B-O)") (class "Default")
      (node (ref "Z41") (pin "10") (pinfunction "I1_10") (pintype "input"))
      (node (ref "Z41") (pin "6") (pinfunction "O_6") (pintype "output"))
    )
    (net (code "222") (name "VCC") (class "Default")
      (node (ref "11B1") (pin "1") (pinfunction "P_1") (pintype "passive"))
      (node (ref "4A") (pin "1") (pinfunction "P_1") (pintype "passive"))
      (node (ref "C12") (pin "+") (pinfunction "+_+") (pintype "passive"))
      (node (ref "C13") (pin "2") (pinfunction "2_2") (pintype "passive"))
      (node (ref "C14") (pin "2") (pinfunction "2_2") (pintype "passive"))
      (node (ref "C15") (pin "2") (pinfunction "2_2") (pintype "passive"))
      (node (ref "C16") (pin "2") (pinfunction "2_2") (pintype "passive"))
      (node (ref "C17") (pin "2") (pinfunction "2_2") (pintype "passive"))
      (node (ref "C18") (pin "2") (pinfunction "2_2") (pintype "passive"))
      (node (ref "C19") (pin "2") (pinfunction "2_2") (pintype "passive"))
      (node (ref "C20") (pin "2") (pinfunction "2_2") (pintype "passive"))
      (node (ref "C21") (pin "2") (pinfunction "2_2") (pintype "passive"))
      (node (ref "D2") (pin "C") (pinfunction "C_C") (pintype "passive"))
      (node (ref "JP2") (pin "11") (pinfunction "11_11") (pintype "passive"))
      (node (ref "JP8") (pin "1") (pinfunction "1_1") (pintype "passive"))
      (node (ref "JP8") (pin "2") (pinfunction "2_2") (pintype "passive"))
      (node (ref "LS1") (pin "+") (pinfunction "2_+") (pintype "passive"))
      (node (ref "R1") (pin "1") (pinfunction "1_1") (pintype "passive"))
      (node (ref "R24") (pin "2") (pinfunction "2_2") (pintype "passive"))
      (node (ref "R25") (pin "2") (pinfunction "2_2") (pintype "passive"))
      (node (ref "R27") (pin "1") (pinfunction "1_1") (pintype "passive"))
      (node (ref "R28") (pin "1") (pinfunction "1_1") (pintype "passive"))
      (node (ref "R3") (pin "E") (pinfunction "E_E") (pintype "passive"))
      (node (ref "R30") (pin "1") (pinfunction "1_1") (pintype "passive"))
      (node (ref "R31") (pin "1") (pinfunction "1_1") (pintype "passive"))
      (node (ref "R36") (pin "2") (pinfunction "2_2") (pintype "passive"))
      (node (ref "R37") (pin "2") (pinfunction "2_2") (pintype "passive"))
      (node (ref "R38") (pin "2") (pinfunction "2_2") (pintype "passive"))
      (node (ref "R39") (pin "2") (pinfunction "2_2") (pintype "passive"))
      (node (ref "R40") (pin "2") (pinfunction "2_2") (pintype "passive"))
      (node (ref "R41") (pin "2") (pinfunction "2_2") (pintype "passive"))
      (node (ref "R43") (pin "1") (pinfunction "1_1") (pintype "passive"))
      (node (ref "R7") (pin "2") (pinfunction "2_2") (pintype "passive"))
      (node (ref "R8") (pin "1") (pinfunction "1_1") (pintype "passive"))
      (node (ref "RN1") (pin "1") (pinfunction "1_1") (pintype "passive"))
      (node (ref "U1") (pin "3") (pinfunction "VO_3") (pintype "passive"))
      (node (ref "U2") (pin "5") (pinfunction "VCC_5") (pintype "power_in"))
      (node (ref "Z0") (pin "11") (pinfunction "VCC_11") (pintype "power_in"))
      (node (ref "Z1") (pin "10") (pinfunction "PRE_10") (pintype "input"))
      (node (ref "Z1") (pin "12") (pinfunction "D_12") (pintype "input"))
      (node (ref "Z1-2") (pin "28") (pinfunction "VCC_28") (pintype "power_in"))
      (node (ref "Z16") (pin "12") (pinfunction "2A1_12") (pintype "input"))
      (node (ref "Z18") (pin "12") (pinfunction "2A1_12") (pintype "input"))
      (node (ref "Z19") (pin "13") (pinfunction "I1_13") (pintype "input"))
      (node (ref "Z22") (pin "11") (pinfunction "I2_11") (pintype "input"))
      (node (ref "Z23") (pin "1") (pinfunction "I0_1") (pintype "input"))
      (node (ref "Z23") (pin "5") (pinfunction "I1_5") (pintype "input"))
      (node (ref "Z27") (pin "1") (pinfunction "CLR_1") (pintype "input"))
      (node (ref "Z27") (pin "10") (pinfunction "PRE_10") (pintype "input"))
      (node (ref "Z27") (pin "13") (pinfunction "CLR_13") (pintype "input"))
      (node (ref "Z27") (pin "4") (pinfunction "PRE_4") (pintype "input"))
      (node (ref "Z28") (pin "9") (pinfunction "CLR_9") (pintype "input"))
      (node (ref "Z29") (pin "6") (pinfunction "G1_6") (pintype "input"))
      (node (ref "Z31") (pin "11") (pinfunction "I2_11") (pintype "input"))
      (node (ref "Z40") (pin "20") (pinfunction "VCC_20") (pintype "power_in"))
      (node (ref "Z41") (pin "1") (pinfunction "I0_1") (pintype "input"))
      (node (ref "Z41") (pin "9") (pinfunction "I0_9") (pintype "input"))
    )
    (net (code "223") (name "unconnected-(10A1-P-Pad1)") (class "Default")
      (node (ref "10A1") (pin "1") (pinfunction "P_1") (pintype "passive"))
    )
    (net (code "224") (name "unconnected-(EAR-SWITCH-PadSW)") (class "Default")
      (node (ref "EAR") (pin "SW") (pinfunction "SWITCH_SW") (pintype "passive"))
    )
    (net (code "225") (name "unconnected-(JP7-Pad3)") (class "Default")
      (node (ref "JP7") (pin "3") (pinfunction "3_3") (pintype "passive"))
    )
    (net (code "226") (name "unconnected-(MIC-SWITCH-PadSW)") (class "Default")
      (node (ref "MIC") (pin "SW") (pinfunction "SWITCH_SW") (pintype "passive"))
    )
    (net (code "227") (name "unconnected-(POWER-SWITCH-PadSW)") (class "Default")
      (node (ref "POWER") (pin "SW") (pinfunction "SWITCH_SW") (pintype "passive"))
    )
    (net (code "228") (name "unconnected-(Z1A-Q-Pad5)") (class "Default")
      (node (ref "Z1") (pin "5") (pinfunction "Q_5") (pintype "output"))
    )
    (net (code "229") (name "unconnected-(Z1A-~{Q}-Pad6)") (class "Default")
      (node (ref "Z1") (pin "6") (pinfunction "~{Q}_6") (pintype "output"))
    )
    (net (code "230") (name "unconnected-(Z1B-~{Q}-Pad8)") (class "Default")
      (node (ref "Z1") (pin "8") (pinfunction "~{Q}_8") (pintype "output"))
    )
    (net (code "231") (name "unconnected-(Z9B-QB-Pad10)") (class "Default")
      (node (ref "Z9") (pin "10") (pinfunction "QB_10") (pintype "output"))
    )
    (net (code "232") (name "unconnected-(Z9B-QC-Pad9)") (class "Default")
      (node (ref "Z9") (pin "9") (pinfunction "QC_9") (pintype "output"))
    )
    (net (code "233") (name "unconnected-(Z9B-QD-Pad8)") (class "Default")
      (node (ref "Z9") (pin "8") (pinfunction "QD_8") (pintype "output"))
    )
    (net (code "234") (name "unconnected-(Z10B-QD-Pad8)") (class "Default")
      (node (ref "Z10") (pin "8") (pinfunction "QD_8") (pintype "output"))
    )
    (net (code "235") (name "unconnected-(Z11B-QC-Pad9)") (class "Default")
      (node (ref "Z11") (pin "9") (pinfunction "QC_9") (pintype "output"))
    )
    (net (code "236") (name "unconnected-(Z11B-QD-Pad8)") (class "Default")
      (node (ref "Z11") (pin "8") (pinfunction "QD_8") (pintype "output"))
    )
    (net (code "237") (name "unconnected-(Z16A-2Y1-Pad11)") (class "Default")
      (node (ref "Z16") (pin "11") (pinfunction "2Y1_11") (pintype "tri_state"))
    )
    (net (code "238") (name "unconnected-(Z18A-2Y1-Pad11)") (class "Default")
      (node (ref "Z18") (pin "11") (pinfunction "2Y1_11") (pintype "tri_state"))
    )
    (net (code "239") (name "unconnected-(Z27A-~{Q}-Pad6)") (class "Default")
      (node (ref "Z27") (pin "6") (pinfunction "~{Q}_6") (pintype "output"))
    )
    (net (code "240") (name "unconnected-(Z40-O7-Pad13)") (class "Default")
      (node (ref "Z40") (pin "13") (pinfunction "O7_13") (pintype "output"))
    )
    (net (code "241") (name "unconnected-(Z40-O8-Pad12)") (class "Default")
      (node (ref "Z40") (pin "12") (pinfunction "O8_12") (pintype "output"))
    )
    (net (code "242") (name "unconnected-(Z40-OE-Pad11)") (class "Default")
      (node (ref "Z40") (pin "11") (pinfunction "OE_11") (pintype "input"))
    )
    (net (code "243") (name "unconnected-(Z41D-O-Pad11)") (class "Default")
      (node (ref "Z41") (pin "11") (pinfunction "O_11") (pintype "output"))
    )
  )
)
